# icyradio-exp-mmw-int.net
KiCad netlist of a schematic drawn in EAGLE
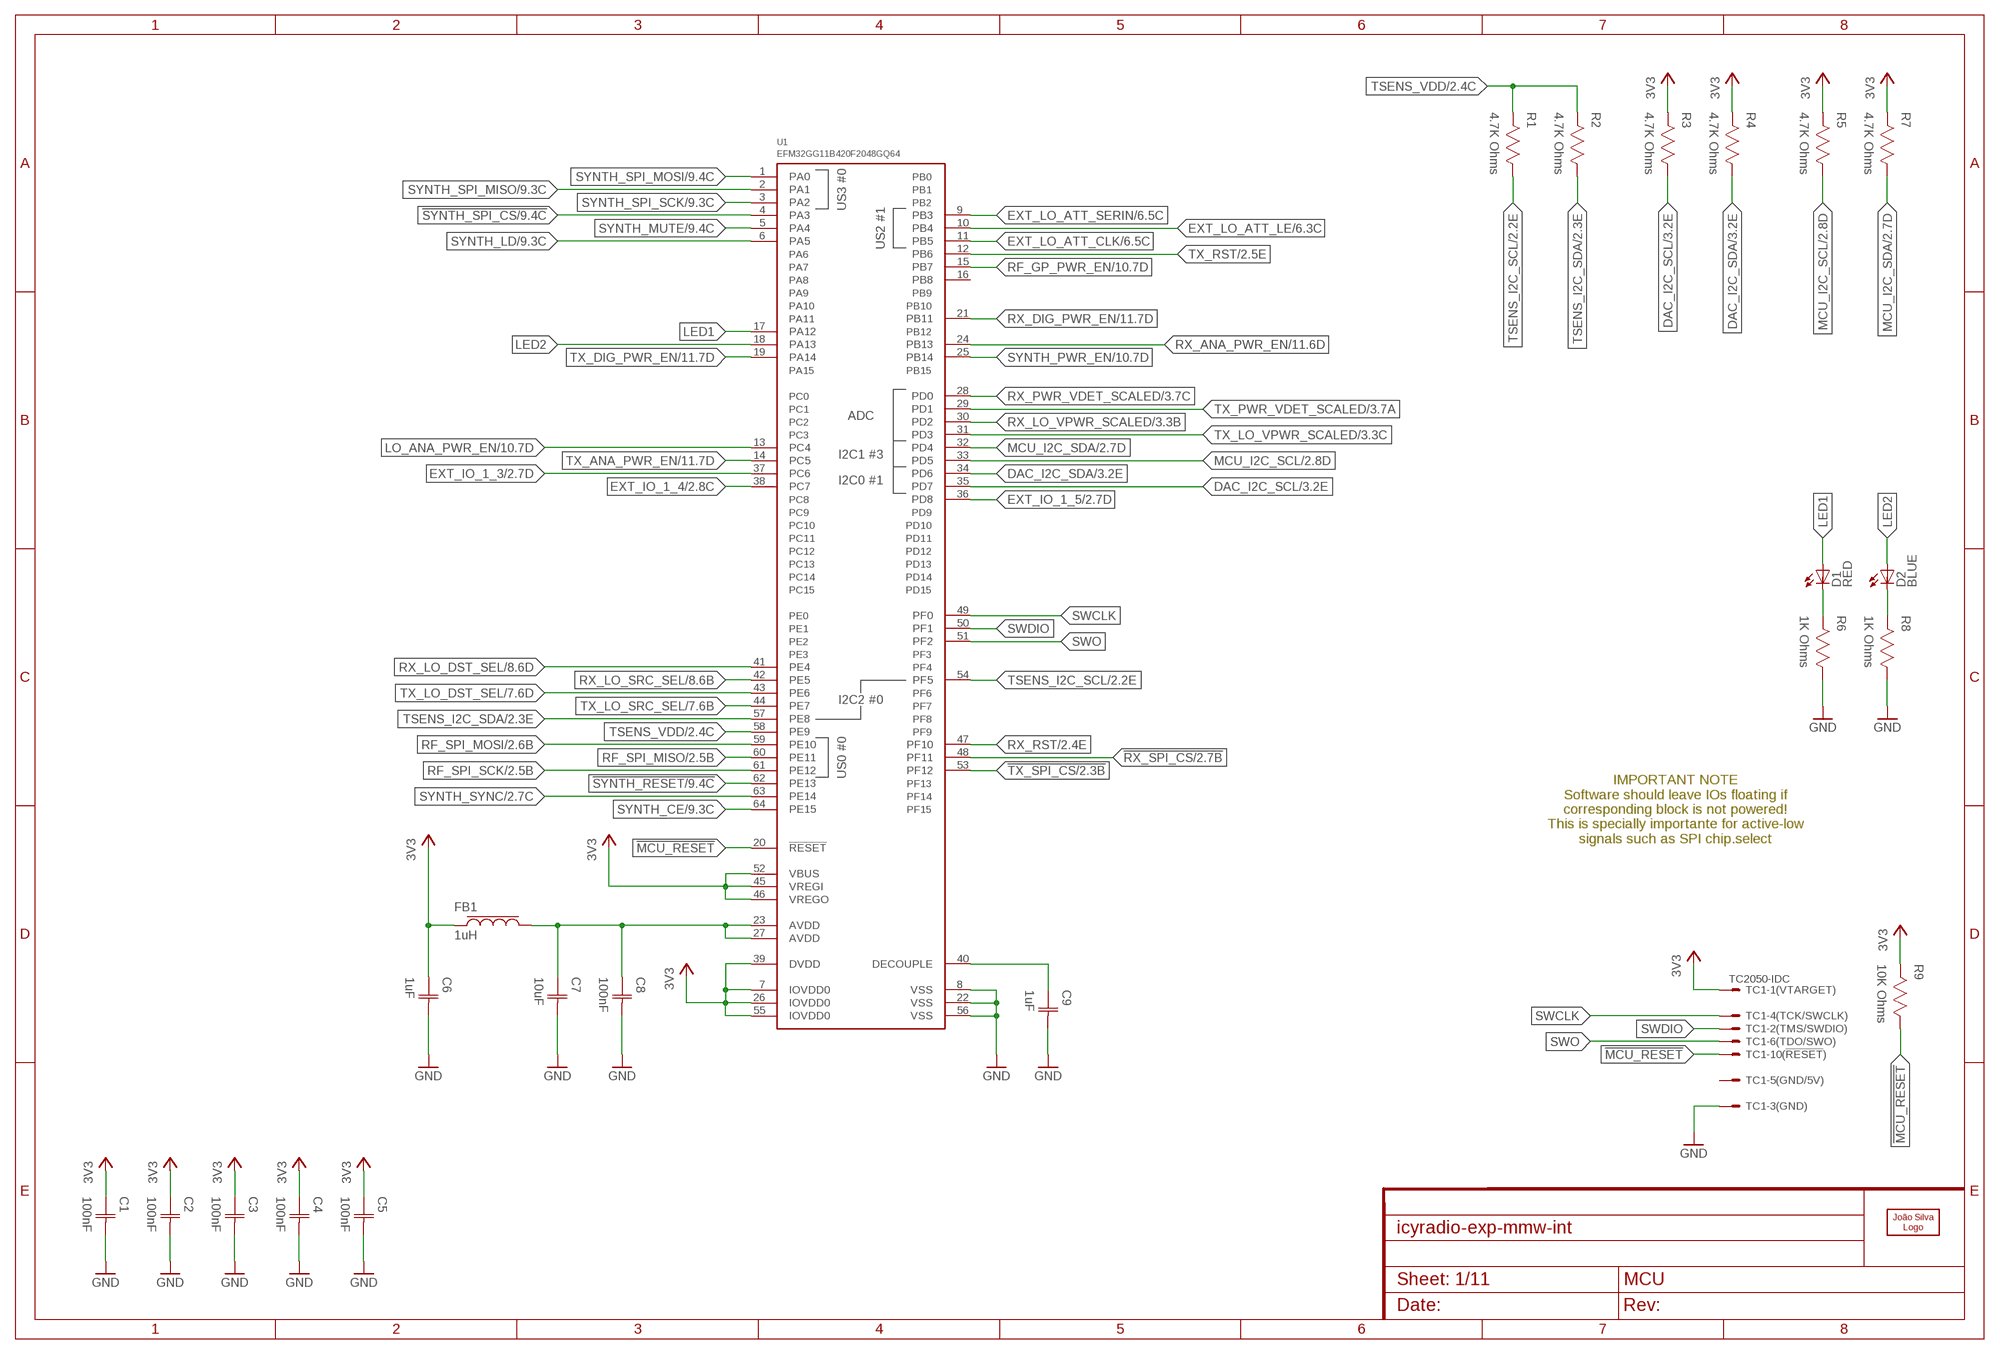
[diagram p0: schematic, sheet 1]
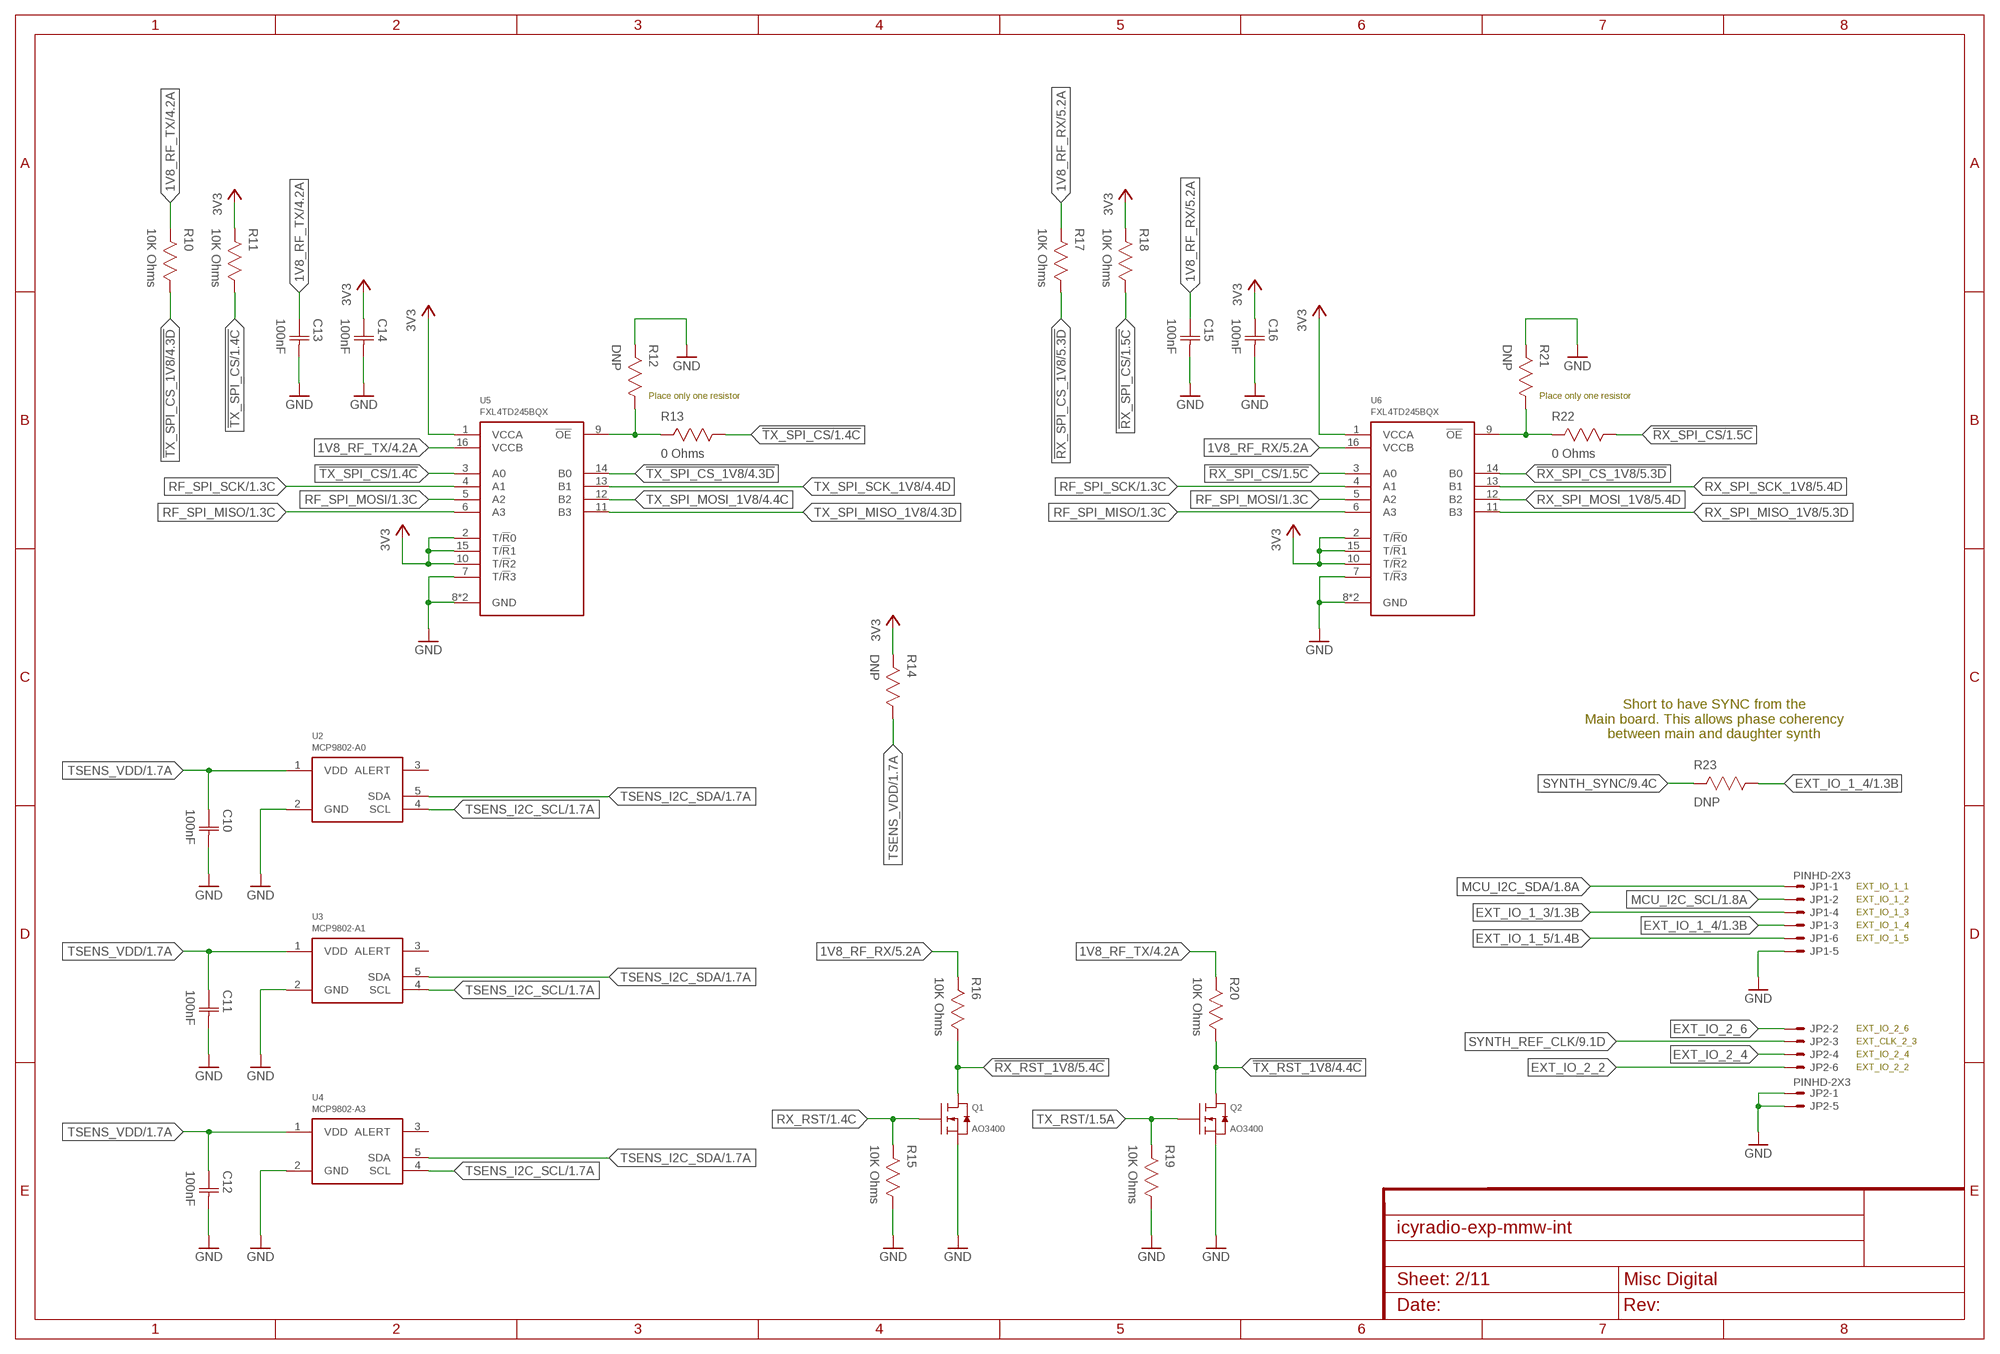
[diagram p1: schematic, sheet 2]
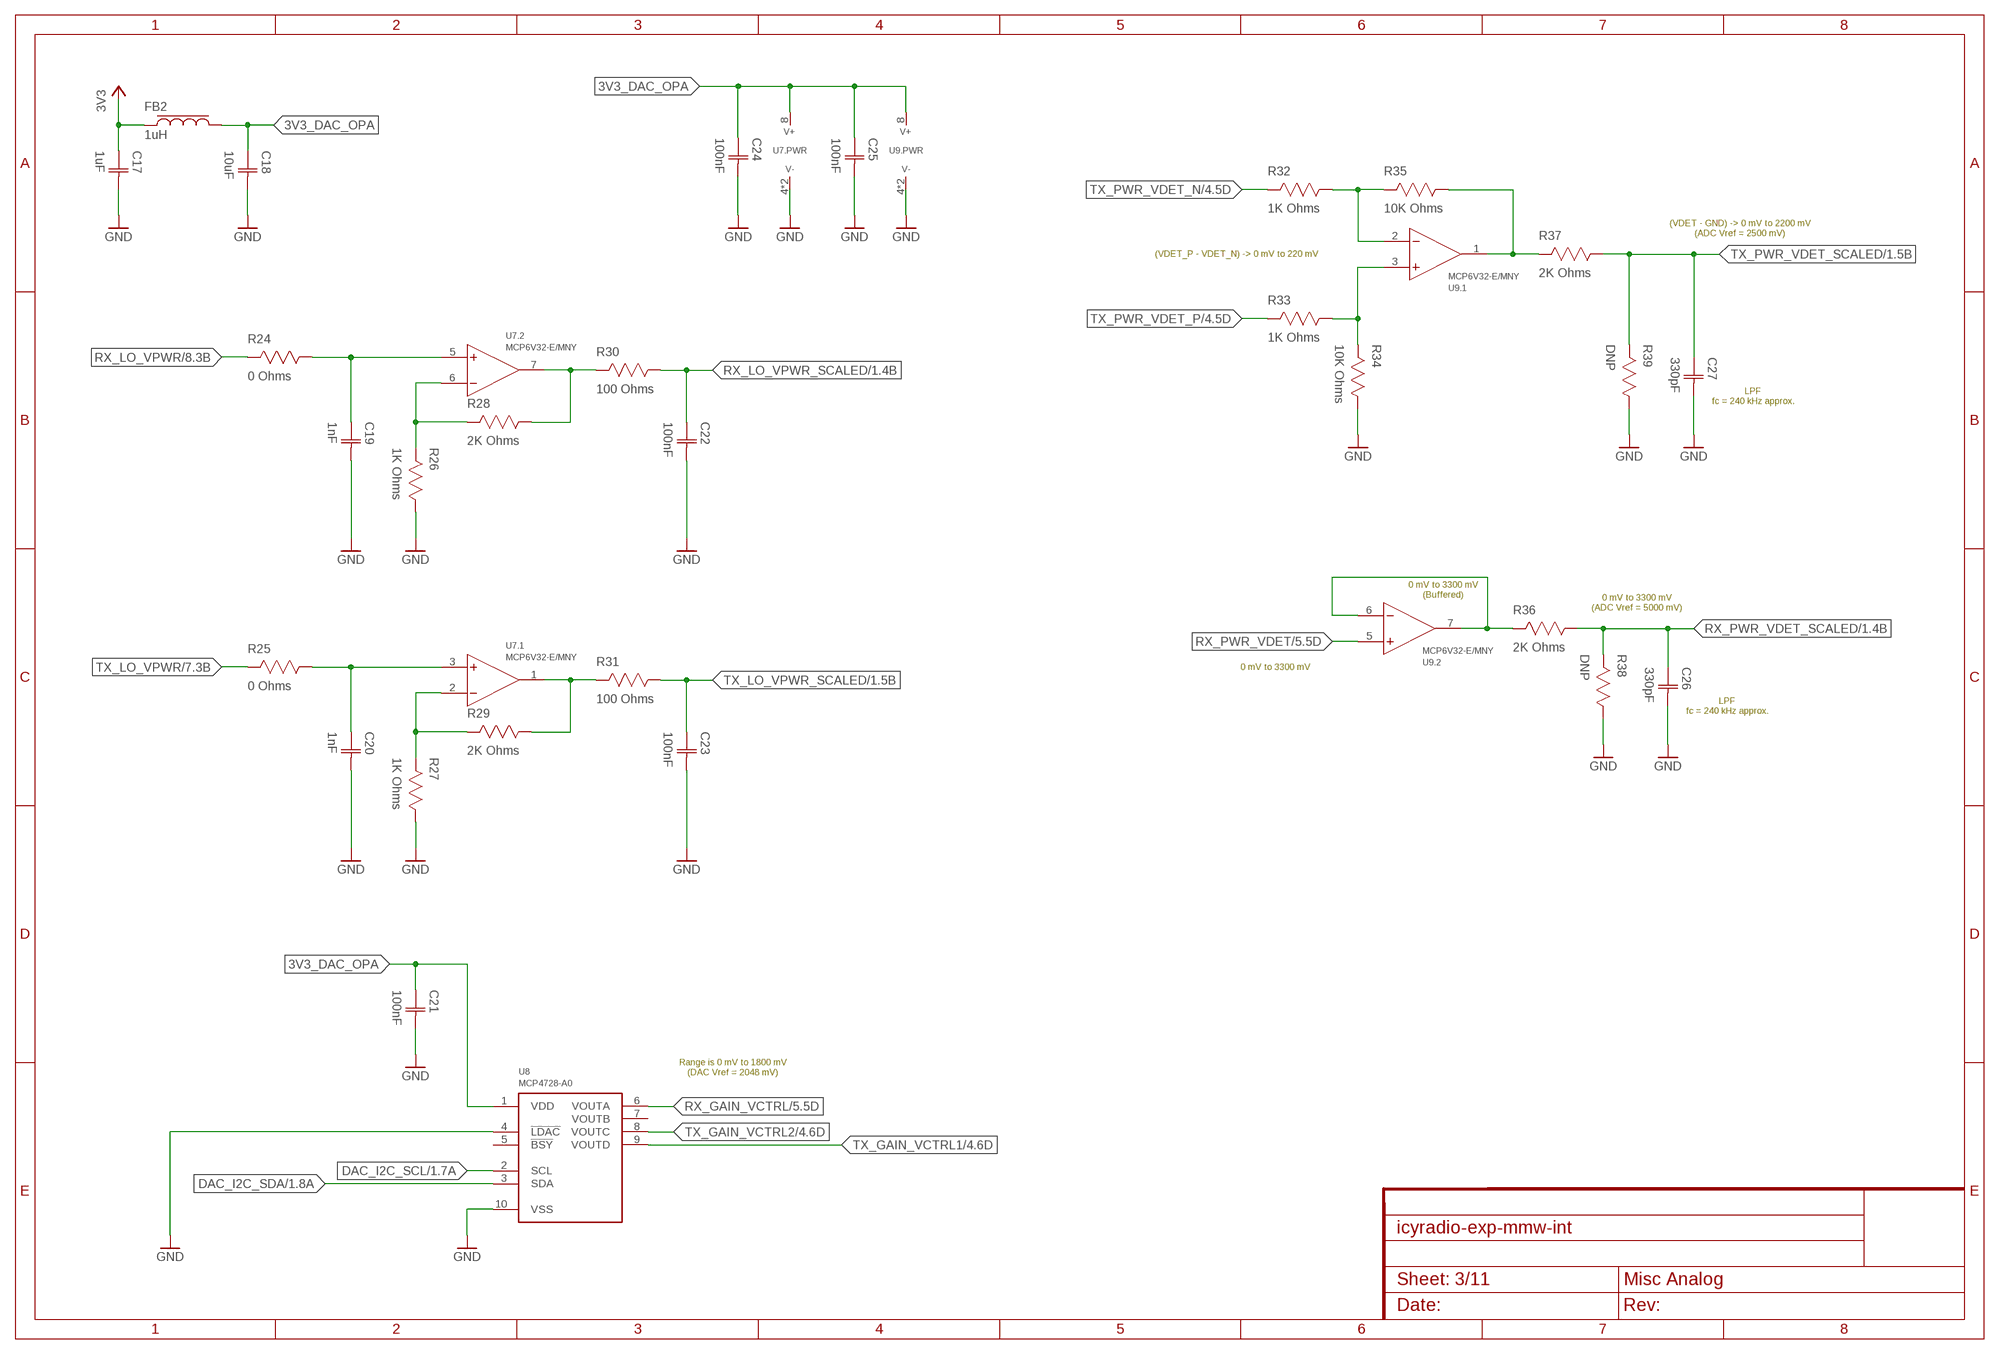
[diagram p2: schematic, sheet 3]
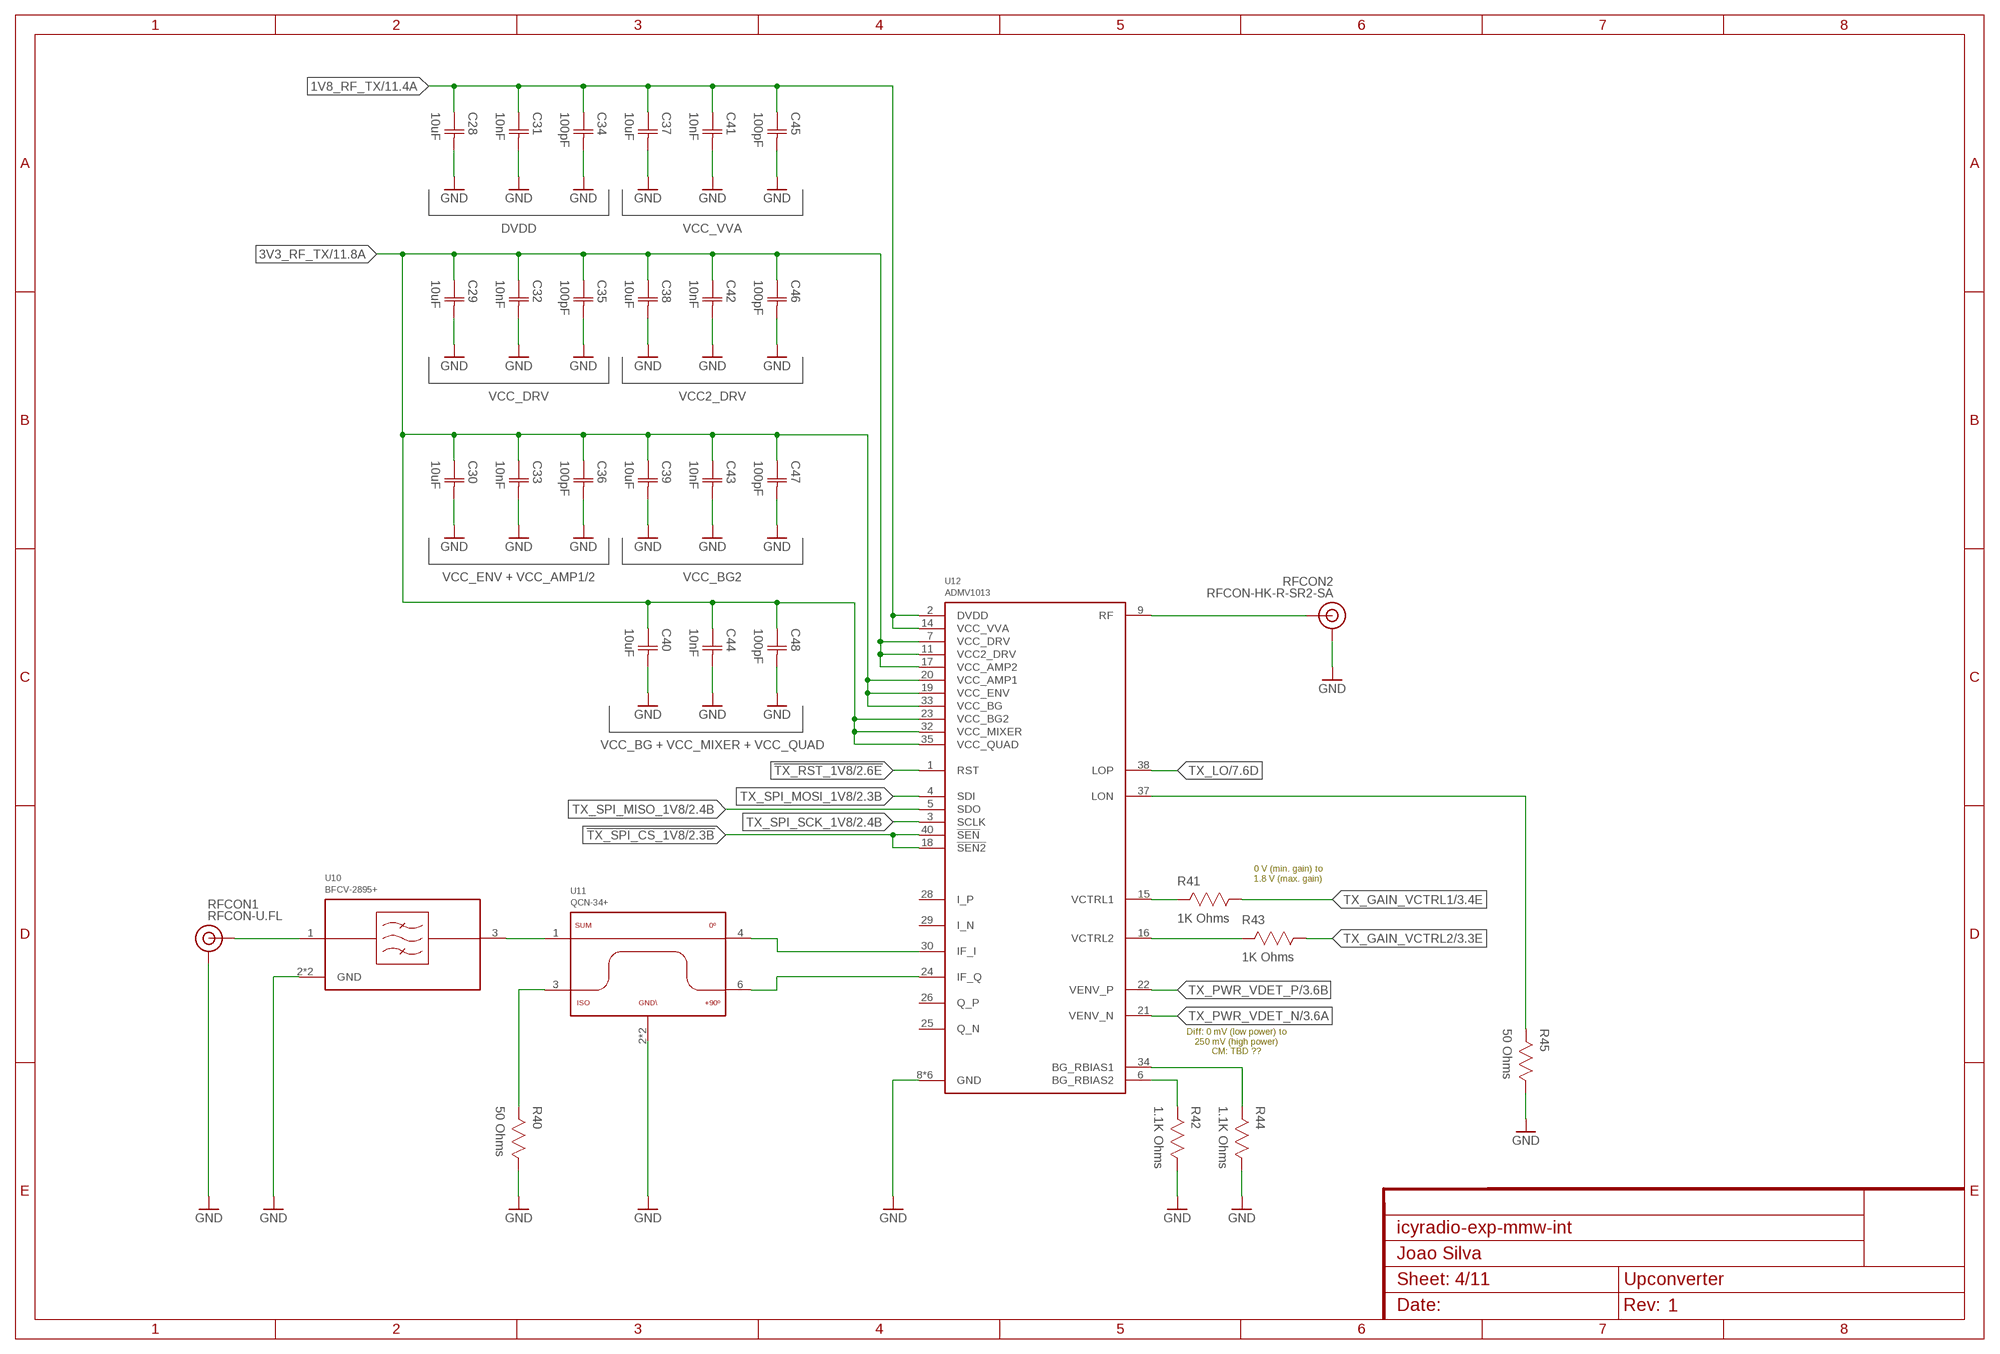
[diagram p3: schematic, sheet 4]
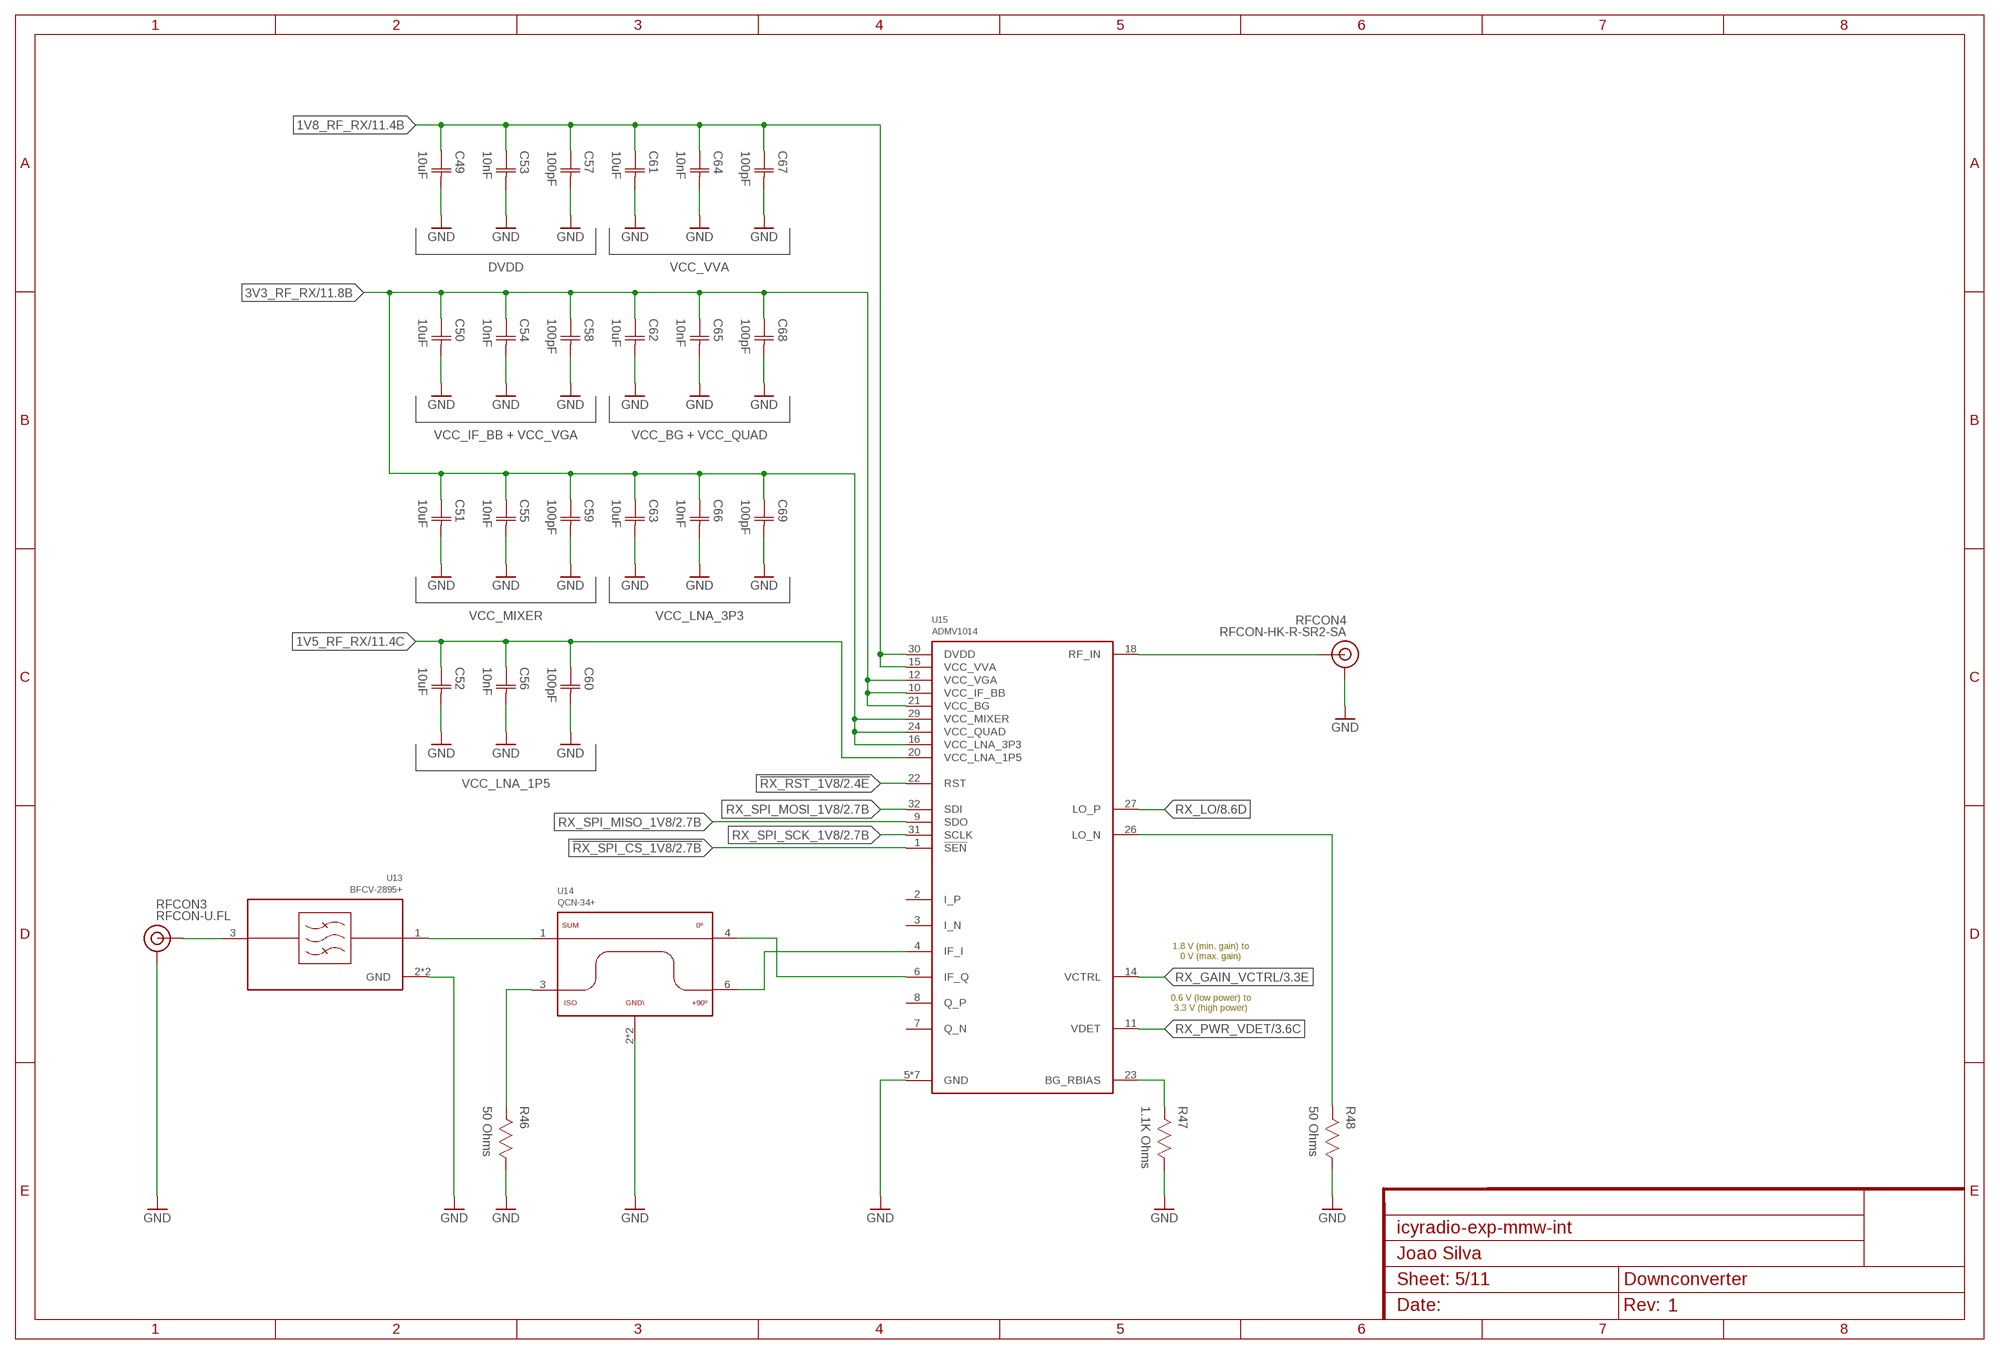
[diagram p4: schematic, sheet 5]
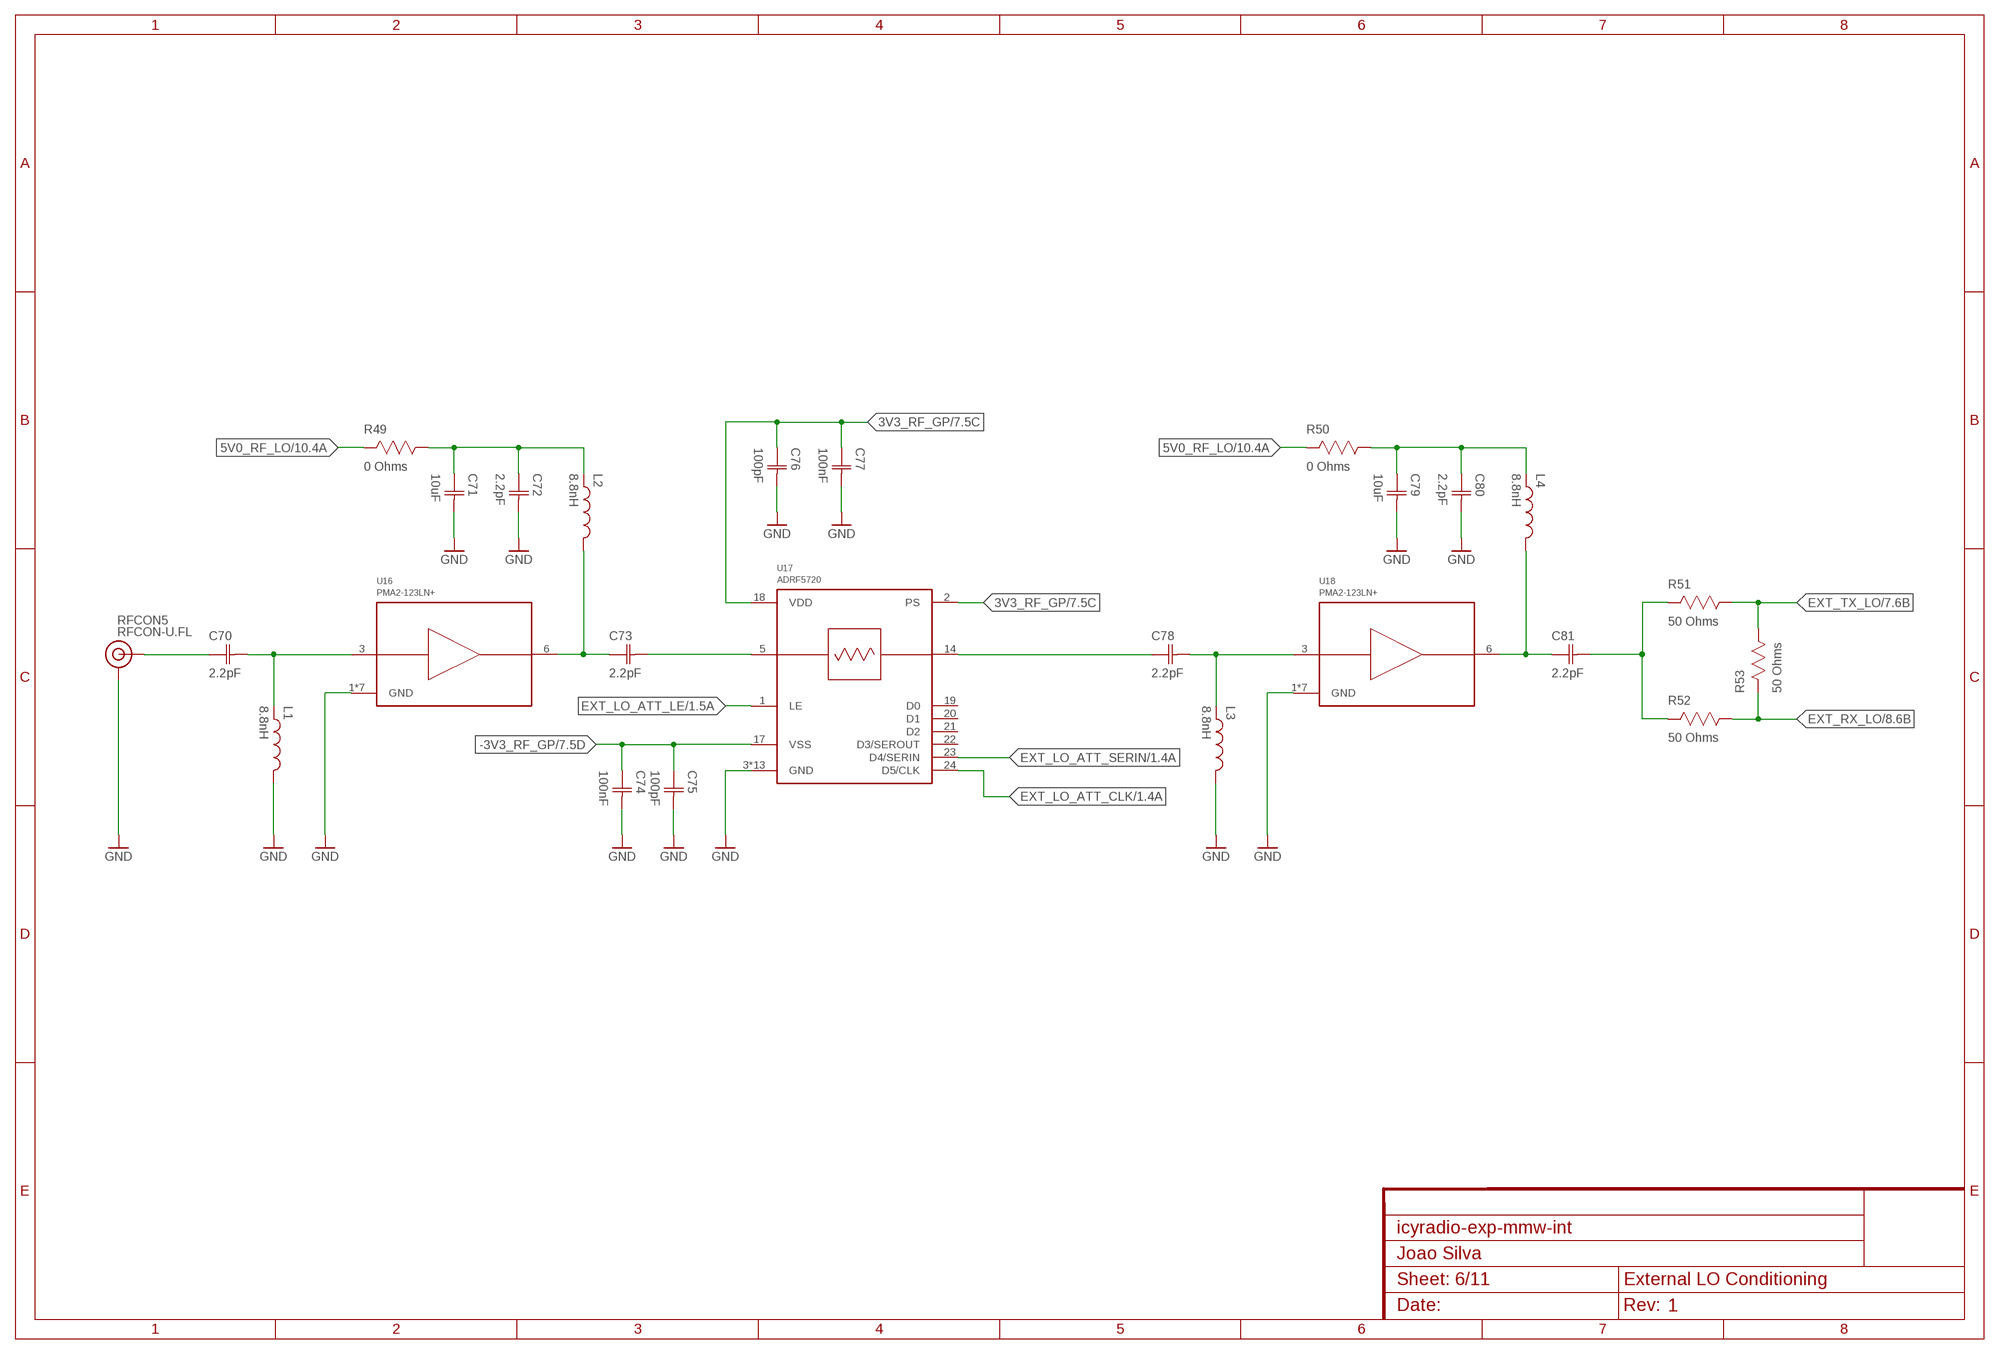
[diagram p5: schematic, sheet 6]
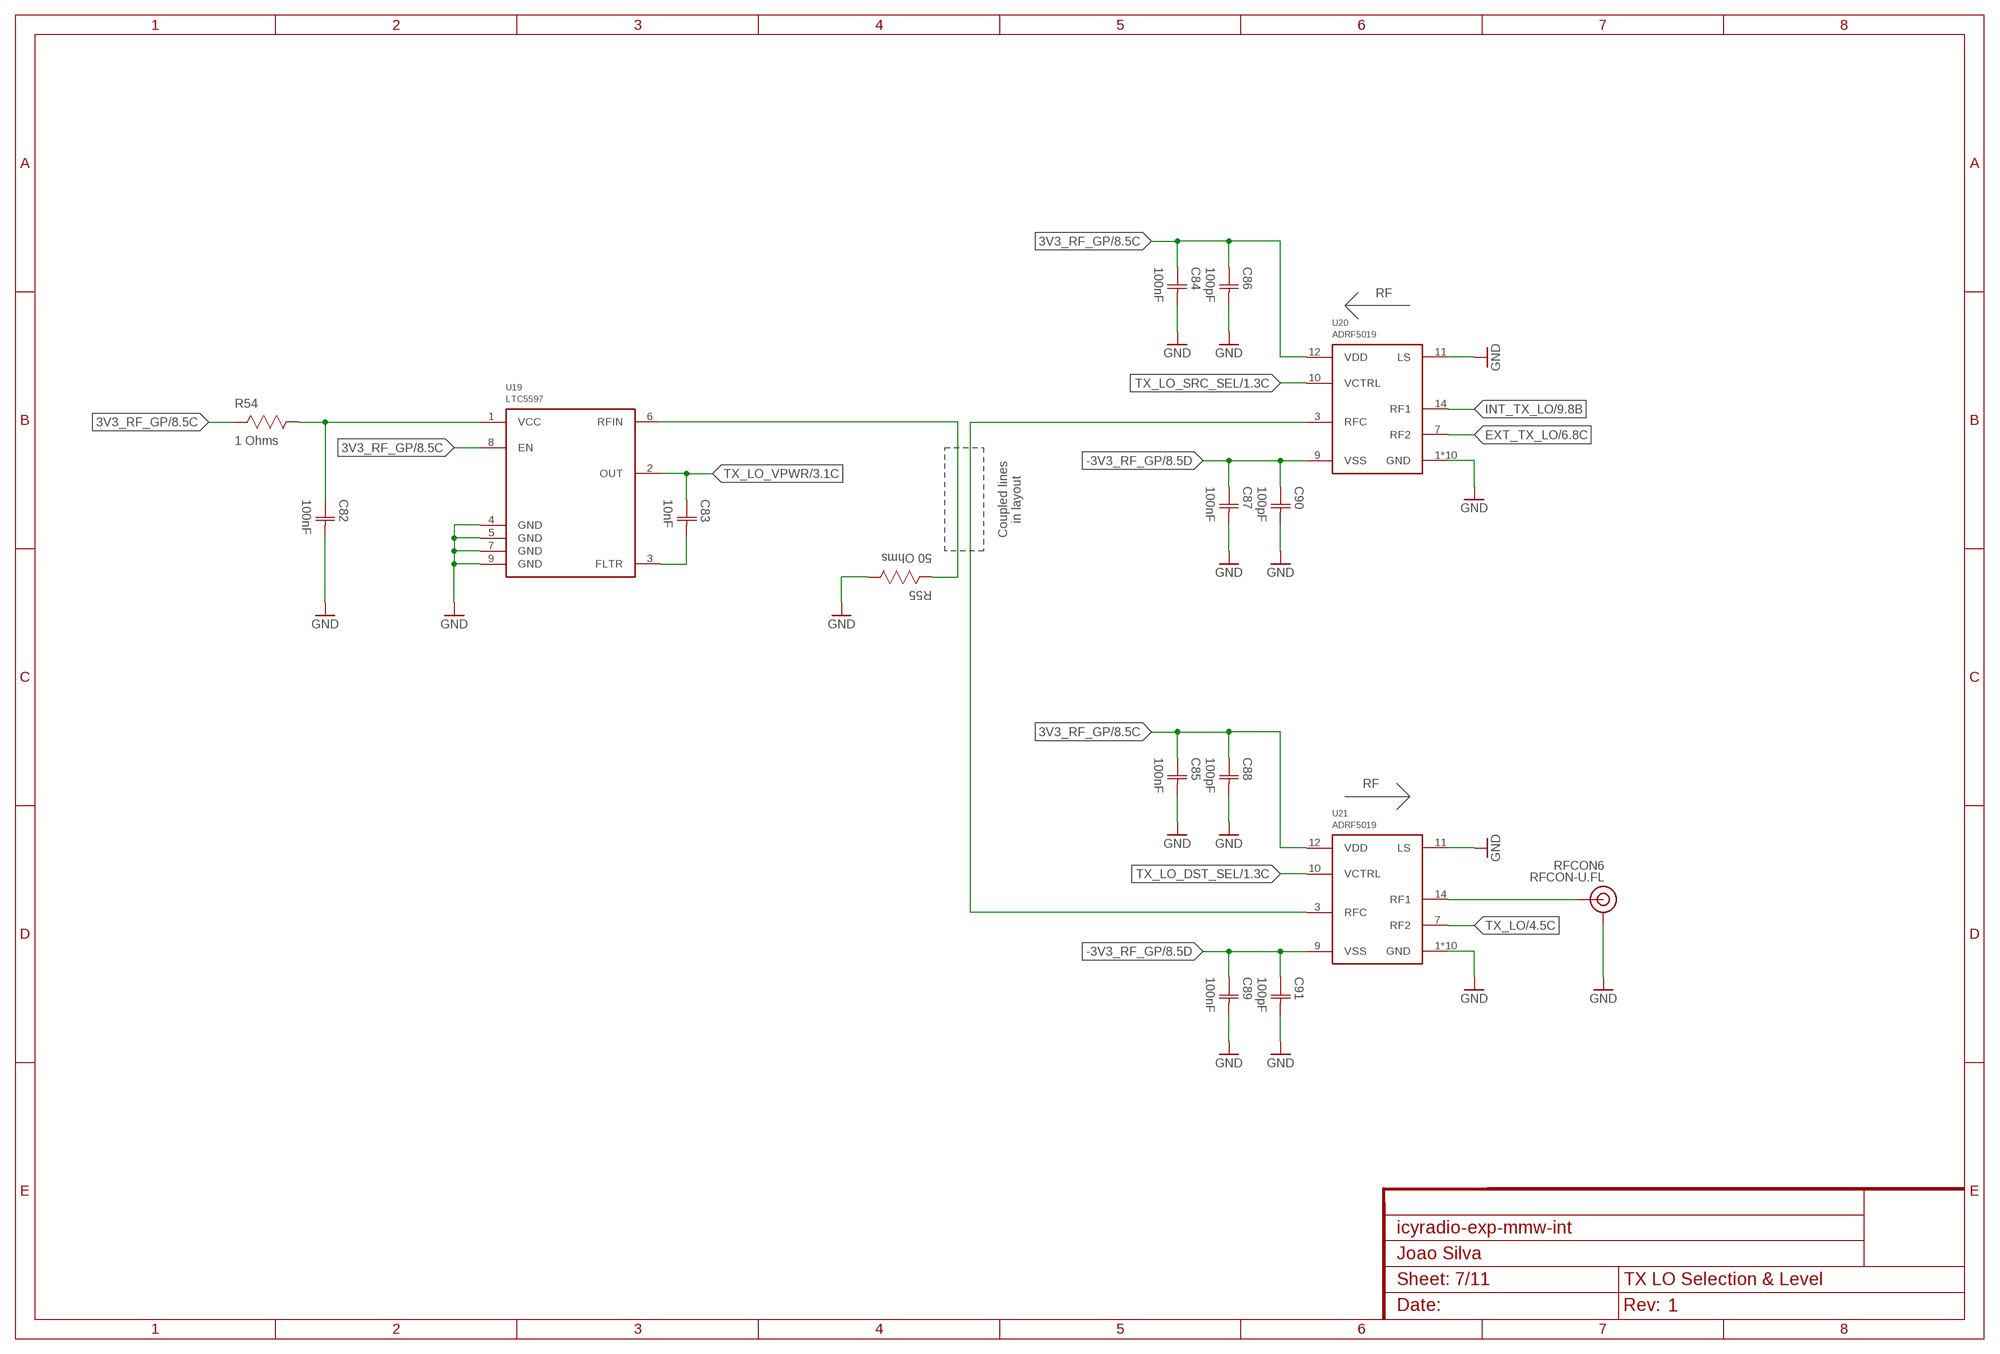
[diagram p6: schematic, sheet 7]
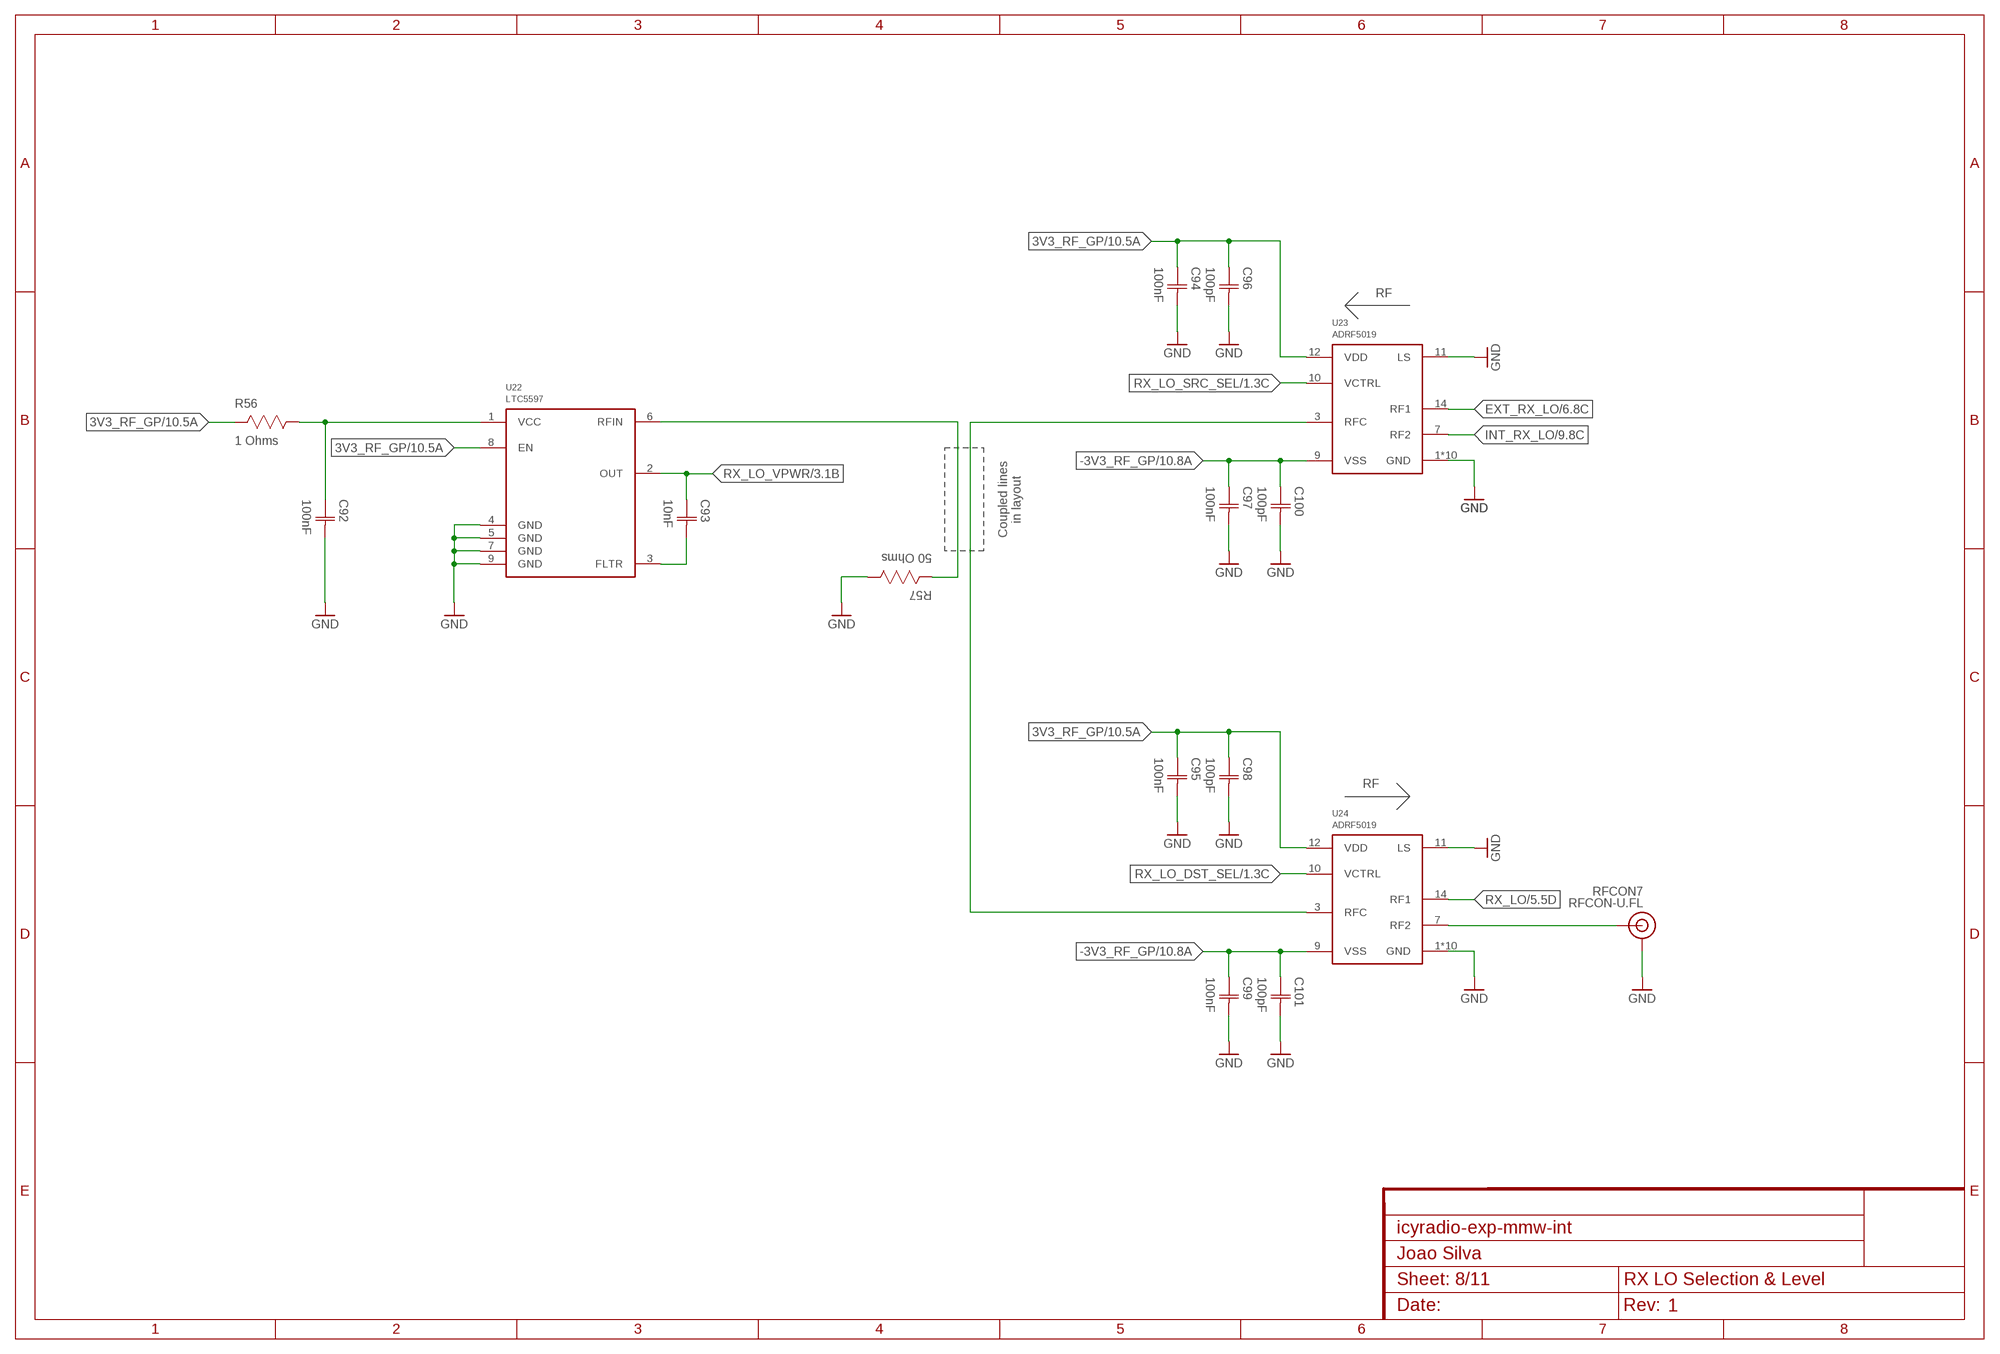
[diagram p7: schematic, sheet 8]
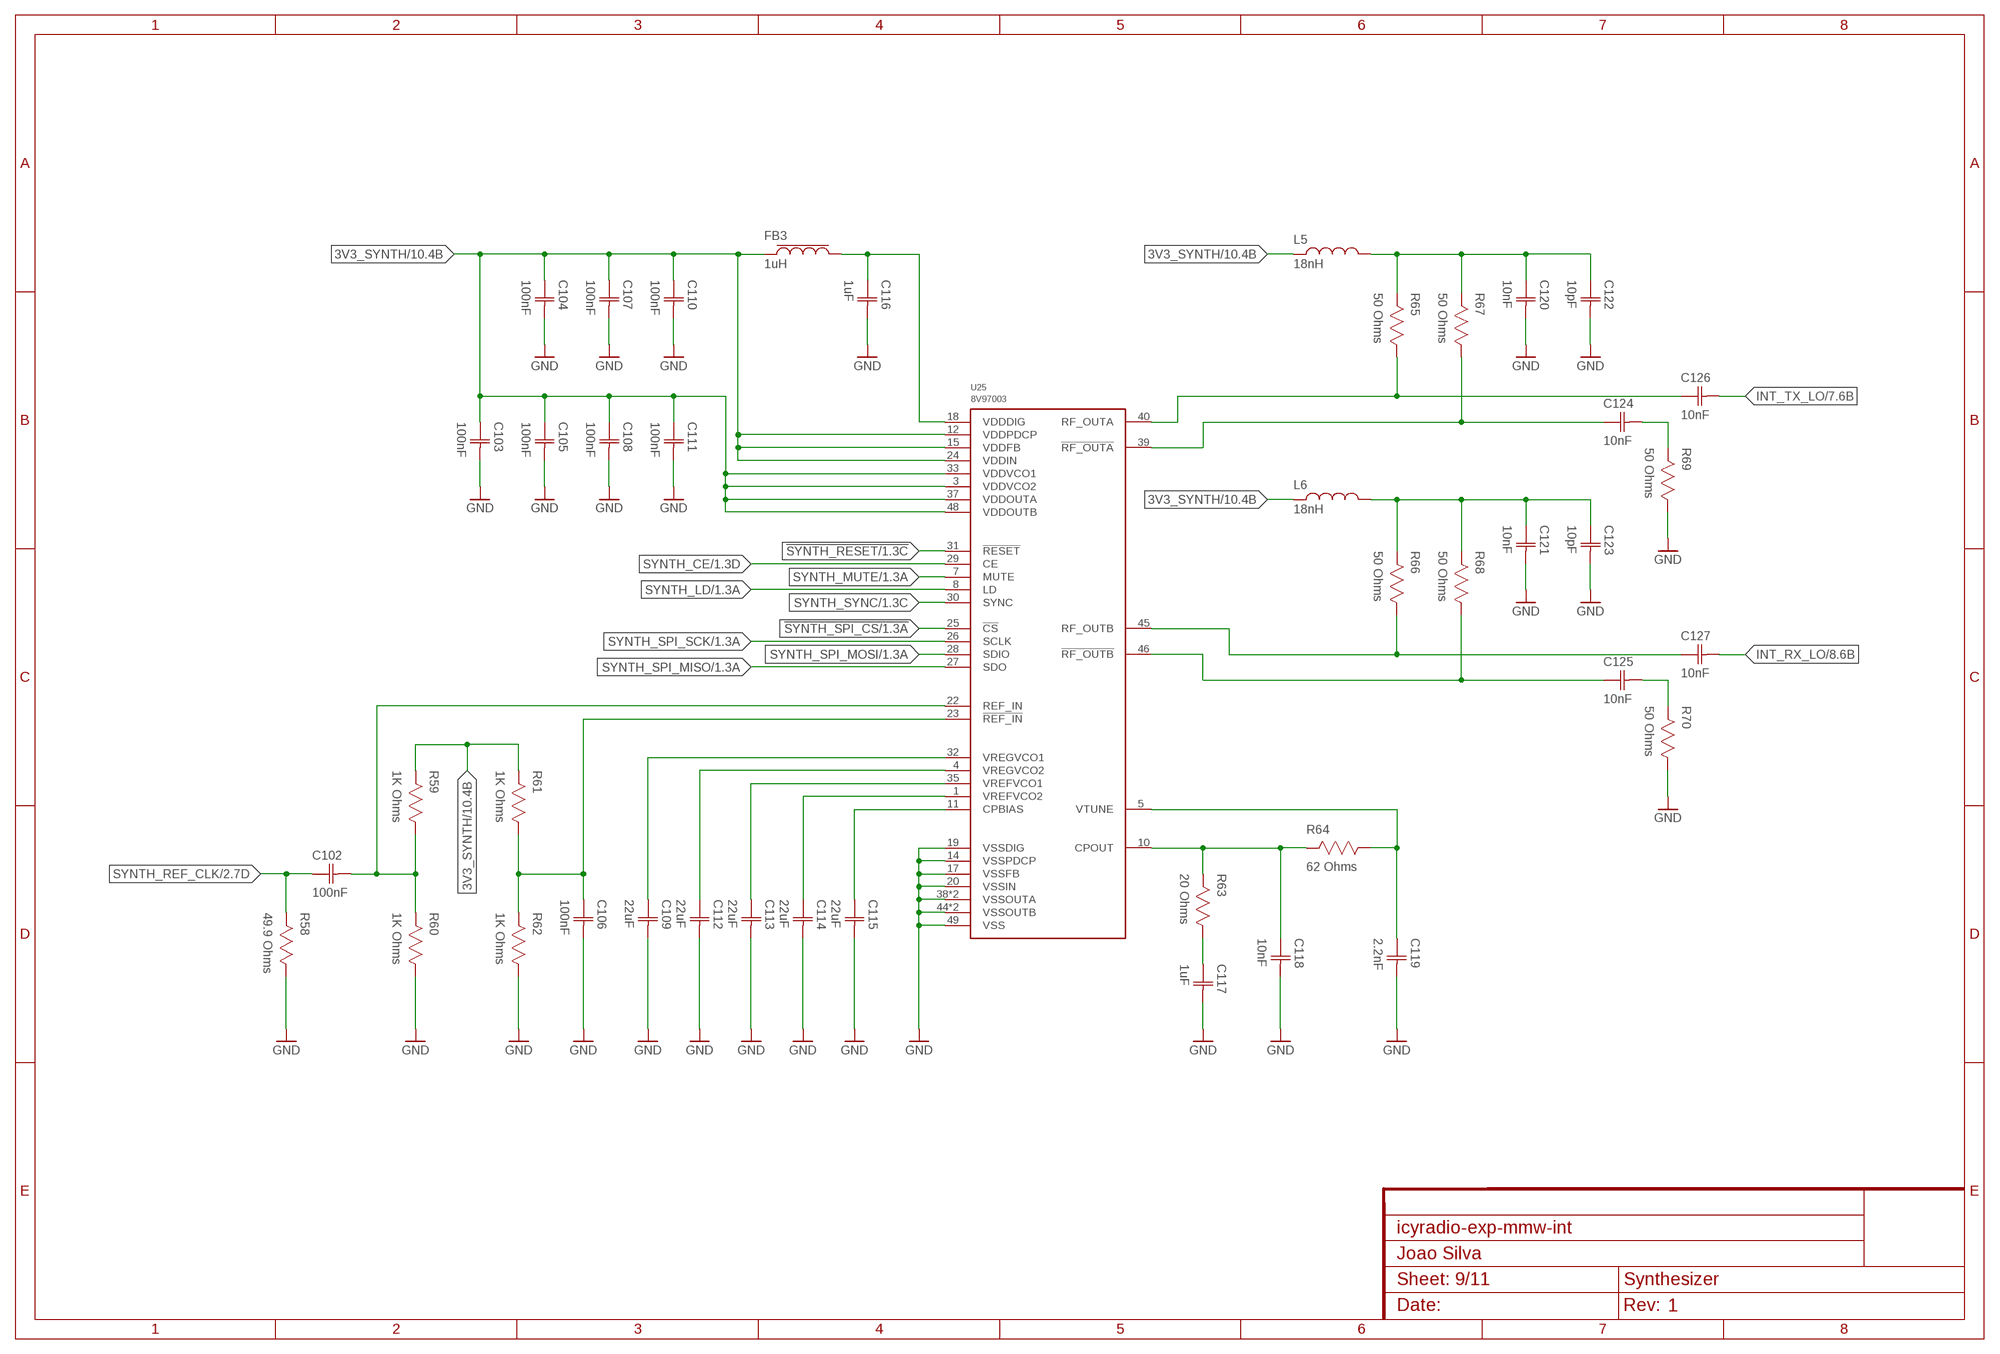
[diagram p8: schematic, sheet 9]
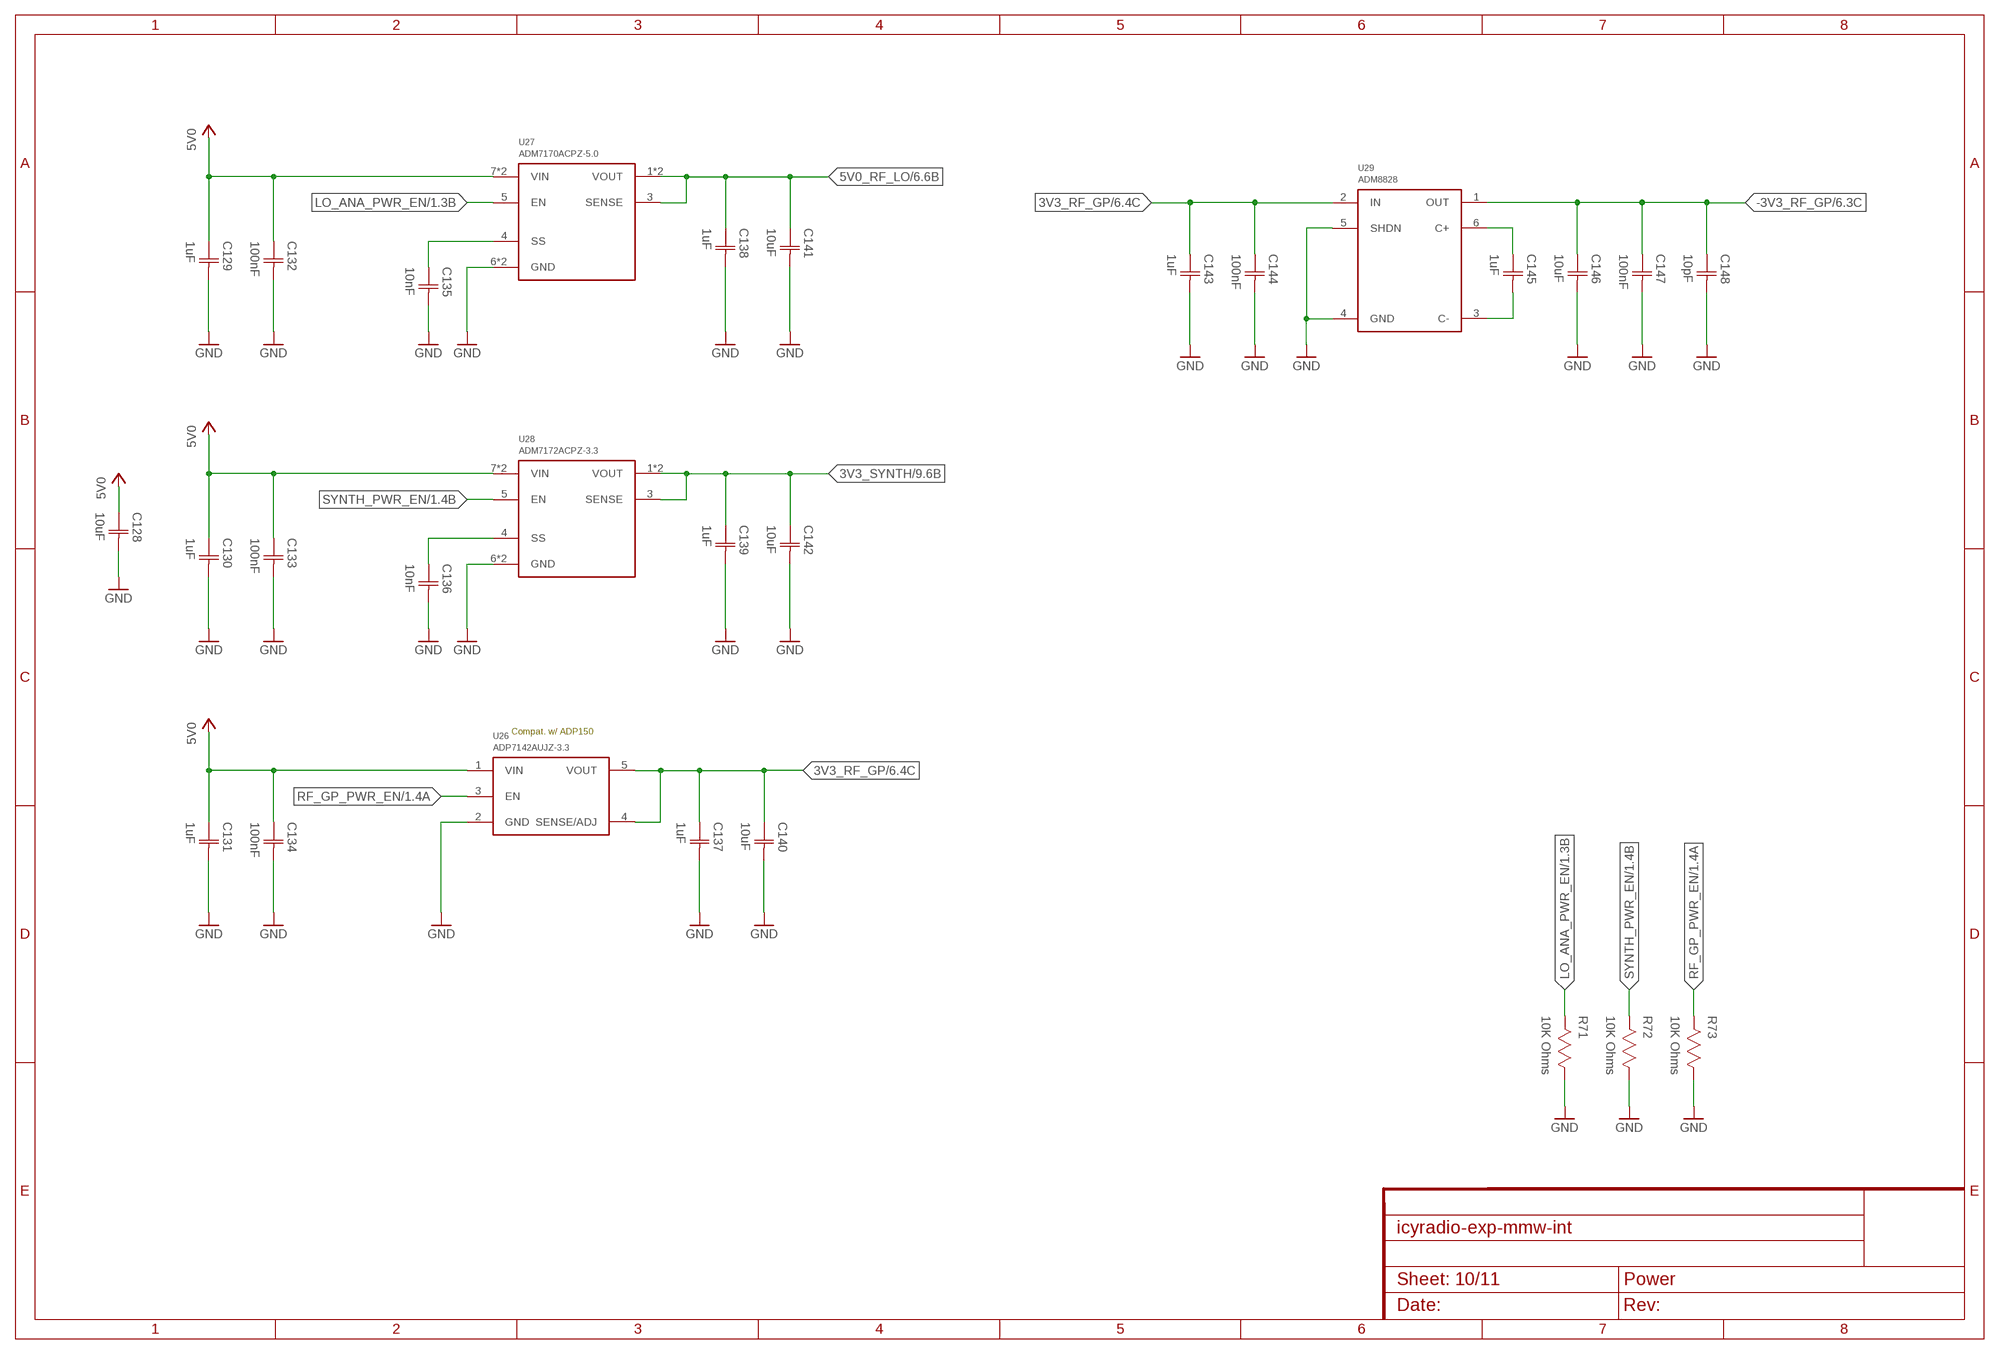
[diagram p9: schematic, sheet 10]
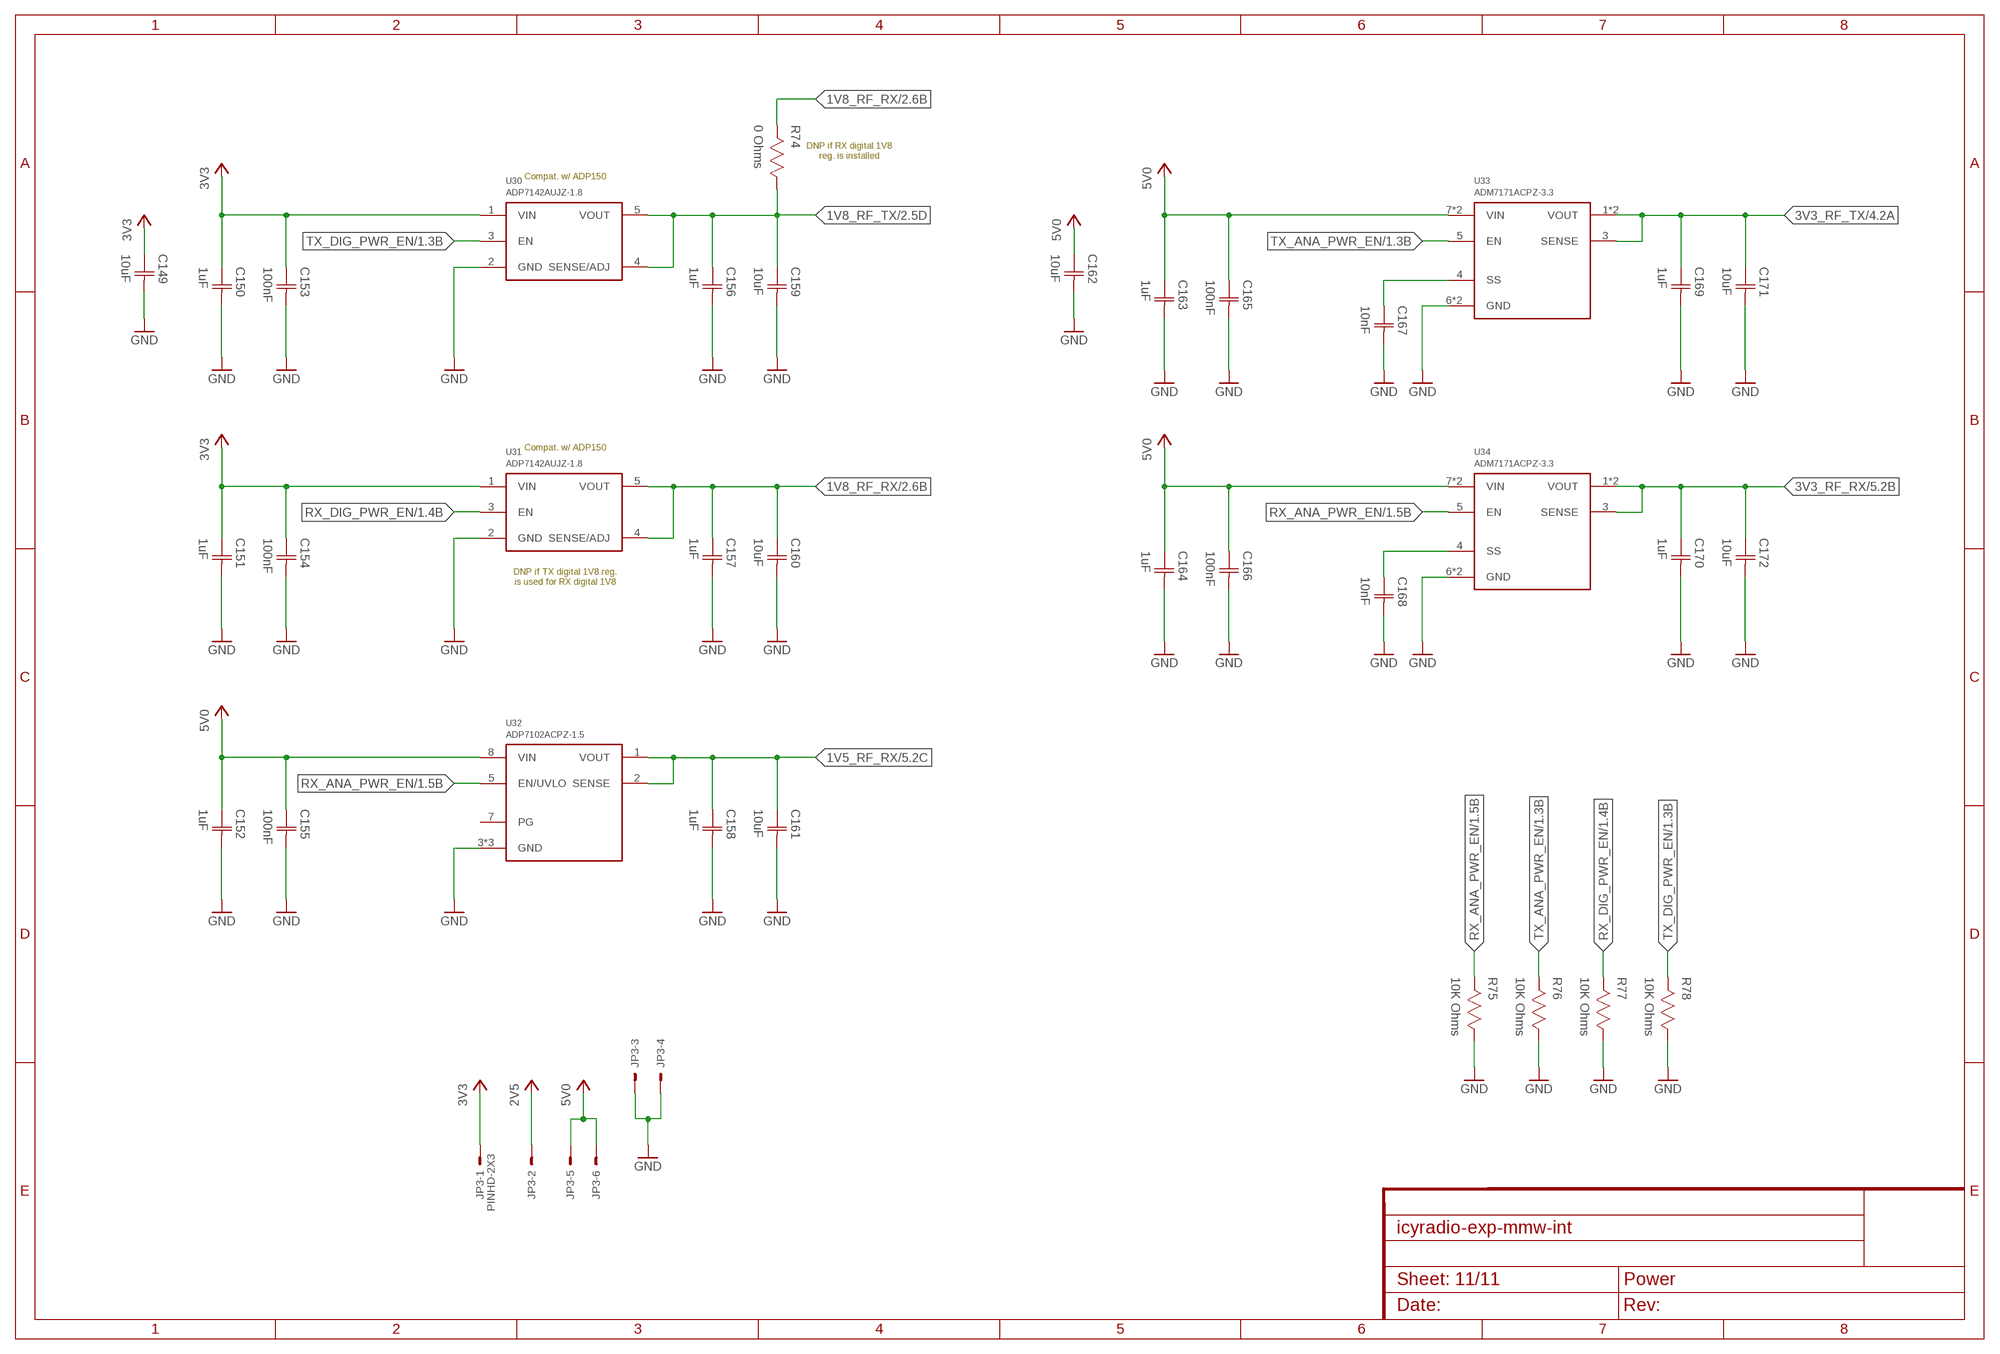
[diagram p10: schematic, sheet 11]

(export (version "E")
  (design (tool "Eeschema 10.0.6"))
  (components
    (comp (ref "C128")
      (value "10uF")
      (footprint "eagle-import:CAP0603")
      (libsource (lib "eagle-import") (part "CAPACITOR-0603"))
    )
    (comp (ref "C129")
      (value "1uF")
      (footprint "eagle-import:CAP0402")
      (libsource (lib "eagle-import") (part "CAPACITOR-0402"))
    )
    (comp (ref "C130")
      (value "1uF")
      (footprint "eagle-import:CAP0402")
      (libsource (lib "eagle-import") (part "CAPACITOR-0402"))
    )
    (comp (ref "C131")
      (value "1uF")
      (footprint "eagle-import:CAP0402")
      (libsource (lib "eagle-import") (part "CAPACITOR-0402"))
    )
    (comp (ref "C132")
      (value "100nF")
      (footprint "eagle-import:CAP0402")
      (libsource (lib "eagle-import") (part "CAPACITOR-0402"))
    )
    (comp (ref "C133")
      (value "100nF")
      (footprint "eagle-import:CAP0402")
      (libsource (lib "eagle-import") (part "CAPACITOR-0402"))
    )
    (comp (ref "C134")
      (value "100nF")
      (footprint "eagle-import:CAP0402")
      (libsource (lib "eagle-import") (part "CAPACITOR-0402"))
    )
    (comp (ref "C135")
      (value "10nF")
      (footprint "eagle-import:CAP0402")
      (libsource (lib "eagle-import") (part "CAPACITOR-0402"))
    )
    (comp (ref "C136")
      (value "10nF")
      (footprint "eagle-import:CAP0402")
      (libsource (lib "eagle-import") (part "CAPACITOR-0402"))
    )
    (comp (ref "C137")
      (value "1uF")
      (footprint "eagle-import:CAP0402")
      (libsource (lib "eagle-import") (part "CAPACITOR-0402"))
    )
    (comp (ref "C138")
      (value "1uF")
      (footprint "eagle-import:CAP0402")
      (libsource (lib "eagle-import") (part "CAPACITOR-0402"))
    )
    (comp (ref "C139")
      (value "1uF")
      (footprint "eagle-import:CAP0402")
      (libsource (lib "eagle-import") (part "CAPACITOR-0402"))
    )
    (comp (ref "C140")
      (value "10uF")
      (footprint "eagle-import:CAP0402")
      (libsource (lib "eagle-import") (part "CAPACITOR-0402"))
    )
    (comp (ref "C141")
      (value "10uF")
      (footprint "eagle-import:CAP0402")
      (libsource (lib "eagle-import") (part "CAPACITOR-0402"))
    )
    (comp (ref "C142")
      (value "10uF")
      (footprint "eagle-import:CAP0402")
      (libsource (lib "eagle-import") (part "CAPACITOR-0402"))
    )
    (comp (ref "C143")
      (value "1uF")
      (footprint "eagle-import:CAP0402")
      (libsource (lib "eagle-import") (part "CAPACITOR-0402"))
    )
    (comp (ref "C144")
      (value "100nF")
      (footprint "eagle-import:CAP0402")
      (libsource (lib "eagle-import") (part "CAPACITOR-0402"))
    )
    (comp (ref "C145")
      (value "1uF")
      (footprint "eagle-import:CAP0402")
      (libsource (lib "eagle-import") (part "CAPACITOR-0402"))
    )
    (comp (ref "C146")
      (value "10uF")
      (footprint "eagle-import:CAP0402")
      (libsource (lib "eagle-import") (part "CAPACITOR-0402"))
    )
    (comp (ref "C147")
      (value "100nF")
      (footprint "eagle-import:CAP0402")
      (libsource (lib "eagle-import") (part "CAPACITOR-0402"))
    )
    (comp (ref "C148")
      (value "10pF")
      (footprint "eagle-import:CAP0402")
      (libsource (lib "eagle-import") (part "CAPACITOR-0402"))
    )
    (comp (ref "R71")
      (value "10K Ohms")
      (footprint "eagle-import:RES0402")
      (libsource (lib "eagle-import") (part "RESISTOR-0402"))
    )
    (comp (ref "R72")
      (value "10K Ohms")
      (footprint "eagle-import:RES0402")
      (libsource (lib "eagle-import") (part "RESISTOR-0402"))
    )
    (comp (ref "R73")
      (value "10K Ohms")
      (footprint "eagle-import:RES0402")
      (libsource (lib "eagle-import") (part "RESISTOR-0402"))
    )
    (comp (ref "U26")
      (value "ADP7142AUJZ-3.3")
      (footprint "eagle-import:SOT23-5")
      (libsource (lib "eagle-import") (part "ADP7142AUJZ-3.3"))
    )
    (comp (ref "U27")
      (value "ADM7170ACPZ-5.0")
      (footprint "eagle-import:LFCSP8_3X3")
      (libsource (lib "eagle-import") (part "ADM7170ACPZ-5.0"))
    )
    (comp (ref "U28")
      (value "ADM7172ACPZ-3.3")
      (footprint "eagle-import:LFCSP8_3X3")
      (libsource (lib "eagle-import") (part "ADM7172ACPZ-3.3"))
    )
    (comp (ref "U29")
      (value "ADM8828")
      (footprint "eagle-import:SOT23-6")
      (libsource (lib "eagle-import") (part "ADM8828"))
    )
    (comp (ref "C92")
      (value "100nF")
      (footprint "eagle-import:CAP0402")
      (libsource (lib "eagle-import") (part "CAPACITOR-0402"))
    )
    (comp (ref "C93")
      (value "10nF")
      (footprint "eagle-import:CAP0402")
      (libsource (lib "eagle-import") (part "CAPACITOR-0402"))
    )
    (comp (ref "C94")
      (value "100nF")
      (footprint "eagle-import:CAP0402")
      (libsource (lib "eagle-import") (part "CAPACITOR-0402"))
    )
    (comp (ref "C95")
      (value "100nF")
      (footprint "eagle-import:CAP0402")
      (libsource (lib "eagle-import") (part "CAPACITOR-0402"))
    )
    (comp (ref "C96")
      (value "100pF")
      (footprint "eagle-import:CAP0402")
      (libsource (lib "eagle-import") (part "CAPACITOR-0402"))
    )
    (comp (ref "C97")
      (value "100nF")
      (footprint "eagle-import:CAP0402")
      (libsource (lib "eagle-import") (part "CAPACITOR-0402"))
    )
    (comp (ref "C98")
      (value "100pF")
      (footprint "eagle-import:CAP0402")
      (libsource (lib "eagle-import") (part "CAPACITOR-0402"))
    )
    (comp (ref "C99")
      (value "100nF")
      (footprint "eagle-import:CAP0402")
      (libsource (lib "eagle-import") (part "CAPACITOR-0402"))
    )
    (comp (ref "C100")
      (value "100pF")
      (footprint "eagle-import:CAP0402")
      (libsource (lib "eagle-import") (part "CAPACITOR-0402"))
    )
    (comp (ref "C101")
      (value "100pF")
      (footprint "eagle-import:CAP0402")
      (libsource (lib "eagle-import") (part "CAPACITOR-0402"))
    )
    (comp (ref "R56")
      (value "1 Ohms")
      (footprint "eagle-import:RES0402")
      (libsource (lib "eagle-import") (part "RESISTOR-0402"))
    )
    (comp (ref "R57")
      (value "50 Ohms")
      (footprint "eagle-import:RES0402")
      (libsource (lib "eagle-import") (part "RESISTOR-0402"))
    )
    (comp (ref "RFCON7")
      (value "RFCON-U.FL")
      (footprint "eagle-import:U.FL")
      (libsource (lib "eagle-import") (part "RFCON-U.FL"))
    )
    (comp (ref "U22")
      (value "LTC5597")
      (footprint "eagle-import:DFN8_2X2")
      (libsource (lib "eagle-import") (part "LTC5597"))
    )
    (comp (ref "U23")
      (value "ADRF5019")
      (footprint "eagle-import:LFCSP16")
      (libsource (lib "eagle-import") (part "ADRF5019"))
    )
    (comp (ref "U24")
      (value "ADRF5019")
      (footprint "eagle-import:LFCSP16")
      (libsource (lib "eagle-import") (part "ADRF5019"))
    )
    (comp (ref "C102")
      (value "100nF")
      (footprint "eagle-import:CAP0402")
      (libsource (lib "eagle-import") (part "CAPACITOR-0402"))
    )
    (comp (ref "C103")
      (value "100nF")
      (footprint "eagle-import:CAP0402")
      (libsource (lib "eagle-import") (part "CAPACITOR-0402"))
    )
    (comp (ref "C104")
      (value "100nF")
      (footprint "eagle-import:CAP0402")
      (libsource (lib "eagle-import") (part "CAPACITOR-0402"))
    )
    (comp (ref "C105")
      (value "100nF")
      (footprint "eagle-import:CAP0402")
      (libsource (lib "eagle-import") (part "CAPACITOR-0402"))
    )
    (comp (ref "C106")
      (value "100nF")
      (footprint "eagle-import:CAP0402")
      (libsource (lib "eagle-import") (part "CAPACITOR-0402"))
    )
    (comp (ref "C107")
      (value "100nF")
      (footprint "eagle-import:CAP0402")
      (libsource (lib "eagle-import") (part "CAPACITOR-0402"))
    )
    (comp (ref "C108")
      (value "100nF")
      (footprint "eagle-import:CAP0402")
      (libsource (lib "eagle-import") (part "CAPACITOR-0402"))
    )
    (comp (ref "C109")
      (value "22uF")
      (footprint "eagle-import:CAP0402")
      (libsource (lib "eagle-import") (part "CAPACITOR-0402"))
    )
    (comp (ref "C110")
      (value "100nF")
      (footprint "eagle-import:CAP0402")
      (libsource (lib "eagle-import") (part "CAPACITOR-0402"))
    )
    (comp (ref "C111")
      (value "100nF")
      (footprint "eagle-import:CAP0402")
      (libsource (lib "eagle-import") (part "CAPACITOR-0402"))
    )
    (comp (ref "C112")
      (value "22uF")
      (footprint "eagle-import:CAP0402")
      (libsource (lib "eagle-import") (part "CAPACITOR-0402"))
    )
    (comp (ref "C113")
      (value "22uF")
      (footprint "eagle-import:CAP0402")
      (libsource (lib "eagle-import") (part "CAPACITOR-0402"))
    )
    (comp (ref "C114")
      (value "22uF")
      (footprint "eagle-import:CAP0402")
      (libsource (lib "eagle-import") (part "CAPACITOR-0402"))
    )
    (comp (ref "C115")
      (value "22uF")
      (footprint "eagle-import:CAP0402")
      (libsource (lib "eagle-import") (part "CAPACITOR-0402"))
    )
    (comp (ref "C116")
      (value "1uF")
      (footprint "eagle-import:CAP0402")
      (libsource (lib "eagle-import") (part "CAPACITOR-0402"))
    )
    (comp (ref "C117")
      (value "1uF")
      (footprint "eagle-import:CAP0402")
      (libsource (lib "eagle-import") (part "CAPACITOR-0402"))
    )
    (comp (ref "C118")
      (value "10nF")
      (footprint "eagle-import:CAP0402")
      (libsource (lib "eagle-import") (part "CAPACITOR-0402"))
    )
    (comp (ref "C119")
      (value "2.2nF")
      (footprint "eagle-import:CAP0402")
      (libsource (lib "eagle-import") (part "CAPACITOR-0402"))
    )
    (comp (ref "C120")
      (value "10nF")
      (footprint "eagle-import:CAP0402")
      (libsource (lib "eagle-import") (part "CAPACITOR-0402"))
    )
    (comp (ref "C121")
      (value "10nF")
      (footprint "eagle-import:CAP0402")
      (libsource (lib "eagle-import") (part "CAPACITOR-0402"))
    )
    (comp (ref "C122")
      (value "10pF")
      (footprint "eagle-import:CAP0402")
      (libsource (lib "eagle-import") (part "CAPACITOR-0402"))
    )
    (comp (ref "C123")
      (value "10pF")
      (footprint "eagle-import:CAP0402")
      (libsource (lib "eagle-import") (part "CAPACITOR-0402"))
    )
    (comp (ref "C124")
      (value "10nF")
      (footprint "eagle-import:CAP0402")
      (libsource (lib "eagle-import") (part "CAPACITOR-0402"))
    )
    (comp (ref "C125")
      (value "10nF")
      (footprint "eagle-import:CAP0402")
      (libsource (lib "eagle-import") (part "CAPACITOR-0402"))
    )
    (comp (ref "C126")
      (value "10nF")
      (footprint "eagle-import:CAP0402")
      (libsource (lib "eagle-import") (part "CAPACITOR-0402"))
    )
    (comp (ref "C127")
      (value "10nF")
      (footprint "eagle-import:CAP0402")
      (libsource (lib "eagle-import") (part "CAPACITOR-0402"))
    )
    (comp (ref "FB3")
      (value "1uH")
      (footprint "eagle-import:IND0603")
      (libsource (lib "eagle-import") (part "FERRITE-0603"))
    )
    (comp (ref "L5")
      (value "18nH")
      (footprint "eagle-import:IND0402")
      (libsource (lib "eagle-import") (part "INDUCTOR-0402"))
    )
    (comp (ref "L6")
      (value "18nH")
      (footprint "eagle-import:IND0402")
      (libsource (lib "eagle-import") (part "INDUCTOR-0402"))
    )
    (comp (ref "R58")
      (value "49.9 Ohms")
      (footprint "eagle-import:RES0402")
      (libsource (lib "eagle-import") (part "RESISTOR-0402"))
    )
    (comp (ref "R59")
      (value "1K Ohms")
      (footprint "eagle-import:RES0402")
      (libsource (lib "eagle-import") (part "RESISTOR-0402"))
    )
    (comp (ref "R60")
      (value "1K Ohms")
      (footprint "eagle-import:RES0402")
      (libsource (lib "eagle-import") (part "RESISTOR-0402"))
    )
    (comp (ref "R61")
      (value "1K Ohms")
      (footprint "eagle-import:RES0402")
      (libsource (lib "eagle-import") (part "RESISTOR-0402"))
    )
    (comp (ref "R62")
      (value "1K Ohms")
      (footprint "eagle-import:RES0402")
      (libsource (lib "eagle-import") (part "RESISTOR-0402"))
    )
    (comp (ref "R63")
      (value "20 Ohms")
      (footprint "eagle-import:RES0402")
      (libsource (lib "eagle-import") (part "RESISTOR-0402"))
    )
    (comp (ref "R64")
      (value "62 Ohms")
      (footprint "eagle-import:RES0402")
      (libsource (lib "eagle-import") (part "RESISTOR-0402"))
    )
    (comp (ref "R65")
      (value "50 Ohms")
      (footprint "eagle-import:RES0402")
      (libsource (lib "eagle-import") (part "RESISTOR-0402"))
    )
    (comp (ref "R66")
      (value "50 Ohms")
      (footprint "eagle-import:RES0402")
      (libsource (lib "eagle-import") (part "RESISTOR-0402"))
    )
    (comp (ref "R67")
      (value "50 Ohms")
      (footprint "eagle-import:RES0402")
      (libsource (lib "eagle-import") (part "RESISTOR-0402"))
    )
    (comp (ref "R68")
      (value "50 Ohms")
      (footprint "eagle-import:RES0402")
      (libsource (lib "eagle-import") (part "RESISTOR-0402"))
    )
    (comp (ref "R69")
      (value "50 Ohms")
      (footprint "eagle-import:RES0402")
      (libsource (lib "eagle-import") (part "RESISTOR-0402"))
    )
    (comp (ref "R70")
      (value "50 Ohms")
      (footprint "eagle-import:RES0402")
      (libsource (lib "eagle-import") (part "RESISTOR-0402"))
    )
    (comp (ref "U25")
      (value "8V97003")
      (footprint "eagle-import:VFQFPN48")
      (libsource (lib "eagle-import") (part "8V97003"))
    )
    (comp (ref "C17")
      (value "1uF")
      (footprint "eagle-import:CAP0402")
      (libsource (lib "eagle-import") (part "CAPACITOR-0402"))
    )
    (comp (ref "C18")
      (value "10uF")
      (footprint "eagle-import:CAP0402")
      (libsource (lib "eagle-import") (part "CAPACITOR-0402"))
    )
    (comp (ref "C19")
      (value "1nF")
      (footprint "eagle-import:CAP0402")
      (libsource (lib "eagle-import") (part "CAPACITOR-0402"))
    )
    (comp (ref "C20")
      (value "1nF")
      (footprint "eagle-import:CAP0402")
      (libsource (lib "eagle-import") (part "CAPACITOR-0402"))
    )
    (comp (ref "C21")
      (value "100nF")
      (footprint "eagle-import:CAP0402")
      (libsource (lib "eagle-import") (part "CAPACITOR-0402"))
    )
    (comp (ref "C22")
      (value "100nF")
      (footprint "eagle-import:CAP0402")
      (libsource (lib "eagle-import") (part "CAPACITOR-0402"))
    )
    (comp (ref "C23")
      (value "100nF")
      (footprint "eagle-import:CAP0402")
      (libsource (lib "eagle-import") (part "CAPACITOR-0402"))
    )
    (comp (ref "C24")
      (value "100nF")
      (footprint "eagle-import:CAP0402")
      (libsource (lib "eagle-import") (part "CAPACITOR-0402"))
    )
    (comp (ref "C25")
      (value "100nF")
      (footprint "eagle-import:CAP0402")
      (libsource (lib "eagle-import") (part "CAPACITOR-0402"))
    )
    (comp (ref "C26")
      (value "330pF")
      (footprint "eagle-import:CAP0402")
      (libsource (lib "eagle-import") (part "CAPACITOR-0402"))
    )
    (comp (ref "C27")
      (value "330pF")
      (footprint "eagle-import:CAP0402")
      (libsource (lib "eagle-import") (part "CAPACITOR-0402"))
    )
    (comp (ref "FB2")
      (value "1uH")
      (footprint "eagle-import:IND0603")
      (libsource (lib "eagle-import") (part "FERRITE-0603"))
    )
    (comp (ref "R24")
      (value "0 Ohms")
      (footprint "eagle-import:RES0402")
      (libsource (lib "eagle-import") (part "RESISTOR-0402"))
    )
    (comp (ref "R25")
      (value "0 Ohms")
      (footprint "eagle-import:RES0402")
      (libsource (lib "eagle-import") (part "RESISTOR-0402"))
    )
    (comp (ref "R26")
      (value "1K Ohms")
      (footprint "eagle-import:RES0402")
      (libsource (lib "eagle-import") (part "RESISTOR-0402"))
    )
    (comp (ref "R27")
      (value "1K Ohms")
      (footprint "eagle-import:RES0402")
      (libsource (lib "eagle-import") (part "RESISTOR-0402"))
    )
    (comp (ref "R28")
      (value "2K Ohms")
      (footprint "eagle-import:RES0402")
      (libsource (lib "eagle-import") (part "RESISTOR-0402"))
    )
    (comp (ref "R29")
      (value "2K Ohms")
      (footprint "eagle-import:RES0402")
      (libsource (lib "eagle-import") (part "RESISTOR-0402"))
    )
    (comp (ref "R30")
      (value "100 Ohms")
      (footprint "eagle-import:RES0402")
      (libsource (lib "eagle-import") (part "RESISTOR-0402"))
    )
    (comp (ref "R31")
      (value "100 Ohms")
      (footprint "eagle-import:RES0402")
      (libsource (lib "eagle-import") (part "RESISTOR-0402"))
    )
    (comp (ref "R32")
      (value "1K Ohms")
      (footprint "eagle-import:RES0402")
      (libsource (lib "eagle-import") (part "RESISTOR-0402"))
    )
    (comp (ref "R33")
      (value "1K Ohms")
      (footprint "eagle-import:RES0402")
      (libsource (lib "eagle-import") (part "RESISTOR-0402"))
    )
    (comp (ref "R34")
      (value "10K Ohms")
      (footprint "eagle-import:RES0402")
      (libsource (lib "eagle-import") (part "RESISTOR-0402"))
    )
    (comp (ref "R35")
      (value "10K Ohms")
      (footprint "eagle-import:RES0402")
      (libsource (lib "eagle-import") (part "RESISTOR-0402"))
    )
    (comp (ref "R36")
      (value "2K Ohms")
      (footprint "eagle-import:RES0402")
      (libsource (lib "eagle-import") (part "RESISTOR-0402"))
    )
    (comp (ref "R37")
      (value "2K Ohms")
      (footprint "eagle-import:RES0402")
      (libsource (lib "eagle-import") (part "RESISTOR-0402"))
    )
    (comp (ref "R38")
      (value "DNP")
      (footprint "eagle-import:RES0402")
      (libsource (lib "eagle-import") (part "RESISTOR-0402"))
    )
    (comp (ref "R39")
      (value "DNP")
      (footprint "eagle-import:RES0402")
      (libsource (lib "eagle-import") (part "RESISTOR-0402"))
    )
    (comp (ref "U7")
      (value "MCP6V32-E/MNY")
      (footprint "eagle-import:TDFN8")
      (libsource (lib "eagle-import") (part "MCP6V32-E/MNY"))
    )
    (comp (ref "U8")
      (value "MCP4728-A0")
      (footprint "eagle-import:MSOP10")
      (libsource (lib "eagle-import") (part "MCP4728-A0"))
    )
    (comp (ref "U9")
      (value "MCP6V32-E/MNY")
      (footprint "eagle-import:TDFN8")
      (libsource (lib "eagle-import") (part "MCP6V32-E/MNY"))
    )
    (comp (ref "C49")
      (value "10uF")
      (footprint "eagle-import:CAP0402")
      (libsource (lib "eagle-import") (part "CAPACITOR-0402"))
    )
    (comp (ref "C50")
      (value "10uF")
      (footprint "eagle-import:CAP0402")
      (libsource (lib "eagle-import") (part "CAPACITOR-0402"))
    )
    (comp (ref "C51")
      (value "10uF")
      (footprint "eagle-import:CAP0402")
      (libsource (lib "eagle-import") (part "CAPACITOR-0402"))
    )
    (comp (ref "C52")
      (value "10uF")
      (footprint "eagle-import:CAP0402")
      (libsource (lib "eagle-import") (part "CAPACITOR-0402"))
    )
    (comp (ref "C53")
      (value "10nF")
      (footprint "eagle-import:CAP0402")
      (libsource (lib "eagle-import") (part "CAPACITOR-0402"))
    )
    (comp (ref "C54")
      (value "10nF")
      (footprint "eagle-import:CAP0402")
      (libsource (lib "eagle-import") (part "CAPACITOR-0402"))
    )
    (comp (ref "C55")
      (value "10nF")
      (footprint "eagle-import:CAP0402")
      (libsource (lib "eagle-import") (part "CAPACITOR-0402"))
    )
    (comp (ref "C56")
      (value "10nF")
      (footprint "eagle-import:CAP0402")
      (libsource (lib "eagle-import") (part "CAPACITOR-0402"))
    )
    (comp (ref "C57")
      (value "100pF")
      (footprint "eagle-import:CAP0402")
      (libsource (lib "eagle-import") (part "CAPACITOR-0402"))
    )
    (comp (ref "C58")
      (value "100pF")
      (footprint "eagle-import:CAP0402")
      (libsource (lib "eagle-import") (part "CAPACITOR-0402"))
    )
    (comp (ref "C59")
      (value "100pF")
      (footprint "eagle-import:CAP0402")
      (libsource (lib "eagle-import") (part "CAPACITOR-0402"))
    )
    (comp (ref "C60")
      (value "100pF")
      (footprint "eagle-import:CAP0402")
      (libsource (lib "eagle-import") (part "CAPACITOR-0402"))
    )
    (comp (ref "C61")
      (value "10uF")
      (footprint "eagle-import:CAP0402")
      (libsource (lib "eagle-import") (part "CAPACITOR-0402"))
    )
    (comp (ref "C62")
      (value "10uF")
      (footprint "eagle-import:CAP0402")
      (libsource (lib "eagle-import") (part "CAPACITOR-0402"))
    )
    (comp (ref "C63")
      (value "10uF")
      (footprint "eagle-import:CAP0402")
      (libsource (lib "eagle-import") (part "CAPACITOR-0402"))
    )
    (comp (ref "C64")
      (value "10nF")
      (footprint "eagle-import:CAP0402")
      (libsource (lib "eagle-import") (part "CAPACITOR-0402"))
    )
    (comp (ref "C65")
      (value "10nF")
      (footprint "eagle-import:CAP0402")
      (libsource (lib "eagle-import") (part "CAPACITOR-0402"))
    )
    (comp (ref "C66")
      (value "10nF")
      (footprint "eagle-import:CAP0402")
      (libsource (lib "eagle-import") (part "CAPACITOR-0402"))
    )
    (comp (ref "C67")
      (value "100pF")
      (footprint "eagle-import:CAP0402")
      (libsource (lib "eagle-import") (part "CAPACITOR-0402"))
    )
    (comp (ref "C68")
      (value "100pF")
      (footprint "eagle-import:CAP0402")
      (libsource (lib "eagle-import") (part "CAPACITOR-0402"))
    )
    (comp (ref "C69")
      (value "100pF")
      (footprint "eagle-import:CAP0402")
      (libsource (lib "eagle-import") (part "CAPACITOR-0402"))
    )
    (comp (ref "R46")
      (value "50 Ohms")
      (footprint "eagle-import:RES0402")
      (libsource (lib "eagle-import") (part "RESISTOR-0402"))
    )
    (comp (ref "R47")
      (value "1.1K Ohms")
      (footprint "eagle-import:RES0402")
      (libsource (lib "eagle-import") (part "RESISTOR-0402"))
    )
    (comp (ref "R48")
      (value "50 Ohms")
      (footprint "eagle-import:RES0402")
      (libsource (lib "eagle-import") (part "RESISTOR-0402"))
    )
    (comp (ref "RFCON3")
      (value "RFCON-U.FL")
      (footprint "eagle-import:U.FL")
      (libsource (lib "eagle-import") (part "RFCON-U.FL"))
    )
    (comp (ref "RFCON4")
      (value "RFCON-HK-R-SR2-SA")
      (footprint "eagle-import:HK-R-SR2-SA")
      (libsource (lib "eagle-import") (part "RFCON-HK-R-SR2-SA"))
    )
    (comp (ref "U13")
      (value "BFCV-2895+")
      (footprint "eagle-import:JV1210C")
      (libsource (lib "eagle-import") (part "BFCV-+2895"))
    )
    (comp (ref "U14")
      (value "QCN-34+")
      (footprint "eagle-import:FV1206-1")
      (libsource (lib "eagle-import") (part "QCN-34+"))
    )
    (comp (ref "U15")
      (value "ADMV1014")
      (footprint "eagle-import:LGA32")
      (libsource (lib "eagle-import") (part "ADMV1014"))
    )
    (comp (ref "C28")
      (value "10uF")
      (footprint "eagle-import:CAP0402")
      (libsource (lib "eagle-import") (part "CAPACITOR-0402"))
    )
    (comp (ref "C29")
      (value "10uF")
      (footprint "eagle-import:CAP0402")
      (libsource (lib "eagle-import") (part "CAPACITOR-0402"))
    )
    (comp (ref "C30")
      (value "10uF")
      (footprint "eagle-import:CAP0402")
      (libsource (lib "eagle-import") (part "CAPACITOR-0402"))
    )
    (comp (ref "C31")
      (value "10nF")
      (footprint "eagle-import:CAP0402")
      (libsource (lib "eagle-import") (part "CAPACITOR-0402"))
    )
    (comp (ref "C32")
      (value "10nF")
      (footprint "eagle-import:CAP0402")
      (libsource (lib "eagle-import") (part "CAPACITOR-0402"))
    )
    (comp (ref "C33")
      (value "10nF")
      (footprint "eagle-import:CAP0402")
      (libsource (lib "eagle-import") (part "CAPACITOR-0402"))
    )
    (comp (ref "C34")
      (value "100pF")
      (footprint "eagle-import:CAP0402")
      (libsource (lib "eagle-import") (part "CAPACITOR-0402"))
    )
    (comp (ref "C35")
      (value "100pF")
      (footprint "eagle-import:CAP0402")
      (libsource (lib "eagle-import") (part "CAPACITOR-0402"))
    )
    (comp (ref "C36")
      (value "100pF")
      (footprint "eagle-import:CAP0402")
      (libsource (lib "eagle-import") (part "CAPACITOR-0402"))
    )
    (comp (ref "C37")
      (value "10uF")
      (footprint "eagle-import:CAP0402")
      (libsource (lib "eagle-import") (part "CAPACITOR-0402"))
    )
    (comp (ref "C38")
      (value "10uF")
      (footprint "eagle-import:CAP0402")
      (libsource (lib "eagle-import") (part "CAPACITOR-0402"))
    )
    (comp (ref "C39")
      (value "10uF")
      (footprint "eagle-import:CAP0402")
      (libsource (lib "eagle-import") (part "CAPACITOR-0402"))
    )
    (comp (ref "C40")
      (value "10uF")
      (footprint "eagle-import:CAP0402")
      (libsource (lib "eagle-import") (part "CAPACITOR-0402"))
    )
    (comp (ref "C41")
      (value "10nF")
      (footprint "eagle-import:CAP0402")
      (libsource (lib "eagle-import") (part "CAPACITOR-0402"))
    )
    (comp (ref "C42")
      (value "10nF")
      (footprint "eagle-import:CAP0402")
      (libsource (lib "eagle-import") (part "CAPACITOR-0402"))
    )
    (comp (ref "C43")
      (value "10nF")
      (footprint "eagle-import:CAP0402")
      (libsource (lib "eagle-import") (part "CAPACITOR-0402"))
    )
    (comp (ref "C44")
      (value "10nF")
      (footprint "eagle-import:CAP0402")
      (libsource (lib "eagle-import") (part "CAPACITOR-0402"))
    )
    (comp (ref "C45")
      (value "100pF")
      (footprint "eagle-import:CAP0402")
      (libsource (lib "eagle-import") (part "CAPACITOR-0402"))
    )
    (comp (ref "C46")
      (value "100pF")
      (footprint "eagle-import:CAP0402")
      (libsource (lib "eagle-import") (part "CAPACITOR-0402"))
    )
    (comp (ref "C47")
      (value "100pF")
      (footprint "eagle-import:CAP0402")
      (libsource (lib "eagle-import") (part "CAPACITOR-0402"))
    )
    (comp (ref "C48")
      (value "100pF")
      (footprint "eagle-import:CAP0402")
      (libsource (lib "eagle-import") (part "CAPACITOR-0402"))
    )
    (comp (ref "R40")
      (value "50 Ohms")
      (footprint "eagle-import:RES0402")
      (libsource (lib "eagle-import") (part "RESISTOR-0402"))
    )
    (comp (ref "R41")
      (value "1K Ohms")
      (footprint "eagle-import:RES0402")
      (libsource (lib "eagle-import") (part "RESISTOR-0402"))
    )
    (comp (ref "R42")
      (value "1.1K Ohms")
      (footprint "eagle-import:RES0402")
      (libsource (lib "eagle-import") (part "RESISTOR-0402"))
    )
    (comp (ref "R43")
      (value "1K Ohms")
      (footprint "eagle-import:RES0402")
      (libsource (lib "eagle-import") (part "RESISTOR-0402"))
    )
    (comp (ref "R44")
      (value "1.1K Ohms")
      (footprint "eagle-import:RES0402")
      (libsource (lib "eagle-import") (part "RESISTOR-0402"))
    )
    (comp (ref "R45")
      (value "50 Ohms")
      (footprint "eagle-import:RES0402")
      (libsource (lib "eagle-import") (part "RESISTOR-0402"))
    )
    (comp (ref "RFCON1")
      (value "RFCON-U.FL")
      (footprint "eagle-import:U.FL")
      (libsource (lib "eagle-import") (part "RFCON-U.FL"))
    )
    (comp (ref "RFCON2")
      (value "RFCON-HK-R-SR2-SA")
      (footprint "eagle-import:HK-R-SR2-SA")
      (libsource (lib "eagle-import") (part "RFCON-HK-R-SR2-SA"))
    )
    (comp (ref "U10")
      (value "BFCV-2895+")
      (footprint "eagle-import:JV1210C")
      (libsource (lib "eagle-import") (part "BFCV-+2895"))
    )
    (comp (ref "U11")
      (value "QCN-34+")
      (footprint "eagle-import:FV1206-1")
      (libsource (lib "eagle-import") (part "QCN-34+"))
    )
    (comp (ref "U12")
      (value "ADMV1013")
      (footprint "eagle-import:LGA40")
      (libsource (lib "eagle-import") (part "ADMV1013"))
    )
    (comp (ref "C82")
      (value "100nF")
      (footprint "eagle-import:CAP0402")
      (libsource (lib "eagle-import") (part "CAPACITOR-0402"))
    )
    (comp (ref "C83")
      (value "10nF")
      (footprint "eagle-import:CAP0402")
      (libsource (lib "eagle-import") (part "CAPACITOR-0402"))
    )
    (comp (ref "C84")
      (value "100nF")
      (footprint "eagle-import:CAP0402")
      (libsource (lib "eagle-import") (part "CAPACITOR-0402"))
    )
    (comp (ref "C85")
      (value "100nF")
      (footprint "eagle-import:CAP0402")
      (libsource (lib "eagle-import") (part "CAPACITOR-0402"))
    )
    (comp (ref "C86")
      (value "100pF")
      (footprint "eagle-import:CAP0402")
      (libsource (lib "eagle-import") (part "CAPACITOR-0402"))
    )
    (comp (ref "C87")
      (value "100nF")
      (footprint "eagle-import:CAP0402")
      (libsource (lib "eagle-import") (part "CAPACITOR-0402"))
    )
    (comp (ref "C88")
      (value "100pF")
      (footprint "eagle-import:CAP0402")
      (libsource (lib "eagle-import") (part "CAPACITOR-0402"))
    )
    (comp (ref "C89")
      (value "100nF")
      (footprint "eagle-import:CAP0402")
      (libsource (lib "eagle-import") (part "CAPACITOR-0402"))
    )
    (comp (ref "C90")
      (value "100pF")
      (footprint "eagle-import:CAP0402")
      (libsource (lib "eagle-import") (part "CAPACITOR-0402"))
    )
    (comp (ref "C91")
      (value "100pF")
      (footprint "eagle-import:CAP0402")
      (libsource (lib "eagle-import") (part "CAPACITOR-0402"))
    )
    (comp (ref "R54")
      (value "1 Ohms")
      (footprint "eagle-import:RES0402")
      (libsource (lib "eagle-import") (part "RESISTOR-0402"))
    )
    (comp (ref "R55")
      (value "50 Ohms")
      (footprint "eagle-import:RES0402")
      (libsource (lib "eagle-import") (part "RESISTOR-0402"))
    )
    (comp (ref "RFCON6")
      (value "RFCON-U.FL")
      (footprint "eagle-import:U.FL")
      (libsource (lib "eagle-import") (part "RFCON-U.FL"))
    )
    (comp (ref "U19")
      (value "LTC5597")
      (footprint "eagle-import:DFN8_2X2")
      (libsource (lib "eagle-import") (part "LTC5597"))
    )
    (comp (ref "U20")
      (value "ADRF5019")
      (footprint "eagle-import:LFCSP16")
      (libsource (lib "eagle-import") (part "ADRF5019"))
    )
    (comp (ref "U21")
      (value "ADRF5019")
      (footprint "eagle-import:LFCSP16")
      (libsource (lib "eagle-import") (part "ADRF5019"))
    )
    (comp (ref "C10")
      (value "100nF")
      (footprint "eagle-import:CAP0402")
      (libsource (lib "eagle-import") (part "CAPACITOR-0402"))
    )
    (comp (ref "C11")
      (value "100nF")
      (footprint "eagle-import:CAP0402")
      (libsource (lib "eagle-import") (part "CAPACITOR-0402"))
    )
    (comp (ref "C12")
      (value "100nF")
      (footprint "eagle-import:CAP0402")
      (libsource (lib "eagle-import") (part "CAPACITOR-0402"))
    )
    (comp (ref "C13")
      (value "100nF")
      (footprint "eagle-import:CAP0402")
      (libsource (lib "eagle-import") (part "CAPACITOR-0402"))
    )
    (comp (ref "C14")
      (value "100nF")
      (footprint "eagle-import:CAP0402")
      (libsource (lib "eagle-import") (part "CAPACITOR-0402"))
    )
    (comp (ref "C15")
      (value "100nF")
      (footprint "eagle-import:CAP0402")
      (libsource (lib "eagle-import") (part "CAPACITOR-0402"))
    )
    (comp (ref "C16")
      (value "100nF")
      (footprint "eagle-import:CAP0402")
      (libsource (lib "eagle-import") (part "CAPACITOR-0402"))
    )
    (comp (ref "JP1")
      (value "PINHD-2X3")
      (footprint "eagle-import:2X03")
      (libsource (lib "eagle-import") (part "PINHD-2X3"))
    )
    (comp (ref "JP2")
      (value "PINHD-2X3")
      (footprint "eagle-import:2X03")
      (libsource (lib "eagle-import") (part "PINHD-2X3"))
    )
    (comp (ref "Q1")
      (value "AO3400")
      (footprint "eagle-import:SOT23")
      (libsource (lib "eagle-import") (part "AO3400"))
    )
    (comp (ref "Q2")
      (value "AO3400")
      (footprint "eagle-import:SOT23")
      (libsource (lib "eagle-import") (part "AO3400"))
    )
    (comp (ref "R10")
      (value "10K Ohms")
      (footprint "eagle-import:RES0402")
      (libsource (lib "eagle-import") (part "RESISTOR-0402"))
    )
    (comp (ref "R11")
      (value "10K Ohms")
      (footprint "eagle-import:RES0402")
      (libsource (lib "eagle-import") (part "RESISTOR-0402"))
    )
    (comp (ref "R12")
      (value "DNP")
      (footprint "eagle-import:RES0402")
      (libsource (lib "eagle-import") (part "RESISTOR-0402"))
    )
    (comp (ref "R13")
      (value "0 Ohms")
      (footprint "eagle-import:RES0402")
      (libsource (lib "eagle-import") (part "RESISTOR-0402"))
    )
    (comp (ref "R14")
      (value "DNP")
      (footprint "eagle-import:RES0402")
      (libsource (lib "eagle-import") (part "RESISTOR-0402"))
    )
    (comp (ref "R15")
      (value "10K Ohms")
      (footprint "eagle-import:RES0402")
      (libsource (lib "eagle-import") (part "RESISTOR-0402"))
    )
    (comp (ref "R16")
      (value "10K Ohms")
      (footprint "eagle-import:RES0402")
      (libsource (lib "eagle-import") (part "RESISTOR-0402"))
    )
    (comp (ref "R17")
      (value "10K Ohms")
      (footprint "eagle-import:RES0402")
      (libsource (lib "eagle-import") (part "RESISTOR-0402"))
    )
    (comp (ref "R18")
      (value "10K Ohms")
      (footprint "eagle-import:RES0402")
      (libsource (lib "eagle-import") (part "RESISTOR-0402"))
    )
    (comp (ref "R19")
      (value "10K Ohms")
      (footprint "eagle-import:RES0402")
      (libsource (lib "eagle-import") (part "RESISTOR-0402"))
    )
    (comp (ref "R20")
      (value "10K Ohms")
      (footprint "eagle-import:RES0402")
      (libsource (lib "eagle-import") (part "RESISTOR-0402"))
    )
    (comp (ref "R21")
      (value "DNP")
      (footprint "eagle-import:RES0402")
      (libsource (lib "eagle-import") (part "RESISTOR-0402"))
    )
    (comp (ref "R22")
      (value "0 Ohms")
      (footprint "eagle-import:RES0402")
      (libsource (lib "eagle-import") (part "RESISTOR-0402"))
    )
    (comp (ref "R23")
      (value "DNP")
      (footprint "eagle-import:RES0402")
      (libsource (lib "eagle-import") (part "RESISTOR-0402"))
    )
    (comp (ref "U2")
      (value "MCP9802-A0")
      (footprint "eagle-import:SOT23-5")
      (libsource (lib "eagle-import") (part "MCP9802-A0"))
    )
    (comp (ref "U3")
      (value "MCP9802-A1")
      (footprint "eagle-import:SOT23-5")
      (libsource (lib "eagle-import") (part "MCP9802-A1"))
    )
    (comp (ref "U4")
      (value "MCP9802-A3")
      (footprint "eagle-import:SOT23-5")
      (libsource (lib "eagle-import") (part "MCP9802-A3"))
    )
    (comp (ref "U5")
      (value "FXL4TD245BQX")
      (footprint "eagle-import:DQFN16")
      (libsource (lib "eagle-import") (part "FXL4TD245BQX"))
    )
    (comp (ref "U6")
      (value "FXL4TD245BQX")
      (footprint "eagle-import:DQFN16")
      (libsource (lib "eagle-import") (part "FXL4TD245BQX"))
    )
    (comp (ref "C149")
      (value "10uF")
      (footprint "eagle-import:CAP0603")
      (libsource (lib "eagle-import") (part "CAPACITOR-0603"))
    )
    (comp (ref "C150")
      (value "1uF")
      (footprint "eagle-import:CAP0402")
      (libsource (lib "eagle-import") (part "CAPACITOR-0402"))
    )
    (comp (ref "C151")
      (value "1uF")
      (footprint "eagle-import:CAP0402")
      (libsource (lib "eagle-import") (part "CAPACITOR-0402"))
    )
    (comp (ref "C152")
      (value "1uF")
      (footprint "eagle-import:CAP0402")
      (libsource (lib "eagle-import") (part "CAPACITOR-0402"))
    )
    (comp (ref "C153")
      (value "100nF")
      (footprint "eagle-import:CAP0402")
      (libsource (lib "eagle-import") (part "CAPACITOR-0402"))
    )
    (comp (ref "C154")
      (value "100nF")
      (footprint "eagle-import:CAP0402")
      (libsource (lib "eagle-import") (part "CAPACITOR-0402"))
    )
    (comp (ref "C155")
      (value "100nF")
      (footprint "eagle-import:CAP0402")
      (libsource (lib "eagle-import") (part "CAPACITOR-0402"))
    )
    (comp (ref "C156")
      (value "1uF")
      (footprint "eagle-import:CAP0402")
      (libsource (lib "eagle-import") (part "CAPACITOR-0402"))
    )
    (comp (ref "C157")
      (value "1uF")
      (footprint "eagle-import:CAP0402")
      (libsource (lib "eagle-import") (part "CAPACITOR-0402"))
    )
    (comp (ref "C158")
      (value "1uF")
      (footprint "eagle-import:CAP0402")
      (libsource (lib "eagle-import") (part "CAPACITOR-0402"))
    )
    (comp (ref "C159")
      (value "10uF")
      (footprint "eagle-import:CAP0402")
      (libsource (lib "eagle-import") (part "CAPACITOR-0402"))
    )
    (comp (ref "C160")
      (value "10uF")
      (footprint "eagle-import:CAP0402")
      (libsource (lib "eagle-import") (part "CAPACITOR-0402"))
    )
    (comp (ref "C161")
      (value "10uF")
      (footprint "eagle-import:CAP0402")
      (libsource (lib "eagle-import") (part "CAPACITOR-0402"))
    )
    (comp (ref "C162")
      (value "10uF")
      (footprint "eagle-import:CAP0603")
      (libsource (lib "eagle-import") (part "CAPACITOR-0603"))
    )
    (comp (ref "C163")
      (value "1uF")
      (footprint "eagle-import:CAP0402")
      (libsource (lib "eagle-import") (part "CAPACITOR-0402"))
    )
    (comp (ref "C164")
      (value "1uF")
      (footprint "eagle-import:CAP0402")
      (libsource (lib "eagle-import") (part "CAPACITOR-0402"))
    )
    (comp (ref "C165")
      (value "100nF")
      (footprint "eagle-import:CAP0402")
      (libsource (lib "eagle-import") (part "CAPACITOR-0402"))
    )
    (comp (ref "C166")
      (value "100nF")
      (footprint "eagle-import:CAP0402")
      (libsource (lib "eagle-import") (part "CAPACITOR-0402"))
    )
    (comp (ref "C167")
      (value "10nF")
      (footprint "eagle-import:CAP0402")
      (libsource (lib "eagle-import") (part "CAPACITOR-0402"))
    )
    (comp (ref "C168")
      (value "10nF")
      (footprint "eagle-import:CAP0402")
      (libsource (lib "eagle-import") (part "CAPACITOR-0402"))
    )
    (comp (ref "C169")
      (value "1uF")
      (footprint "eagle-import:CAP0402")
      (libsource (lib "eagle-import") (part "CAPACITOR-0402"))
    )
    (comp (ref "C170")
      (value "1uF")
      (footprint "eagle-import:CAP0402")
      (libsource (lib "eagle-import") (part "CAPACITOR-0402"))
    )
    (comp (ref "C171")
      (value "10uF")
      (footprint "eagle-import:CAP0402")
      (libsource (lib "eagle-import") (part "CAPACITOR-0402"))
    )
    (comp (ref "C172")
      (value "10uF")
      (footprint "eagle-import:CAP0402")
      (libsource (lib "eagle-import") (part "CAPACITOR-0402"))
    )
    (comp (ref "JP3")
      (value "PINHD-2X3")
      (footprint "eagle-import:2X03")
      (libsource (lib "eagle-import") (part "PINHD-2X3"))
    )
    (comp (ref "R74")
      (value "0 Ohms")
      (footprint "eagle-import:RES0402")
      (libsource (lib "eagle-import") (part "RESISTOR-0402"))
    )
    (comp (ref "R75")
      (value "10K Ohms")
      (footprint "eagle-import:RES0402")
      (libsource (lib "eagle-import") (part "RESISTOR-0402"))
    )
    (comp (ref "R76")
      (value "10K Ohms")
      (footprint "eagle-import:RES0402")
      (libsource (lib "eagle-import") (part "RESISTOR-0402"))
    )
    (comp (ref "R77")
      (value "10K Ohms")
      (footprint "eagle-import:RES0402")
      (libsource (lib "eagle-import") (part "RESISTOR-0402"))
    )
    (comp (ref "R78")
      (value "10K Ohms")
      (footprint "eagle-import:RES0402")
      (libsource (lib "eagle-import") (part "RESISTOR-0402"))
    )
    (comp (ref "U30")
      (value "ADP7142AUJZ-1.8")
      (footprint "eagle-import:SOT23-5")
      (libsource (lib "eagle-import") (part "ADP7142AUJZ-1.8"))
    )
    (comp (ref "U31")
      (value "ADP7142AUJZ-1.8")
      (footprint "eagle-import:SOT23-5")
      (libsource (lib "eagle-import") (part "ADP7142AUJZ-1.8"))
    )
    (comp (ref "U32")
      (value "ADP7102ACPZ-1.5")
      (footprint "eagle-import:LFCSP8_3X3")
      (libsource (lib "eagle-import") (part "ADP7102ACPZ-1.5"))
    )
    (comp (ref "U33")
      (value "ADM7171ACPZ-3.3")
      (footprint "eagle-import:LFCSP8_3X3")
      (libsource (lib "eagle-import") (part "ADM7171ACPZ-3.3"))
    )
    (comp (ref "U34")
      (value "ADM7171ACPZ-3.3")
      (footprint "eagle-import:LFCSP8_3X3")
      (libsource (lib "eagle-import") (part "ADM7171ACPZ-3.3"))
    )
    (comp (ref "C70")
      (value "2.2pF")
      (footprint "eagle-import:CAP0402")
      (libsource (lib "eagle-import") (part "CAPACITOR-0402"))
    )
    (comp (ref "C71")
      (value "10uF")
      (footprint "eagle-import:CAP0402")
      (libsource (lib "eagle-import") (part "CAPACITOR-0402"))
    )
    (comp (ref "C72")
      (value "2.2pF")
      (footprint "eagle-import:CAP0402")
      (libsource (lib "eagle-import") (part "CAPACITOR-0402"))
    )
    (comp (ref "C73")
      (value "2.2pF")
      (footprint "eagle-import:CAP0402")
      (libsource (lib "eagle-import") (part "CAPACITOR-0402"))
    )
    (comp (ref "C74")
      (value "100nF")
      (footprint "eagle-import:CAP0402")
      (libsource (lib "eagle-import") (part "CAPACITOR-0402"))
    )
    (comp (ref "C75")
      (value "100pF")
      (footprint "eagle-import:CAP0402")
      (libsource (lib "eagle-import") (part "CAPACITOR-0402"))
    )
    (comp (ref "C76")
      (value "100pF")
      (footprint "eagle-import:CAP0402")
      (libsource (lib "eagle-import") (part "CAPACITOR-0402"))
    )
    (comp (ref "C77")
      (value "100nF")
      (footprint "eagle-import:CAP0402")
      (libsource (lib "eagle-import") (part "CAPACITOR-0402"))
    )
    (comp (ref "C78")
      (value "2.2pF")
      (footprint "eagle-import:CAP0402")
      (libsource (lib "eagle-import") (part "CAPACITOR-0402"))
    )
    (comp (ref "C79")
      (value "10uF")
      (footprint "eagle-import:CAP0402")
      (libsource (lib "eagle-import") (part "CAPACITOR-0402"))
    )
    (comp (ref "C80")
      (value "2.2pF")
      (footprint "eagle-import:CAP0402")
      (libsource (lib "eagle-import") (part "CAPACITOR-0402"))
    )
    (comp (ref "C81")
      (value "2.2pF")
      (footprint "eagle-import:CAP0402")
      (libsource (lib "eagle-import") (part "CAPACITOR-0402"))
    )
    (comp (ref "L1")
      (value "8.8nH")
      (footprint "eagle-import:IND0402")
      (libsource (lib "eagle-import") (part "INDUCTOR-0402"))
    )
    (comp (ref "L2")
      (value "8.8nH")
      (footprint "eagle-import:IND0402")
      (libsource (lib "eagle-import") (part "INDUCTOR-0402"))
    )
    (comp (ref "L3")
      (value "8.8nH")
      (footprint "eagle-import:IND0402")
      (libsource (lib "eagle-import") (part "INDUCTOR-0402"))
    )
    (comp (ref "L4")
      (value "8.8nH")
      (footprint "eagle-import:IND0402")
      (libsource (lib "eagle-import") (part "INDUCTOR-0402"))
    )
    (comp (ref "R49")
      (value "0 Ohms")
      (footprint "eagle-import:RES0402")
      (libsource (lib "eagle-import") (part "RESISTOR-0402"))
    )
    (comp (ref "R50")
      (value "0 Ohms")
      (footprint "eagle-import:RES0402")
      (libsource (lib "eagle-import") (part "RESISTOR-0402"))
    )
    (comp (ref "R51")
      (value "50 Ohms")
      (footprint "eagle-import:RES0402")
      (libsource (lib "eagle-import") (part "RESISTOR-0402"))
    )
    (comp (ref "R52")
      (value "50 Ohms")
      (footprint "eagle-import:RES0402")
      (libsource (lib "eagle-import") (part "RESISTOR-0402"))
    )
    (comp (ref "R53")
      (value "50 Ohms")
      (footprint "eagle-import:RES0402")
      (libsource (lib "eagle-import") (part "RESISTOR-0402"))
    )
    (comp (ref "RFCON5")
      (value "RFCON-U.FL")
      (footprint "eagle-import:U.FL")
      (libsource (lib "eagle-import") (part "RFCON-U.FL"))
    )
    (comp (ref "U16")
      (value "PMA2-123LN+")
      (footprint "eagle-import:MC1631-1")
      (libsource (lib "eagle-import") (part "PMA2-123LN+"))
    )
    (comp (ref "U17")
      (value "ADRF5720")
      (footprint "eagle-import:LGA24")
      (libsource (lib "eagle-import") (part "ADRF5720"))
    )
    (comp (ref "U18")
      (value "PMA2-123LN+")
      (footprint "eagle-import:MC1631-1")
      (libsource (lib "eagle-import") (part "PMA2-123LN+"))
    )
    (comp (ref "C1")
      (value "100nF")
      (footprint "eagle-import:CAP0402")
      (libsource (lib "eagle-import") (part "CAPACITOR-0402"))
    )
    (comp (ref "C2")
      (value "100nF")
      (footprint "eagle-import:CAP0402")
      (libsource (lib "eagle-import") (part "CAPACITOR-0402"))
    )
    (comp (ref "C3")
      (value "100nF")
      (footprint "eagle-import:CAP0402")
      (libsource (lib "eagle-import") (part "CAPACITOR-0402"))
    )
    (comp (ref "C4")
      (value "100nF")
      (footprint "eagle-import:CAP0402")
      (libsource (lib "eagle-import") (part "CAPACITOR-0402"))
    )
    (comp (ref "C5")
      (value "100nF")
      (footprint "eagle-import:CAP0402")
      (libsource (lib "eagle-import") (part "CAPACITOR-0402"))
    )
    (comp (ref "C6")
      (value "1uF")
      (footprint "eagle-import:CAP0402")
      (libsource (lib "eagle-import") (part "CAPACITOR-0402"))
    )
    (comp (ref "C7")
      (value "10uF")
      (footprint "eagle-import:CAP0402")
      (libsource (lib "eagle-import") (part "CAPACITOR-0402"))
    )
    (comp (ref "C8")
      (value "100nF")
      (footprint "eagle-import:CAP0402")
      (libsource (lib "eagle-import") (part "CAPACITOR-0402"))
    )
    (comp (ref "C9")
      (value "1uF")
      (footprint "eagle-import:CAP0402")
      (libsource (lib "eagle-import") (part "CAPACITOR-0402"))
    )
    (comp (ref "D1")
      (value "LED0603")
      (footprint "eagle-import:0603")
      (fields (field (name "COLOR") "RED"))
      (libsource (lib "eagle-import") (part "LED0603"))
    )
    (comp (ref "D2")
      (value "LED0603")
      (footprint "eagle-import:0603")
      (fields (field (name "COLOR") "BLUE"))
      (libsource (lib "eagle-import") (part "LED0603"))
    )
    (comp (ref "FB1")
      (value "1uH")
      (footprint "eagle-import:IND0603")
      (libsource (lib "eagle-import") (part "FERRITE-0603"))
    )
    (comp (ref "LOGO1")
      (value "JSILVA-5MM")
      (footprint "eagle-import:JSILVA_5MM")
      (libsource (lib "eagle-import") (part "JSILVA-5MM"))
    )
    (comp (ref "R1")
      (value "4.7K Ohms")
      (footprint "eagle-import:RES0402")
      (libsource (lib "eagle-import") (part "RESISTOR-0402"))
    )
    (comp (ref "R2")
      (value "4.7K Ohms")
      (footprint "eagle-import:RES0402")
      (libsource (lib "eagle-import") (part "RESISTOR-0402"))
    )
    (comp (ref "R3")
      (value "4.7K Ohms")
      (footprint "eagle-import:RES0402")
      (libsource (lib "eagle-import") (part "RESISTOR-0402"))
    )
    (comp (ref "R4")
      (value "4.7K Ohms")
      (footprint "eagle-import:RES0402")
      (libsource (lib "eagle-import") (part "RESISTOR-0402"))
    )
    (comp (ref "R5")
      (value "4.7K Ohms")
      (footprint "eagle-import:RES0402")
      (libsource (lib "eagle-import") (part "RESISTOR-0402"))
    )
    (comp (ref "R6")
      (value "1K Ohms")
      (footprint "eagle-import:RES0402")
      (libsource (lib "eagle-import") (part "RESISTOR-0402"))
    )
    (comp (ref "R7")
      (value "4.7K Ohms")
      (footprint "eagle-import:RES0402")
      (libsource (lib "eagle-import") (part "RESISTOR-0402"))
    )
    (comp (ref "R8")
      (value "1K Ohms")
      (footprint "eagle-import:RES0402")
      (libsource (lib "eagle-import") (part "RESISTOR-0402"))
    )
    (comp (ref "R9")
      (value "10K Ohms")
      (footprint "eagle-import:RES0402")
      (libsource (lib "eagle-import") (part "RESISTOR-0402"))
    )
    (comp (ref "TC1")
      (value "TC2050-IDC")
      (footprint "eagle-import:TC2050-IDC")
      (libsource (lib "eagle-import") (part "TC2050-IDC"))
    )
    (comp (ref "U1")
      (value "EFM32GG11B420F2048GQ64")
      (footprint "eagle-import:QFP64")
      (libsource (lib "eagle-import") (part "EFM32GG11B4Q6420F2048G"))
    )
  )
  (nets
    (net (code "1") (name "-3V3_RF_GP") (class "Default")
      (node (ref "C100") (pin "1") (pinfunction "C1_1") (pintype "passive"))
      (node (ref "C101") (pin "1") (pinfunction "C1_1") (pintype "passive"))
      (node (ref "C146") (pin "1") (pinfunction "C1_1") (pintype "passive"))
      (node (ref "C147") (pin "1") (pinfunction "C1_1") (pintype "passive"))
      (node (ref "C148") (pin "1") (pinfunction "C1_1") (pintype "passive"))
      (node (ref "C74") (pin "1") (pinfunction "C1_1") (pintype "passive"))
      (node (ref "C75") (pin "1") (pinfunction "C1_1") (pintype "passive"))
      (node (ref "C87") (pin "1") (pinfunction "C1_1") (pintype "passive"))
      (node (ref "C89") (pin "1") (pinfunction "C1_1") (pintype "passive"))
      (node (ref "C90") (pin "1") (pinfunction "C1_1") (pintype "passive"))
      (node (ref "C91") (pin "1") (pinfunction "C1_1") (pintype "passive"))
      (node (ref "C97") (pin "1") (pinfunction "C1_1") (pintype "passive"))
      (node (ref "C99") (pin "1") (pinfunction "C1_1") (pintype "passive"))
      (node (ref "U17") (pin "17") (pinfunction "VSS_17") (pintype "bidirectional"))
      (node (ref "U20") (pin "9") (pinfunction "VSS_9") (pintype "bidirectional"))
      (node (ref "U21") (pin "9") (pinfunction "VSS_9") (pintype "bidirectional"))
      (node (ref "U23") (pin "9") (pinfunction "VSS_9") (pintype "bidirectional"))
      (node (ref "U24") (pin "9") (pinfunction "VSS_9") (pintype "bidirectional"))
      (node (ref "U29") (pin "1") (pinfunction "OUT_1") (pintype "bidirectional"))
    )
    (net (code "2") (name "1V5_RF_RX") (class "Default")
      (node (ref "C158") (pin "1") (pinfunction "C1_1") (pintype "passive"))
      (node (ref "C161") (pin "1") (pinfunction "C1_1") (pintype "passive"))
      (node (ref "C52") (pin "1") (pinfunction "C1_1") (pintype "passive"))
      (node (ref "C56") (pin "1") (pinfunction "C1_1") (pintype "passive"))
      (node (ref "C60") (pin "1") (pinfunction "C1_1") (pintype "passive"))
      (node (ref "U15") (pin "20") (pinfunction "VCC_LNA_1P5_20") (pintype "power_in"))
      (node (ref "U32") (pin "1") (pinfunction "VOUT_1") (pintype "bidirectional"))
      (node (ref "U32") (pin "2") (pinfunction "SENSE_2") (pintype "bidirectional"))
    )
    (net (code "3") (name "1V8_RF_RX") (class "Default")
      (node (ref "C15") (pin "1") (pinfunction "C1_1") (pintype "passive"))
      (node (ref "C157") (pin "1") (pinfunction "C1_1") (pintype "passive"))
      (node (ref "C160") (pin "1") (pinfunction "C1_1") (pintype "passive"))
      (node (ref "C49") (pin "1") (pinfunction "C1_1") (pintype "passive"))
      (node (ref "C53") (pin "1") (pinfunction "C1_1") (pintype "passive"))
      (node (ref "C57") (pin "1") (pinfunction "C1_1") (pintype "passive"))
      (node (ref "C61") (pin "1") (pinfunction "C1_1") (pintype "passive"))
      (node (ref "C64") (pin "1") (pinfunction "C1_1") (pintype "passive"))
      (node (ref "C67") (pin "1") (pinfunction "C1_1") (pintype "passive"))
      (node (ref "R16") (pin "2") (pinfunction "2_2") (pintype "passive"))
      (node (ref "R17") (pin "2") (pinfunction "2_2") (pintype "passive"))
      (node (ref "R74") (pin "2") (pinfunction "2_2") (pintype "passive"))
      (node (ref "U15") (pin "15") (pinfunction "VCC_VVA_15") (pintype "power_in"))
      (node (ref "U15") (pin "30") (pinfunction "DVDD_30") (pintype "power_in"))
      (node (ref "U31") (pin "4") (pinfunction "SENSE/ADJ_4") (pintype "bidirectional"))
      (node (ref "U31") (pin "5") (pinfunction "VOUT_5") (pintype "bidirectional"))
      (node (ref "U6") (pin "16") (pinfunction "VCCB_16") (pintype "bidirectional"))
    )
    (net (code "4") (name "1V8_RF_TX") (class "Default")
      (node (ref "C13") (pin "1") (pinfunction "C1_1") (pintype "passive"))
      (node (ref "C156") (pin "1") (pinfunction "C1_1") (pintype "passive"))
      (node (ref "C159") (pin "1") (pinfunction "C1_1") (pintype "passive"))
      (node (ref "C28") (pin "1") (pinfunction "C1_1") (pintype "passive"))
      (node (ref "C31") (pin "1") (pinfunction "C1_1") (pintype "passive"))
      (node (ref "C34") (pin "1") (pinfunction "C1_1") (pintype "passive"))
      (node (ref "C37") (pin "1") (pinfunction "C1_1") (pintype "passive"))
      (node (ref "C41") (pin "1") (pinfunction "C1_1") (pintype "passive"))
      (node (ref "C45") (pin "1") (pinfunction "C1_1") (pintype "passive"))
      (node (ref "R10") (pin "2") (pinfunction "2_2") (pintype "passive"))
      (node (ref "R20") (pin "2") (pinfunction "2_2") (pintype "passive"))
      (node (ref "R74") (pin "1") (pinfunction "1_1") (pintype "passive"))
      (node (ref "U12") (pin "14") (pinfunction "VCC_VVA_14") (pintype "power_in"))
      (node (ref "U12") (pin "2") (pinfunction "DVDD_2") (pintype "power_in"))
      (node (ref "U30") (pin "4") (pinfunction "SENSE/ADJ_4") (pintype "bidirectional"))
      (node (ref "U30") (pin "5") (pinfunction "VOUT_5") (pintype "bidirectional"))
      (node (ref "U5") (pin "16") (pinfunction "VCCB_16") (pintype "bidirectional"))
    )
    (net (code "5") (name "2V5") (class "Default")
      (node (ref "JP3") (pin "2") (pinfunction "S_2") (pintype "passive"))
    )
    (net (code "6") (name "3V3") (class "Default")
      (node (ref "C1") (pin "1") (pinfunction "C1_1") (pintype "passive"))
      (node (ref "C14") (pin "1") (pinfunction "C1_1") (pintype "passive"))
      (node (ref "C149") (pin "1") (pinfunction "C1_1") (pintype "passive"))
      (node (ref "C150") (pin "1") (pinfunction "C1_1") (pintype "passive"))
      (node (ref "C151") (pin "1") (pinfunction "C1_1") (pintype "passive"))
      (node (ref "C153") (pin "1") (pinfunction "C1_1") (pintype "passive"))
      (node (ref "C154") (pin "1") (pinfunction "C1_1") (pintype "passive"))
      (node (ref "C16") (pin "1") (pinfunction "C1_1") (pintype "passive"))
      (node (ref "C17") (pin "1") (pinfunction "C1_1") (pintype "passive"))
      (node (ref "C2") (pin "1") (pinfunction "C1_1") (pintype "passive"))
      (node (ref "C3") (pin "1") (pinfunction "C1_1") (pintype "passive"))
      (node (ref "C4") (pin "1") (pinfunction "C1_1") (pintype "passive"))
      (node (ref "C5") (pin "1") (pinfunction "C1_1") (pintype "passive"))
      (node (ref "C6") (pin "1") (pinfunction "C1_1") (pintype "passive"))
      (node (ref "FB1") (pin "1") (pinfunction "1_1") (pintype "passive"))
      (node (ref "FB2") (pin "1") (pinfunction "1_1") (pintype "passive"))
      (node (ref "JP3") (pin "1") (pinfunction "S_1") (pintype "passive"))
      (node (ref "R11") (pin "2") (pinfunction "2_2") (pintype "passive"))
      (node (ref "R14") (pin "2") (pinfunction "2_2") (pintype "passive"))
      (node (ref "R18") (pin "2") (pinfunction "2_2") (pintype "passive"))
      (node (ref "R3") (pin "2") (pinfunction "2_2") (pintype "passive"))
      (node (ref "R4") (pin "2") (pinfunction "2_2") (pintype "passive"))
      (node (ref "R5") (pin "2") (pinfunction "2_2") (pintype "passive"))
      (node (ref "R7") (pin "2") (pinfunction "2_2") (pintype "passive"))
      (node (ref "R9") (pin "2") (pinfunction "2_2") (pintype "passive"))
      (node (ref "TC1") (pin "1") (pinfunction "S_1") (pintype "passive"))
      (node (ref "U1") (pin "26") (pinfunction "IOVDD0_26") (pintype "bidirectional"))
      (node (ref "U1") (pin "39") (pinfunction "DVDD_39") (pintype "bidirectional"))
      (node (ref "U1") (pin "45") (pinfunction "VREGI_45") (pintype "bidirectional"))
      (node (ref "U1") (pin "46") (pinfunction "VREGO_46") (pintype "bidirectional"))
      (node (ref "U1") (pin "52") (pinfunction "VBUS_52") (pintype "bidirectional"))
      (node (ref "U1") (pin "55") (pinfunction "IOVDD0_55") (pintype "bidirectional"))
      (node (ref "U1") (pin "7") (pinfunction "IOVDD0_7") (pintype "bidirectional"))
      (node (ref "U30") (pin "1") (pinfunction "VIN_1") (pintype "bidirectional"))
      (node (ref "U31") (pin "1") (pinfunction "VIN_1") (pintype "bidirectional"))
      (node (ref "U5") (pin "1") (pinfunction "VCCA_1") (pintype "bidirectional"))
      (node (ref "U5") (pin "10") (pinfunction "T/~{R}2_10") (pintype "bidirectional"))
      (node (ref "U5") (pin "15") (pinfunction "T/~{R}1_15") (pintype "bidirectional"))
      (node (ref "U5") (pin "2") (pinfunction "T/~{R}0_2") (pintype "bidirectional"))
      (node (ref "U6") (pin "1") (pinfunction "VCCA_1") (pintype "bidirectional"))
      (node (ref "U6") (pin "10") (pinfunction "T/~{R}2_10") (pintype "bidirectional"))
      (node (ref "U6") (pin "15") (pinfunction "T/~{R}1_15") (pintype "bidirectional"))
      (node (ref "U6") (pin "2") (pinfunction "T/~{R}0_2") (pintype "bidirectional"))
    )
    (net (code "7") (name "3V3_DAC_OPA") (class "Default")
      (node (ref "C18") (pin "1") (pinfunction "C1_1") (pintype "passive"))
      (node (ref "C21") (pin "1") (pinfunction "C1_1") (pintype "passive"))
      (node (ref "C24") (pin "1") (pinfunction "C1_1") (pintype "passive"))
      (node (ref "C25") (pin "1") (pinfunction "C1_1") (pintype "passive"))
      (node (ref "FB2") (pin "2") (pinfunction "2_2") (pintype "passive"))
      (node (ref "U7") (pin "8") (pinfunction "V+_8") (pintype "power_in"))
      (node (ref "U8") (pin "1") (pinfunction "VDD_1") (pintype "bidirectional"))
      (node (ref "U9") (pin "8") (pinfunction "V+_8") (pintype "power_in"))
    )
    (net (code "8") (name "3V3_RF_GP") (class "Default")
      (node (ref "C137") (pin "1") (pinfunction "C1_1") (pintype "passive"))
      (node (ref "C140") (pin "1") (pinfunction "C1_1") (pintype "passive"))
      (node (ref "C143") (pin "1") (pinfunction "C1_1") (pintype "passive"))
      (node (ref "C144") (pin "1") (pinfunction "C1_1") (pintype "passive"))
      (node (ref "C76") (pin "1") (pinfunction "C1_1") (pintype "passive"))
      (node (ref "C77") (pin "1") (pinfunction "C1_1") (pintype "passive"))
      (node (ref "C84") (pin "1") (pinfunction "C1_1") (pintype "passive"))
      (node (ref "C85") (pin "1") (pinfunction "C1_1") (pintype "passive"))
      (node (ref "C86") (pin "1") (pinfunction "C1_1") (pintype "passive"))
      (node (ref "C88") (pin "1") (pinfunction "C1_1") (pintype "passive"))
      (node (ref "C94") (pin "1") (pinfunction "C1_1") (pintype "passive"))
      (node (ref "C95") (pin "1") (pinfunction "C1_1") (pintype "passive"))
      (node (ref "C96") (pin "1") (pinfunction "C1_1") (pintype "passive"))
      (node (ref "C98") (pin "1") (pinfunction "C1_1") (pintype "passive"))
      (node (ref "R54") (pin "2") (pinfunction "2_2") (pintype "passive"))
      (node (ref "R56") (pin "2") (pinfunction "2_2") (pintype "passive"))
      (node (ref "U17") (pin "18") (pinfunction "VDD_18") (pintype "bidirectional"))
      (node (ref "U17") (pin "2") (pinfunction "PS_2") (pintype "bidirectional"))
      (node (ref "U19") (pin "8") (pinfunction "EN_8") (pintype "bidirectional"))
      (node (ref "U20") (pin "12") (pinfunction "VDD_12") (pintype "bidirectional"))
      (node (ref "U21") (pin "12") (pinfunction "VDD_12") (pintype "bidirectional"))
      (node (ref "U22") (pin "8") (pinfunction "EN_8") (pintype "bidirectional"))
      (node (ref "U23") (pin "12") (pinfunction "VDD_12") (pintype "bidirectional"))
      (node (ref "U24") (pin "12") (pinfunction "VDD_12") (pintype "bidirectional"))
      (node (ref "U26") (pin "4") (pinfunction "SENSE/ADJ_4") (pintype "bidirectional"))
      (node (ref "U26") (pin "5") (pinfunction "VOUT_5") (pintype "bidirectional"))
      (node (ref "U29") (pin "2") (pinfunction "IN_2") (pintype "bidirectional"))
    )
    (net (code "9") (name "3V3_RF_RX") (class "Default")
      (node (ref "C170") (pin "1") (pinfunction "C1_1") (pintype "passive"))
      (node (ref "C172") (pin "1") (pinfunction "C1_1") (pintype "passive"))
      (node (ref "C50") (pin "1") (pinfunction "C1_1") (pintype "passive"))
      (node (ref "C51") (pin "1") (pinfunction "C1_1") (pintype "passive"))
      (node (ref "C54") (pin "1") (pinfunction "C1_1") (pintype "passive"))
      (node (ref "C55") (pin "1") (pinfunction "C1_1") (pintype "passive"))
      (node (ref "C58") (pin "1") (pinfunction "C1_1") (pintype "passive"))
      (node (ref "C59") (pin "1") (pinfunction "C1_1") (pintype "passive"))
      (node (ref "C62") (pin "1") (pinfunction "C1_1") (pintype "passive"))
      (node (ref "C63") (pin "1") (pinfunction "C1_1") (pintype "passive"))
      (node (ref "C65") (pin "1") (pinfunction "C1_1") (pintype "passive"))
      (node (ref "C66") (pin "1") (pinfunction "C1_1") (pintype "passive"))
      (node (ref "C68") (pin "1") (pinfunction "C1_1") (pintype "passive"))
      (node (ref "C69") (pin "1") (pinfunction "C1_1") (pintype "passive"))
      (node (ref "U15") (pin "10") (pinfunction "VCC_IF_BB_10") (pintype "power_in"))
      (node (ref "U15") (pin "12") (pinfunction "VCC_VGA_12") (pintype "power_in"))
      (node (ref "U15") (pin "16") (pinfunction "VCC_LNA_3P3_16") (pintype "power_in"))
      (node (ref "U15") (pin "21") (pinfunction "VCC_BG_21") (pintype "power_in"))
      (node (ref "U15") (pin "24") (pinfunction "VCC_QUAD_24") (pintype "power_in"))
      (node (ref "U15") (pin "29") (pinfunction "VCC_MIXER_29") (pintype "power_in"))
      (node (ref "U34") (pin "1") (pinfunction "VOUT_1") (pintype "bidirectional"))
      (node (ref "U34") (pin "2") (pinfunction "VOUT_2") (pintype "bidirectional"))
      (node (ref "U34") (pin "3") (pinfunction "SENSE_3") (pintype "bidirectional"))
    )
    (net (code "10") (name "3V3_RF_TX") (class "Default")
      (node (ref "C169") (pin "1") (pinfunction "C1_1") (pintype "passive"))
      (node (ref "C171") (pin "1") (pinfunction "C1_1") (pintype "passive"))
      (node (ref "C29") (pin "1") (pinfunction "C1_1") (pintype "passive"))
      (node (ref "C30") (pin "1") (pinfunction "C1_1") (pintype "passive"))
      (node (ref "C32") (pin "1") (pinfunction "C1_1") (pintype "passive"))
      (node (ref "C33") (pin "1") (pinfunction "C1_1") (pintype "passive"))
      (node (ref "C35") (pin "1") (pinfunction "C1_1") (pintype "passive"))
      (node (ref "C36") (pin "1") (pinfunction "C1_1") (pintype "passive"))
      (node (ref "C38") (pin "1") (pinfunction "C1_1") (pintype "passive"))
      (node (ref "C39") (pin "1") (pinfunction "C1_1") (pintype "passive"))
      (node (ref "C40") (pin "1") (pinfunction "C1_1") (pintype "passive"))
      (node (ref "C42") (pin "1") (pinfunction "C1_1") (pintype "passive"))
      (node (ref "C43") (pin "1") (pinfunction "C1_1") (pintype "passive"))
      (node (ref "C44") (pin "1") (pinfunction "C1_1") (pintype "passive"))
      (node (ref "C46") (pin "1") (pinfunction "C1_1") (pintype "passive"))
      (node (ref "C47") (pin "1") (pinfunction "C1_1") (pintype "passive"))
      (node (ref "C48") (pin "1") (pinfunction "C1_1") (pintype "passive"))
      (node (ref "U12") (pin "11") (pinfunction "VCC2_DRV_11") (pintype "power_in"))
      (node (ref "U12") (pin "17") (pinfunction "VCC_AMP2_17") (pintype "power_in"))
      (node (ref "U12") (pin "19") (pinfunction "VCC_ENV_19") (pintype "power_in"))
      (node (ref "U12") (pin "20") (pinfunction "VCC_AMP1_20") (pintype "power_in"))
      (node (ref "U12") (pin "23") (pinfunction "VCC_BG2_23") (pintype "power_in"))
      (node (ref "U12") (pin "32") (pinfunction "VCC_MIXER_32") (pintype "power_in"))
      (node (ref "U12") (pin "33") (pinfunction "VCC_BG_33") (pintype "power_in"))
      (node (ref "U12") (pin "35") (pinfunction "VCC_QUAD_35") (pintype "power_in"))
      (node (ref "U12") (pin "7") (pinfunction "VCC_DRV_7") (pintype "power_in"))
      (node (ref "U33") (pin "1") (pinfunction "VOUT_1") (pintype "bidirectional"))
      (node (ref "U33") (pin "2") (pinfunction "VOUT_2") (pintype "bidirectional"))
      (node (ref "U33") (pin "3") (pinfunction "SENSE_3") (pintype "bidirectional"))
    )
    (net (code "11") (name "3V3_SYNTH") (class "Default")
      (node (ref "C103") (pin "1") (pinfunction "C1_1") (pintype "passive"))
      (node (ref "C104") (pin "1") (pinfunction "C1_1") (pintype "passive"))
      (node (ref "C105") (pin "1") (pinfunction "C1_1") (pintype "passive"))
      (node (ref "C107") (pin "1") (pinfunction "C1_1") (pintype "passive"))
      (node (ref "C108") (pin "1") (pinfunction "C1_1") (pintype "passive"))
      (node (ref "C110") (pin "1") (pinfunction "C1_1") (pintype "passive"))
      (node (ref "C111") (pin "1") (pinfunction "C1_1") (pintype "passive"))
      (node (ref "C139") (pin "1") (pinfunction "C1_1") (pintype "passive"))
      (node (ref "C142") (pin "1") (pinfunction "C1_1") (pintype "passive"))
      (node (ref "FB3") (pin "1") (pinfunction "1_1") (pintype "passive"))
      (node (ref "L5") (pin "1") (pinfunction "1_1") (pintype "passive"))
      (node (ref "L6") (pin "1") (pinfunction "1_1") (pintype "passive"))
      (node (ref "R59") (pin "2") (pinfunction "2_2") (pintype "passive"))
      (node (ref "R61") (pin "2") (pinfunction "2_2") (pintype "passive"))
      (node (ref "U25") (pin "12") (pinfunction "VDDPDCP_12") (pintype "bidirectional"))
      (node (ref "U25") (pin "15") (pinfunction "VDDFB_15") (pintype "bidirectional"))
      (node (ref "U25") (pin "24") (pinfunction "VDDIN_24") (pintype "bidirectional"))
      (node (ref "U25") (pin "3") (pinfunction "VDDVCO2_3") (pintype "bidirectional"))
      (node (ref "U25") (pin "33") (pinfunction "VDDVCO1_33") (pintype "bidirectional"))
      (node (ref "U25") (pin "37") (pinfunction "VDDOUTA_37") (pintype "bidirectional"))
      (node (ref "U25") (pin "48") (pinfunction "VDDOUTB_48") (pintype "bidirectional"))
      (node (ref "U28") (pin "1") (pinfunction "VOUT_1") (pintype "bidirectional"))
      (node (ref "U28") (pin "2") (pinfunction "VOUT_2") (pintype "bidirectional"))
      (node (ref "U28") (pin "3") (pinfunction "SENSE_3") (pintype "bidirectional"))
    )
    (net (code "12") (name "5V0") (class "Default")
      (node (ref "C128") (pin "1") (pinfunction "C1_1") (pintype "passive"))
      (node (ref "C129") (pin "1") (pinfunction "C1_1") (pintype "passive"))
      (node (ref "C130") (pin "1") (pinfunction "C1_1") (pintype "passive"))
      (node (ref "C131") (pin "1") (pinfunction "C1_1") (pintype "passive"))
      (node (ref "C132") (pin "1") (pinfunction "C1_1") (pintype "passive"))
      (node (ref "C133") (pin "1") (pinfunction "C1_1") (pintype "passive"))
      (node (ref "C134") (pin "1") (pinfunction "C1_1") (pintype "passive"))
      (node (ref "C152") (pin "1") (pinfunction "C1_1") (pintype "passive"))
      (node (ref "C155") (pin "1") (pinfunction "C1_1") (pintype "passive"))
      (node (ref "C162") (pin "1") (pinfunction "C1_1") (pintype "passive"))
      (node (ref "C163") (pin "1") (pinfunction "C1_1") (pintype "passive"))
      (node (ref "C164") (pin "1") (pinfunction "C1_1") (pintype "passive"))
      (node (ref "C165") (pin "1") (pinfunction "C1_1") (pintype "passive"))
      (node (ref "C166") (pin "1") (pinfunction "C1_1") (pintype "passive"))
      (node (ref "JP3") (pin "5") (pinfunction "S_5") (pintype "passive"))
      (node (ref "JP3") (pin "6") (pinfunction "S_6") (pintype "passive"))
      (node (ref "U26") (pin "1") (pinfunction "VIN_1") (pintype "bidirectional"))
      (node (ref "U27") (pin "7") (pinfunction "VIN_7") (pintype "bidirectional"))
      (node (ref "U27") (pin "8") (pinfunction "VIN_8") (pintype "bidirectional"))
      (node (ref "U28") (pin "7") (pinfunction "VIN_7") (pintype "bidirectional"))
      (node (ref "U28") (pin "8") (pinfunction "VIN_8") (pintype "bidirectional"))
      (node (ref "U32") (pin "8") (pinfunction "VIN_8") (pintype "bidirectional"))
      (node (ref "U33") (pin "7") (pinfunction "VIN_7") (pintype "bidirectional"))
      (node (ref "U33") (pin "8") (pinfunction "VIN_8") (pintype "bidirectional"))
      (node (ref "U34") (pin "7") (pinfunction "VIN_7") (pintype "bidirectional"))
      (node (ref "U34") (pin "8") (pinfunction "VIN_8") (pintype "bidirectional"))
    )
    (net (code "13") (name "5V0_RF_LO") (class "Default")
      (node (ref "C138") (pin "1") (pinfunction "C1_1") (pintype "passive"))
      (node (ref "C141") (pin "1") (pinfunction "C1_1") (pintype "passive"))
      (node (ref "R49") (pin "2") (pinfunction "2_2") (pintype "passive"))
      (node (ref "R50") (pin "2") (pinfunction "2_2") (pintype "passive"))
      (node (ref "U27") (pin "1") (pinfunction "VOUT_1") (pintype "bidirectional"))
      (node (ref "U27") (pin "2") (pinfunction "VOUT_2") (pintype "bidirectional"))
      (node (ref "U27") (pin "3") (pinfunction "SENSE_3") (pintype "bidirectional"))
    )
    (net (code "14") (name "DAC_I2C_SCL") (class "Default")
      (node (ref "R3") (pin "1") (pinfunction "1_1") (pintype "passive"))
      (node (ref "U1") (pin "35") (pinfunction "PD7_35") (pintype "bidirectional"))
      (node (ref "U8") (pin "2") (pinfunction "SCL_2") (pintype "bidirectional"))
    )
    (net (code "15") (name "DAC_I2C_SDA") (class "Default")
      (node (ref "R4") (pin "1") (pinfunction "1_1") (pintype "passive"))
      (node (ref "U1") (pin "34") (pinfunction "PD6_34") (pintype "bidirectional"))
      (node (ref "U8") (pin "3") (pinfunction "SDA_3") (pintype "bidirectional"))
    )
    (net (code "16") (name "EXT_IO_1_3") (class "Default")
      (node (ref "JP1") (pin "4") (pinfunction "S_4") (pintype "passive"))
      (node (ref "U1") (pin "37") (pinfunction "PC6_37") (pintype "bidirectional"))
    )
    (net (code "17") (name "EXT_IO_1_4") (class "Default")
      (node (ref "JP1") (pin "3") (pinfunction "S_3") (pintype "passive"))
      (node (ref "R23") (pin "1") (pinfunction "1_1") (pintype "passive"))
      (node (ref "U1") (pin "38") (pinfunction "PC7_38") (pintype "bidirectional"))
    )
    (net (code "18") (name "EXT_IO_1_5") (class "Default")
      (node (ref "JP1") (pin "6") (pinfunction "S_6") (pintype "passive"))
      (node (ref "U1") (pin "36") (pinfunction "PD8_36") (pintype "bidirectional"))
    )
    (net (code "19") (name "EXT_IO_2_2") (class "Default")
      (node (ref "JP2") (pin "6") (pinfunction "S_6") (pintype "passive"))
    )
    (net (code "20") (name "EXT_IO_2_4") (class "Default")
      (node (ref "JP2") (pin "4") (pinfunction "S_4") (pintype "passive"))
    )
    (net (code "21") (name "EXT_IO_2_6") (class "Default")
      (node (ref "JP2") (pin "2") (pinfunction "S_2") (pintype "passive"))
    )
    (net (code "22") (name "EXT_LO_ATT_CLK") (class "Default")
      (node (ref "U1") (pin "11") (pinfunction "PB5_11") (pintype "bidirectional"))
      (node (ref "U17") (pin "24") (pinfunction "D5/CLK_24") (pintype "bidirectional"))
    )
    (net (code "23") (name "EXT_LO_ATT_LE") (class "Default")
      (node (ref "U1") (pin "10") (pinfunction "PB4_10") (pintype "bidirectional"))
      (node (ref "U17") (pin "1") (pinfunction "LE_1") (pintype "bidirectional"))
    )
    (net (code "24") (name "EXT_LO_ATT_SERIN") (class "Default")
      (node (ref "U1") (pin "9") (pinfunction "PB3_9") (pintype "bidirectional"))
      (node (ref "U17") (pin "23") (pinfunction "D4/SERIN_23") (pintype "bidirectional"))
    )
    (net (code "25") (name "EXT_RX_LO") (class "Default")
      (node (ref "R52") (pin "1") (pinfunction "1_1") (pintype "passive"))
      (node (ref "R53") (pin "2") (pinfunction "2_2") (pintype "passive"))
      (node (ref "U23") (pin "14") (pinfunction "RF1_14") (pintype "bidirectional"))
    )
    (net (code "26") (name "EXT_TX_LO") (class "Default")
      (node (ref "R51") (pin "1") (pinfunction "1_1") (pintype "passive"))
      (node (ref "R53") (pin "1") (pinfunction "1_1") (pintype "passive"))
      (node (ref "U20") (pin "7") (pinfunction "RF2_7") (pintype "bidirectional"))
    )
    (net (code "27") (name "GND") (class "Default")
      (node (ref "C1") (pin "2") (pinfunction "C2_2") (pintype "passive"))
      (node (ref "C10") (pin "2") (pinfunction "C2_2") (pintype "passive"))
      (node (ref "C100") (pin "2") (pinfunction "C2_2") (pintype "passive"))
      (node (ref "C101") (pin "2") (pinfunction "C2_2") (pintype "passive"))
      (node (ref "C103") (pin "2") (pinfunction "C2_2") (pintype "passive"))
      (node (ref "C104") (pin "2") (pinfunction "C2_2") (pintype "passive"))
      (node (ref "C105") (pin "2") (pinfunction "C2_2") (pintype "passive"))
      (node (ref "C106") (pin "2") (pinfunction "C2_2") (pintype "passive"))
      (node (ref "C107") (pin "2") (pinfunction "C2_2") (pintype "passive"))
      (node (ref "C108") (pin "2") (pinfunction "C2_2") (pintype "passive"))
      (node (ref "C109") (pin "2") (pinfunction "C2_2") (pintype "passive"))
      (node (ref "C11") (pin "2") (pinfunction "C2_2") (pintype "passive"))
      (node (ref "C110") (pin "2") (pinfunction "C2_2") (pintype "passive"))
      (node (ref "C111") (pin "2") (pinfunction "C2_2") (pintype "passive"))
      (node (ref "C112") (pin "2") (pinfunction "C2_2") (pintype "passive"))
      (node (ref "C113") (pin "2") (pinfunction "C2_2") (pintype "passive"))
      (node (ref "C114") (pin "2") (pinfunction "C2_2") (pintype "passive"))
      (node (ref "C115") (pin "2") (pinfunction "C2_2") (pintype "passive"))
      (node (ref "C116") (pin "2") (pinfunction "C2_2") (pintype "passive"))
      (node (ref "C117") (pin "2") (pinfunction "C2_2") (pintype "passive"))
      (node (ref "C118") (pin "2") (pinfunction "C2_2") (pintype "passive"))
      (node (ref "C119") (pin "2") (pinfunction "C2_2") (pintype "passive"))
      (node (ref "C12") (pin "2") (pinfunction "C2_2") (pintype "passive"))
      (node (ref "C120") (pin "2") (pinfunction "C2_2") (pintype "passive"))
      (node (ref "C121") (pin "2") (pinfunction "C2_2") (pintype "passive"))
      (node (ref "C122") (pin "2") (pinfunction "C2_2") (pintype "passive"))
      (node (ref "C123") (pin "2") (pinfunction "C2_2") (pintype "passive"))
      (node (ref "C128") (pin "2") (pinfunction "C2_2") (pintype "passive"))
      (node (ref "C129") (pin "2") (pinfunction "C2_2") (pintype "passive"))
      (node (ref "C13") (pin "2") (pinfunction "C2_2") (pintype "passive"))
      (node (ref "C130") (pin "2") (pinfunction "C2_2") (pintype "passive"))
      (node (ref "C131") (pin "2") (pinfunction "C2_2") (pintype "passive"))
      (node (ref "C132") (pin "2") (pinfunction "C2_2") (pintype "passive"))
      (node (ref "C133") (pin "2") (pinfunction "C2_2") (pintype "passive"))
      (node (ref "C134") (pin "2") (pinfunction "C2_2") (pintype "passive"))
      (node (ref "C135") (pin "2") (pinfunction "C2_2") (pintype "passive"))
      (node (ref "C136") (pin "2") (pinfunction "C2_2") (pintype "passive"))
      (node (ref "C137") (pin "2") (pinfunction "C2_2") (pintype "passive"))
      (node (ref "C138") (pin "2") (pinfunction "C2_2") (pintype "passive"))
      (node (ref "C139") (pin "2") (pinfunction "C2_2") (pintype "passive"))
      (node (ref "C14") (pin "2") (pinfunction "C2_2") (pintype "passive"))
      (node (ref "C140") (pin "2") (pinfunction "C2_2") (pintype "passive"))
      (node (ref "C141") (pin "2") (pinfunction "C2_2") (pintype "passive"))
      (node (ref "C142") (pin "2") (pinfunction "C2_2") (pintype "passive"))
      (node (ref "C143") (pin "2") (pinfunction "C2_2") (pintype "passive"))
      (node (ref "C144") (pin "2") (pinfunction "C2_2") (pintype "passive"))
      (node (ref "C146") (pin "2") (pinfunction "C2_2") (pintype "passive"))
      (node (ref "C147") (pin "2") (pinfunction "C2_2") (pintype "passive"))
      (node (ref "C148") (pin "2") (pinfunction "C2_2") (pintype "passive"))
      (node (ref "C149") (pin "2") (pinfunction "C2_2") (pintype "passive"))
      (node (ref "C15") (pin "2") (pinfunction "C2_2") (pintype "passive"))
      (node (ref "C150") (pin "2") (pinfunction "C2_2") (pintype "passive"))
      (node (ref "C151") (pin "2") (pinfunction "C2_2") (pintype "passive"))
      (node (ref "C152") (pin "2") (pinfunction "C2_2") (pintype "passive"))
      (node (ref "C153") (pin "2") (pinfunction "C2_2") (pintype "passive"))
      (node (ref "C154") (pin "2") (pinfunction "C2_2") (pintype "passive"))
      (node (ref "C155") (pin "2") (pinfunction "C2_2") (pintype "passive"))
      (node (ref "C156") (pin "2") (pinfunction "C2_2") (pintype "passive"))
      (node (ref "C157") (pin "2") (pinfunction "C2_2") (pintype "passive"))
      (node (ref "C158") (pin "2") (pinfunction "C2_2") (pintype "passive"))
      (node (ref "C159") (pin "2") (pinfunction "C2_2") (pintype "passive"))
      (node (ref "C16") (pin "2") (pinfunction "C2_2") (pintype "passive"))
      (node (ref "C160") (pin "2") (pinfunction "C2_2") (pintype "passive"))
      (node (ref "C161") (pin "2") (pinfunction "C2_2") (pintype "passive"))
      (node (ref "C162") (pin "2") (pinfunction "C2_2") (pintype "passive"))
      (node (ref "C163") (pin "2") (pinfunction "C2_2") (pintype "passive"))
      (node (ref "C164") (pin "2") (pinfunction "C2_2") (pintype "passive"))
      (node (ref "C165") (pin "2") (pinfunction "C2_2") (pintype "passive"))
      (node (ref "C166") (pin "2") (pinfunction "C2_2") (pintype "passive"))
      (node (ref "C167") (pin "2") (pinfunction "C2_2") (pintype "passive"))
      (node (ref "C168") (pin "2") (pinfunction "C2_2") (pintype "passive"))
      (node (ref "C169") (pin "2") (pinfunction "C2_2") (pintype "passive"))
      (node (ref "C17") (pin "2") (pinfunction "C2_2") (pintype "passive"))
      (node (ref "C170") (pin "2") (pinfunction "C2_2") (pintype "passive"))
      (node (ref "C171") (pin "2") (pinfunction "C2_2") (pintype "passive"))
      (node (ref "C172") (pin "2") (pinfunction "C2_2") (pintype "passive"))
      (node (ref "C18") (pin "2") (pinfunction "C2_2") (pintype "passive"))
      (node (ref "C19") (pin "2") (pinfunction "C2_2") (pintype "passive"))
      (node (ref "C2") (pin "2") (pinfunction "C2_2") (pintype "passive"))
      (node (ref "C20") (pin "2") (pinfunction "C2_2") (pintype "passive"))
      (node (ref "C21") (pin "2") (pinfunction "C2_2") (pintype "passive"))
      (node (ref "C22") (pin "2") (pinfunction "C2_2") (pintype "passive"))
      (node (ref "C23") (pin "2") (pinfunction "C2_2") (pintype "passive"))
      (node (ref "C24") (pin "2") (pinfunction "C2_2") (pintype "passive"))
      (node (ref "C25") (pin "2") (pinfunction "C2_2") (pintype "passive"))
      (node (ref "C26") (pin "2") (pinfunction "C2_2") (pintype "passive"))
      (node (ref "C27") (pin "2") (pinfunction "C2_2") (pintype "passive"))
      (node (ref "C28") (pin "2") (pinfunction "C2_2") (pintype "passive"))
      (node (ref "C29") (pin "2") (pinfunction "C2_2") (pintype "passive"))
      (node (ref "C3") (pin "2") (pinfunction "C2_2") (pintype "passive"))
      (node (ref "C30") (pin "2") (pinfunction "C2_2") (pintype "passive"))
      (node (ref "C31") (pin "2") (pinfunction "C2_2") (pintype "passive"))
      (node (ref "C32") (pin "2") (pinfunction "C2_2") (pintype "passive"))
      (node (ref "C33") (pin "2") (pinfunction "C2_2") (pintype "passive"))
      (node (ref "C34") (pin "2") (pinfunction "C2_2") (pintype "passive"))
      (node (ref "C35") (pin "2") (pinfunction "C2_2") (pintype "passive"))
      (node (ref "C36") (pin "2") (pinfunction "C2_2") (pintype "passive"))
      (node (ref "C37") (pin "2") (pinfunction "C2_2") (pintype "passive"))
      (node (ref "C38") (pin "2") (pinfunction "C2_2") (pintype "passive"))
      (node (ref "C39") (pin "2") (pinfunction "C2_2") (pintype "passive"))
      (node (ref "C4") (pin "2") (pinfunction "C2_2") (pintype "passive"))
      (node (ref "C40") (pin "2") (pinfunction "C2_2") (pintype "passive"))
      (node (ref "C41") (pin "2") (pinfunction "C2_2") (pintype "passive"))
      (node (ref "C42") (pin "2") (pinfunction "C2_2") (pintype "passive"))
      (node (ref "C43") (pin "2") (pinfunction "C2_2") (pintype "passive"))
      (node (ref "C44") (pin "2") (pinfunction "C2_2") (pintype "passive"))
      (node (ref "C45") (pin "2") (pinfunction "C2_2") (pintype "passive"))
      (node (ref "C46") (pin "2") (pinfunction "C2_2") (pintype "passive"))
      (node (ref "C47") (pin "2") (pinfunction "C2_2") (pintype "passive"))
      (node (ref "C48") (pin "2") (pinfunction "C2_2") (pintype "passive"))
      (node (ref "C49") (pin "2") (pinfunction "C2_2") (pintype "passive"))
      (node (ref "C5") (pin "2") (pinfunction "C2_2") (pintype "passive"))
      (node (ref "C50") (pin "2") (pinfunction "C2_2") (pintype "passive"))
      (node (ref "C51") (pin "2") (pinfunction "C2_2") (pintype "passive"))
      (node (ref "C52") (pin "2") (pinfunction "C2_2") (pintype "passive"))
      (node (ref "C53") (pin "2") (pinfunction "C2_2") (pintype "passive"))
      (node (ref "C54") (pin "2") (pinfunction "C2_2") (pintype "passive"))
      (node (ref "C55") (pin "2") (pinfunction "C2_2") (pintype "passive"))
      (node (ref "C56") (pin "2") (pinfunction "C2_2") (pintype "passive"))
      (node (ref "C57") (pin "2") (pinfunction "C2_2") (pintype "passive"))
      (node (ref "C58") (pin "2") (pinfunction "C2_2") (pintype "passive"))
      (node (ref "C59") (pin "2") (pinfunction "C2_2") (pintype "passive"))
      (node (ref "C6") (pin "2") (pinfunction "C2_2") (pintype "passive"))
      (node (ref "C60") (pin "2") (pinfunction "C2_2") (pintype "passive"))
      (node (ref "C61") (pin "2") (pinfunction "C2_2") (pintype "passive"))
      (node (ref "C62") (pin "2") (pinfunction "C2_2") (pintype "passive"))
      (node (ref "C63") (pin "2") (pinfunction "C2_2") (pintype "passive"))
      (node (ref "C64") (pin "2") (pinfunction "C2_2") (pintype "passive"))
      (node (ref "C65") (pin "2") (pinfunction "C2_2") (pintype "passive"))
      (node (ref "C66") (pin "2") (pinfunction "C2_2") (pintype "passive"))
      (node (ref "C67") (pin "2") (pinfunction "C2_2") (pintype "passive"))
      (node (ref "C68") (pin "2") (pinfunction "C2_2") (pintype "passive"))
      (node (ref "C69") (pin "2") (pinfunction "C2_2") (pintype "passive"))
      (node (ref "C7") (pin "2") (pinfunction "C2_2") (pintype "passive"))
      (node (ref "C71") (pin "2") (pinfunction "C2_2") (pintype "passive"))
      (node (ref "C72") (pin "2") (pinfunction "C2_2") (pintype "passive"))
      (node (ref "C74") (pin "2") (pinfunction "C2_2") (pintype "passive"))
      (node (ref "C75") (pin "2") (pinfunction "C2_2") (pintype "passive"))
      (node (ref "C76") (pin "2") (pinfunction "C2_2") (pintype "passive"))
      (node (ref "C77") (pin "2") (pinfunction "C2_2") (pintype "passive"))
      (node (ref "C79") (pin "2") (pinfunction "C2_2") (pintype "passive"))
      (node (ref "C8") (pin "2") (pinfunction "C2_2") (pintype "passive"))
      (node (ref "C80") (pin "2") (pinfunction "C2_2") (pintype "passive"))
      (node (ref "C82") (pin "2") (pinfunction "C2_2") (pintype "passive"))
      (node (ref "C84") (pin "2") (pinfunction "C2_2") (pintype "passive"))
      (node (ref "C85") (pin "2") (pinfunction "C2_2") (pintype "passive"))
      (node (ref "C86") (pin "2") (pinfunction "C2_2") (pintype "passive"))
      (node (ref "C87") (pin "2") (pinfunction "C2_2") (pintype "passive"))
      (node (ref "C88") (pin "2") (pinfunction "C2_2") (pintype "passive"))
      (node (ref "C89") (pin "2") (pinfunction "C2_2") (pintype "passive"))
      (node (ref "C9") (pin "2") (pinfunction "C2_2") (pintype "passive"))
      (node (ref "C90") (pin "2") (pinfunction "C2_2") (pintype "passive"))
      (node (ref "C91") (pin "2") (pinfunction "C2_2") (pintype "passive"))
      (node (ref "C92") (pin "2") (pinfunction "C2_2") (pintype "passive"))
      (node (ref "C94") (pin "2") (pinfunction "C2_2") (pintype "passive"))
      (node (ref "C95") (pin "2") (pinfunction "C2_2") (pintype "passive"))
      (node (ref "C96") (pin "2") (pinfunction "C2_2") (pintype "passive"))
      (node (ref "C97") (pin "2") (pinfunction "C2_2") (pintype "passive"))
      (node (ref "C98") (pin "2") (pinfunction "C2_2") (pintype "passive"))
      (node (ref "C99") (pin "2") (pinfunction "C2_2") (pintype "passive"))
      (node (ref "JP1") (pin "5") (pinfunction "S_5") (pintype "passive"))
      (node (ref "JP2") (pin "1") (pinfunction "S_1") (pintype "passive"))
      (node (ref "JP2") (pin "5") (pinfunction "S_5") (pintype "passive"))
      (node (ref "JP3") (pin "3") (pinfunction "S_3") (pintype "passive"))
      (node (ref "JP3") (pin "4") (pinfunction "S_4") (pintype "passive"))
      (node (ref "L1") (pin "2") (pinfunction "2_2") (pintype "passive"))
      (node (ref "L3") (pin "2") (pinfunction "2_2") (pintype "passive"))
      (node (ref "Q1") (pin "2") (pinfunction "S_2") (pintype "passive"))
      (node (ref "Q2") (pin "2") (pinfunction "S_2") (pintype "passive"))
      (node (ref "R12") (pin "2") (pinfunction "2_2") (pintype "passive"))
      (node (ref "R15") (pin "1") (pinfunction "1_1") (pintype "passive"))
      (node (ref "R19") (pin "1") (pinfunction "1_1") (pintype "passive"))
      (node (ref "R21") (pin "2") (pinfunction "2_2") (pintype "passive"))
      (node (ref "R26") (pin "1") (pinfunction "1_1") (pintype "passive"))
      (node (ref "R27") (pin "1") (pinfunction "1_1") (pintype "passive"))
      (node (ref "R34") (pin "1") (pinfunction "1_1") (pintype "passive"))
      (node (ref "R38") (pin "1") (pinfunction "1_1") (pintype "passive"))
      (node (ref "R39") (pin "1") (pinfunction "1_1") (pintype "passive"))
      (node (ref "R40") (pin "1") (pinfunction "1_1") (pintype "passive"))
      (node (ref "R42") (pin "1") (pinfunction "1_1") (pintype "passive"))
      (node (ref "R44") (pin "1") (pinfunction "1_1") (pintype "passive"))
      (node (ref "R45") (pin "1") (pinfunction "1_1") (pintype "passive"))
      (node (ref "R46") (pin "1") (pinfunction "1_1") (pintype "passive"))
      (node (ref "R47") (pin "1") (pinfunction "1_1") (pintype "passive"))
      (node (ref "R48") (pin "1") (pinfunction "1_1") (pintype "passive"))
      (node (ref "R55") (pin "1") (pinfunction "1_1") (pintype "passive"))
      (node (ref "R57") (pin "1") (pinfunction "1_1") (pintype "passive"))
      (node (ref "R58") (pin "1") (pinfunction "1_1") (pintype "passive"))
      (node (ref "R6") (pin "1") (pinfunction "1_1") (pintype "passive"))
      (node (ref "R60") (pin "1") (pinfunction "1_1") (pintype "passive"))
      (node (ref "R62") (pin "1") (pinfunction "1_1") (pintype "passive"))
      (node (ref "R69") (pin "1") (pinfunction "1_1") (pintype "passive"))
      (node (ref "R70") (pin "1") (pinfunction "1_1") (pintype "passive"))
      (node (ref "R71") (pin "1") (pinfunction "1_1") (pintype "passive"))
      (node (ref "R72") (pin "1") (pinfunction "1_1") (pintype "passive"))
      (node (ref "R73") (pin "1") (pinfunction "1_1") (pintype "passive"))
      (node (ref "R75") (pin "1") (pinfunction "1_1") (pintype "passive"))
      (node (ref "R76") (pin "1") (pinfunction "1_1") (pintype "passive"))
      (node (ref "R77") (pin "1") (pinfunction "1_1") (pintype "passive"))
      (node (ref "R78") (pin "1") (pinfunction "1_1") (pintype "passive"))
      (node (ref "R8") (pin "1") (pinfunction "1_1") (pintype "passive"))
      (node (ref "RFCON1") (pin "P$1") (pinfunction "GND_P$1") (pintype "bidirectional"))
      (node (ref "RFCON1") (pin "P$2") (pinfunction "GND_P$2") (pintype "bidirectional"))
      (node (ref "RFCON2") (pin "GND@1") (pinfunction "GND_GND@1") (pintype "bidirectional"))
      (node (ref "RFCON2") (pin "GND@2") (pinfunction "GND_GND@2") (pintype "bidirectional"))
      (node (ref "RFCON3") (pin "P$1") (pinfunction "GND_P$1") (pintype "bidirectional"))
      (node (ref "RFCON3") (pin "P$2") (pinfunction "GND_P$2") (pintype "bidirectional"))
      (node (ref "RFCON4") (pin "GND@1") (pinfunction "GND_GND@1") (pintype "bidirectional"))
      (node (ref "RFCON4") (pin "GND@2") (pinfunction "GND_GND@2") (pintype "bidirectional"))
      (node (ref "RFCON5") (pin "P$1") (pinfunction "GND_P$1") (pintype "bidirectional"))
      (node (ref "RFCON5") (pin "P$2") (pinfunction "GND_P$2") (pintype "bidirectional"))
      (node (ref "RFCON6") (pin "P$1") (pinfunction "GND_P$1") (pintype "bidirectional"))
      (node (ref "RFCON6") (pin "P$2") (pinfunction "GND_P$2") (pintype "bidirectional"))
      (node (ref "RFCON7") (pin "P$1") (pinfunction "GND_P$1") (pintype "bidirectional"))
      (node (ref "RFCON7") (pin "P$2") (pinfunction "GND_P$2") (pintype "bidirectional"))
      (node (ref "TC1") (pin "3") (pinfunction "S_3") (pintype "passive"))
      (node (ref "U1") (pin "22") (pinfunction "VSS_22") (pintype "bidirectional"))
      (node (ref "U1") (pin "56") (pinfunction "VSS_56") (pintype "bidirectional"))
      (node (ref "U1") (pin "8") (pinfunction "VSS_8") (pintype "bidirectional"))
      (node (ref "U10") (pin "2") (pinfunction "GND_2") (pintype "bidirectional"))
      (node (ref "U10") (pin "4") (pinfunction "GND_4") (pintype "bidirectional"))
      (node (ref "U11") (pin "2") (pinfunction "GND_2") (pintype "bidirectional"))
      (node (ref "U11") (pin "5") (pinfunction "GND_5") (pintype "bidirectional"))
      (node (ref "U12") (pin "10") (pinfunction "GND_10") (pintype "bidirectional"))
      (node (ref "U12") (pin "27") (pinfunction "GND_27") (pintype "bidirectional"))
      (node (ref "U12") (pin "36") (pinfunction "GND_36") (pintype "bidirectional"))
      (node (ref "U12") (pin "39") (pinfunction "GND_39") (pintype "bidirectional"))
      (node (ref "U12") (pin "41") (pinfunction "GND_41") (pintype "bidirectional"))
      (node (ref "U12") (pin "8") (pinfunction "GND_8") (pintype "bidirectional"))
      (node (ref "U13") (pin "2") (pinfunction "GND_2") (pintype "bidirectional"))
      (node (ref "U13") (pin "4") (pinfunction "GND_4") (pintype "bidirectional"))
      (node (ref "U14") (pin "2") (pinfunction "GND_2") (pintype "bidirectional"))
      (node (ref "U14") (pin "5") (pinfunction "GND_5") (pintype "bidirectional"))
      (node (ref "U15") (pin "13") (pinfunction "GND_13") (pintype "bidirectional"))
      (node (ref "U15") (pin "17") (pinfunction "GND_17") (pintype "bidirectional"))
      (node (ref "U15") (pin "19") (pinfunction "GND_19") (pintype "bidirectional"))
      (node (ref "U15") (pin "25") (pinfunction "GND_25") (pintype "bidirectional"))
      (node (ref "U15") (pin "28") (pinfunction "GND_28") (pintype "bidirectional"))
      (node (ref "U15") (pin "33") (pinfunction "GND_33") (pintype "bidirectional"))
      (node (ref "U15") (pin "5") (pinfunction "GND_5") (pintype "bidirectional"))
      (node (ref "U16") (pin "1") (pinfunction "GND_1") (pintype "bidirectional"))
      (node (ref "U16") (pin "2") (pinfunction "GND_2") (pintype "bidirectional"))
      (node (ref "U16") (pin "4") (pinfunction "GND_4") (pintype "bidirectional"))
      (node (ref "U16") (pin "5") (pinfunction "GND_5") (pintype "bidirectional"))
      (node (ref "U16") (pin "7") (pinfunction "GND_7") (pintype "bidirectional"))
      (node (ref "U16") (pin "8") (pinfunction "GND_8") (pintype "bidirectional"))
      (node (ref "U16") (pin "9") (pinfunction "GND_9") (pintype "bidirectional"))
      (node (ref "U17") (pin "10") (pinfunction "GND_10") (pintype "bidirectional"))
      (node (ref "U17") (pin "11") (pinfunction "GND_11") (pintype "bidirectional"))
      (node (ref "U17") (pin "12") (pinfunction "GND_12") (pintype "bidirectional"))
      (node (ref "U17") (pin "13") (pinfunction "GND_13") (pintype "bidirectional"))
      (node (ref "U17") (pin "15") (pinfunction "GND_15") (pintype "bidirectional"))
      (node (ref "U17") (pin "16") (pinfunction "GND_16") (pintype "bidirectional"))
      (node (ref "U17") (pin "25") (pinfunction "GND_25") (pintype "bidirectional"))
      (node (ref "U17") (pin "3") (pinfunction "GND_3") (pintype "bidirectional"))
      (node (ref "U17") (pin "4") (pinfunction "GND_4") (pintype "bidirectional"))
      (node (ref "U17") (pin "6") (pinfunction "GND_6") (pintype "bidirectional"))
      (node (ref "U17") (pin "7") (pinfunction "GND_7") (pintype "bidirectional"))
      (node (ref "U17") (pin "8") (pinfunction "GND_8") (pintype "bidirectional"))
      (node (ref "U17") (pin "9") (pinfunction "GND_9") (pintype "bidirectional"))
      (node (ref "U18") (pin "1") (pinfunction "GND_1") (pintype "bidirectional"))
      (node (ref "U18") (pin "2") (pinfunction "GND_2") (pintype "bidirectional"))
      (node (ref "U18") (pin "4") (pinfunction "GND_4") (pintype "bidirectional"))
      (node (ref "U18") (pin "5") (pinfunction "GND_5") (pintype "bidirectional"))
      (node (ref "U18") (pin "7") (pinfunction "GND_7") (pintype "bidirectional"))
      (node (ref "U18") (pin "8") (pinfunction "GND_8") (pintype "bidirectional"))
      (node (ref "U18") (pin "9") (pinfunction "GND_9") (pintype "bidirectional"))
      (node (ref "U19") (pin "4") (pinfunction "GND_4") (pintype "bidirectional"))
      (node (ref "U19") (pin "5") (pinfunction "GND_5") (pintype "bidirectional"))
      (node (ref "U19") (pin "7") (pinfunction "GND_7") (pintype "bidirectional"))
      (node (ref "U19") (pin "9") (pinfunction "GND_9") (pintype "bidirectional"))
      (node (ref "U2") (pin "2") (pinfunction "GND_2") (pintype "bidirectional"))
      (node (ref "U20") (pin "1") (pinfunction "GND_1") (pintype "bidirectional"))
      (node (ref "U20") (pin "11") (pinfunction "LS_11") (pintype "bidirectional"))
      (node (ref "U20") (pin "13") (pinfunction "GND_13") (pintype "bidirectional"))
      (node (ref "U20") (pin "15") (pinfunction "GND_15") (pintype "bidirectional"))
      (node (ref "U20") (pin "16") (pinfunction "GND_16") (pintype "bidirectional"))
      (node (ref "U20") (pin "17") (pinfunction "GND_17") (pintype "bidirectional"))
      (node (ref "U20") (pin "2") (pinfunction "GND_2") (pintype "bidirectional"))
      (node (ref "U20") (pin "4") (pinfunction "GND_4") (pintype "bidirectional"))
      (node (ref "U20") (pin "5") (pinfunction "GND_5") (pintype "bidirectional"))
      (node (ref "U20") (pin "6") (pinfunction "GND_6") (pintype "bidirectional"))
      (node (ref "U20") (pin "8") (pinfunction "GND_8") (pintype "bidirectional"))
      (node (ref "U21") (pin "1") (pinfunction "GND_1") (pintype "bidirectional"))
      (node (ref "U21") (pin "11") (pinfunction "LS_11") (pintype "bidirectional"))
      (node (ref "U21") (pin "13") (pinfunction "GND_13") (pintype "bidirectional"))
      (node (ref "U21") (pin "15") (pinfunction "GND_15") (pintype "bidirectional"))
      (node (ref "U21") (pin "16") (pinfunction "GND_16") (pintype "bidirectional"))
      (node (ref "U21") (pin "17") (pinfunction "GND_17") (pintype "bidirectional"))
      (node (ref "U21") (pin "2") (pinfunction "GND_2") (pintype "bidirectional"))
      (node (ref "U21") (pin "4") (pinfunction "GND_4") (pintype "bidirectional"))
      (node (ref "U21") (pin "5") (pinfunction "GND_5") (pintype "bidirectional"))
      (node (ref "U21") (pin "6") (pinfunction "GND_6") (pintype "bidirectional"))
      (node (ref "U21") (pin "8") (pinfunction "GND_8") (pintype "bidirectional"))
      (node (ref "U22") (pin "4") (pinfunction "GND_4") (pintype "bidirectional"))
      (node (ref "U22") (pin "5") (pinfunction "GND_5") (pintype "bidirectional"))
      (node (ref "U22") (pin "7") (pinfunction "GND_7") (pintype "bidirectional"))
      (node (ref "U22") (pin "9") (pinfunction "GND_9") (pintype "bidirectional"))
      (node (ref "U23") (pin "1") (pinfunction "GND_1") (pintype "bidirectional"))
      (node (ref "U23") (pin "11") (pinfunction "LS_11") (pintype "bidirectional"))
      (node (ref "U23") (pin "13") (pinfunction "GND_13") (pintype "bidirectional"))
      (node (ref "U23") (pin "15") (pinfunction "GND_15") (pintype "bidirectional"))
      (node (ref "U23") (pin "16") (pinfunction "GND_16") (pintype "bidirectional"))
      (node (ref "U23") (pin "17") (pinfunction "GND_17") (pintype "bidirectional"))
      (node (ref "U23") (pin "2") (pinfunction "GND_2") (pintype "bidirectional"))
      (node (ref "U23") (pin "4") (pinfunction "GND_4") (pintype "bidirectional"))
      (node (ref "U23") (pin "5") (pinfunction "GND_5") (pintype "bidirectional"))
      (node (ref "U23") (pin "6") (pinfunction "GND_6") (pintype "bidirectional"))
      (node (ref "U23") (pin "8") (pinfunction "GND_8") (pintype "bidirectional"))
      (node (ref "U24") (pin "1") (pinfunction "GND_1") (pintype "bidirectional"))
      (node (ref "U24") (pin "11") (pinfunction "LS_11") (pintype "bidirectional"))
      (node (ref "U24") (pin "13") (pinfunction "GND_13") (pintype "bidirectional"))
      (node (ref "U24") (pin "15") (pinfunction "GND_15") (pintype "bidirectional"))
      (node (ref "U24") (pin "16") (pinfunction "GND_16") (pintype "bidirectional"))
      (node (ref "U24") (pin "17") (pinfunction "GND_17") (pintype "bidirectional"))
      (node (ref "U24") (pin "2") (pinfunction "GND_2") (pintype "bidirectional"))
      (node (ref "U24") (pin "4") (pinfunction "GND_4") (pintype "bidirectional"))
      (node (ref "U24") (pin "5") (pinfunction "GND_5") (pintype "bidirectional"))
      (node (ref "U24") (pin "6") (pinfunction "GND_6") (pintype "bidirectional"))
      (node (ref "U24") (pin "8") (pinfunction "GND_8") (pintype "bidirectional"))
      (node (ref "U25") (pin "14") (pinfunction "VSSPDCP_14") (pintype "bidirectional"))
      (node (ref "U25") (pin "17") (pinfunction "VSSFB_17") (pintype "bidirectional"))
      (node (ref "U25") (pin "19") (pinfunction "VSSDIG_19") (pintype "bidirectional"))
      (node (ref "U25") (pin "20") (pinfunction "VSSIN_20") (pintype "bidirectional"))
      (node (ref "U25") (pin "38") (pinfunction "VSSOUTA_38") (pintype "bidirectional"))
      (node (ref "U25") (pin "41") (pinfunction "VSSOUTA_41") (pintype "bidirectional"))
      (node (ref "U25") (pin "44") (pinfunction "VSSOUTB_44") (pintype "bidirectional"))
      (node (ref "U25") (pin "47") (pinfunction "VSSOUTB_47") (pintype "bidirectional"))
      (node (ref "U25") (pin "49") (pinfunction "VSS_49") (pintype "bidirectional"))
      (node (ref "U26") (pin "2") (pinfunction "GND_2") (pintype "bidirectional"))
      (node (ref "U27") (pin "6") (pinfunction "GND_6") (pintype "bidirectional"))
      (node (ref "U27") (pin "9") (pinfunction "GND_9") (pintype "bidirectional"))
      (node (ref "U28") (pin "6") (pinfunction "GND_6") (pintype "bidirectional"))
      (node (ref "U28") (pin "9") (pinfunction "GND_9") (pintype "bidirectional"))
      (node (ref "U29") (pin "4") (pinfunction "GND_4") (pintype "bidirectional"))
      (node (ref "U29") (pin "5") (pinfunction "SHDN_5") (pintype "bidirectional"))
      (node (ref "U3") (pin "2") (pinfunction "GND_2") (pintype "bidirectional"))
      (node (ref "U30") (pin "2") (pinfunction "GND_2") (pintype "bidirectional"))
      (node (ref "U31") (pin "2") (pinfunction "GND_2") (pintype "bidirectional"))
      (node (ref "U32") (pin "3") (pinfunction "GND_3") (pintype "bidirectional"))
      (node (ref "U32") (pin "6") (pinfunction "GND_6") (pintype "bidirectional"))
      (node (ref "U32") (pin "9") (pinfunction "GND_9") (pintype "bidirectional"))
      (node (ref "U33") (pin "6") (pinfunction "GND_6") (pintype "bidirectional"))
      (node (ref "U33") (pin "9") (pinfunction "GND_9") (pintype "bidirectional"))
      (node (ref "U34") (pin "6") (pinfunction "GND_6") (pintype "bidirectional"))
      (node (ref "U34") (pin "9") (pinfunction "GND_9") (pintype "bidirectional"))
      (node (ref "U4") (pin "2") (pinfunction "GND_2") (pintype "bidirectional"))
      (node (ref "U5") (pin "17") (pinfunction "GND_17") (pintype "bidirectional"))
      (node (ref "U5") (pin "7") (pinfunction "T/~{R}3_7") (pintype "bidirectional"))
      (node (ref "U5") (pin "8") (pinfunction "GND_8") (pintype "bidirectional"))
      (node (ref "U6") (pin "17") (pinfunction "GND_17") (pintype "bidirectional"))
      (node (ref "U6") (pin "7") (pinfunction "T/~{R}3_7") (pintype "bidirectional"))
      (node (ref "U6") (pin "8") (pinfunction "GND_8") (pintype "bidirectional"))
      (node (ref "U7") (pin "4") (pinfunction "V-_4") (pintype "power_in"))
      (node (ref "U7") (pin "9") (pinfunction "V-_9") (pintype "power_in"))
      (node (ref "U8") (pin "10") (pinfunction "VSS_10") (pintype "bidirectional"))
      (node (ref "U8") (pin "4") (pinfunction "~{LDAC}_4") (pintype "bidirectional"))
      (node (ref "U9") (pin "4") (pinfunction "V-_4") (pintype "power_in"))
      (node (ref "U9") (pin "9") (pinfunction "V-_9") (pintype "power_in"))
    )
    (net (code "28") (name "INT_RX_LO") (class "Default")
      (node (ref "C127") (pin "2") (pinfunction "C2_2") (pintype "passive"))
      (node (ref "U23") (pin "7") (pinfunction "RF2_7") (pintype "bidirectional"))
    )
    (net (code "29") (name "INT_TX_LO") (class "Default")
      (node (ref "C126") (pin "2") (pinfunction "C2_2") (pintype "passive"))
      (node (ref "U20") (pin "14") (pinfunction "RF1_14") (pintype "bidirectional"))
    )
    (net (code "30") (name "LED1") (class "Default")
      (node (ref "D1") (pin "A") (pinfunction "A_A") (pintype "passive"))
      (node (ref "U1") (pin "17") (pinfunction "PA12_17") (pintype "bidirectional"))
    )
    (net (code "31") (name "LED2") (class "Default")
      (node (ref "D2") (pin "A") (pinfunction "A_A") (pintype "passive"))
      (node (ref "U1") (pin "18") (pinfunction "PA13_18") (pintype "bidirectional"))
    )
    (net (code "32") (name "LO_ANA_PWR_EN") (class "Default")
      (node (ref "R71") (pin "2") (pinfunction "2_2") (pintype "passive"))
      (node (ref "U1") (pin "13") (pinfunction "PC4_13") (pintype "bidirectional"))
      (node (ref "U27") (pin "5") (pinfunction "EN_5") (pintype "bidirectional"))
    )
    (net (code "33") (name "MCU_I2C_SCL") (class "Default")
      (node (ref "JP1") (pin "2") (pinfunction "S_2") (pintype "passive"))
      (node (ref "R5") (pin "1") (pinfunction "1_1") (pintype "passive"))
      (node (ref "U1") (pin "33") (pinfunction "PD5_33") (pintype "bidirectional"))
    )
    (net (code "34") (name "MCU_I2C_SDA") (class "Default")
      (node (ref "JP1") (pin "1") (pinfunction "S_1") (pintype "passive"))
      (node (ref "R7") (pin "1") (pinfunction "1_1") (pintype "passive"))
      (node (ref "U1") (pin "32") (pinfunction "PD4_32") (pintype "bidirectional"))
    )
    (net (code "35") (name "Net-(C7-C1)") (class "Default")
      (node (ref "C7") (pin "1") (pinfunction "C1_1") (pintype "passive"))
      (node (ref "C8") (pin "1") (pinfunction "C1_1") (pintype "passive"))
      (node (ref "FB1") (pin "2") (pinfunction "2_2") (pintype "passive"))
      (node (ref "U1") (pin "23") (pinfunction "AVDD_23") (pintype "bidirectional"))
      (node (ref "U1") (pin "27") (pinfunction "AVDD_27") (pintype "bidirectional"))
    )
    (net (code "36") (name "Net-(C9-C1)") (class "Default")
      (node (ref "C9") (pin "1") (pinfunction "C1_1") (pintype "passive"))
      (node (ref "U1") (pin "40") (pinfunction "DECOUPLE_40") (pintype "bidirectional"))
    )
    (net (code "37") (name "Net-(C19-C1)") (class "Default")
      (node (ref "C19") (pin "1") (pinfunction "C1_1") (pintype "passive"))
      (node (ref "R24") (pin "1") (pinfunction "1_1") (pintype "passive"))
      (node (ref "U7") (pin "5") (pinfunction "+IN_5") (pintype "input"))
    )
    (net (code "38") (name "Net-(C20-C1)") (class "Default")
      (node (ref "C20") (pin "1") (pinfunction "C1_1") (pintype "passive"))
      (node (ref "R25") (pin "1") (pinfunction "1_1") (pintype "passive"))
      (node (ref "U7") (pin "3") (pinfunction "+IN_3") (pintype "input"))
    )
    (net (code "39") (name "Net-(C70-C1)") (class "Default")
      (node (ref "C70") (pin "1") (pinfunction "C1_1") (pintype "passive"))
      (node (ref "RFCON5") (pin "P$3") (pinfunction "SIGNAL_P$3") (pintype "bidirectional"))
    )
    (net (code "40") (name "Net-(C70-C2)") (class "Default")
      (node (ref "C70") (pin "2") (pinfunction "C2_2") (pintype "passive"))
      (node (ref "L1") (pin "1") (pinfunction "1_1") (pintype "passive"))
      (node (ref "U16") (pin "3") (pinfunction "RFIN_3") (pintype "bidirectional"))
    )
    (net (code "41") (name "Net-(C71-C1)") (class "Default")
      (node (ref "C71") (pin "1") (pinfunction "C1_1") (pintype "passive"))
      (node (ref "C72") (pin "1") (pinfunction "C1_1") (pintype "passive"))
      (node (ref "L2") (pin "1") (pinfunction "1_1") (pintype "passive"))
      (node (ref "R49") (pin "1") (pinfunction "1_1") (pintype "passive"))
    )
    (net (code "42") (name "Net-(C73-C1)") (class "Default")
      (node (ref "C73") (pin "1") (pinfunction "C1_1") (pintype "passive"))
      (node (ref "L2") (pin "2") (pinfunction "2_2") (pintype "passive"))
      (node (ref "U16") (pin "6") (pinfunction "RFOUT_6") (pintype "bidirectional"))
    )
    (net (code "43") (name "Net-(C73-C2)") (class "Default")
      (node (ref "C73") (pin "2") (pinfunction "C2_2") (pintype "passive"))
      (node (ref "U17") (pin "5") (pinfunction "ATTIN_5") (pintype "bidirectional"))
    )
    (net (code "44") (name "Net-(C78-C1)") (class "Default")
      (node (ref "C78") (pin "1") (pinfunction "C1_1") (pintype "passive"))
      (node (ref "U17") (pin "14") (pinfunction "ATTOUT_14") (pintype "bidirectional"))
    )
    (net (code "45") (name "Net-(C78-C2)") (class "Default")
      (node (ref "C78") (pin "2") (pinfunction "C2_2") (pintype "passive"))
      (node (ref "L3") (pin "1") (pinfunction "1_1") (pintype "passive"))
      (node (ref "U18") (pin "3") (pinfunction "RFIN_3") (pintype "bidirectional"))
    )
    (net (code "46") (name "Net-(C79-C1)") (class "Default")
      (node (ref "C79") (pin "1") (pinfunction "C1_1") (pintype "passive"))
      (node (ref "C80") (pin "1") (pinfunction "C1_1") (pintype "passive"))
      (node (ref "L4") (pin "1") (pinfunction "1_1") (pintype "passive"))
      (node (ref "R50") (pin "1") (pinfunction "1_1") (pintype "passive"))
    )
    (net (code "47") (name "Net-(C81-C1)") (class "Default")
      (node (ref "C81") (pin "1") (pinfunction "C1_1") (pintype "passive"))
      (node (ref "L4") (pin "2") (pinfunction "2_2") (pintype "passive"))
      (node (ref "U18") (pin "6") (pinfunction "RFOUT_6") (pintype "bidirectional"))
    )
    (net (code "48") (name "Net-(C81-C2)") (class "Default")
      (node (ref "C81") (pin "2") (pinfunction "C2_2") (pintype "passive"))
      (node (ref "R51") (pin "2") (pinfunction "2_2") (pintype "passive"))
      (node (ref "R52") (pin "2") (pinfunction "2_2") (pintype "passive"))
    )
    (net (code "49") (name "Net-(C82-C1)") (class "Default")
      (node (ref "C82") (pin "1") (pinfunction "C1_1") (pintype "passive"))
      (node (ref "R54") (pin "1") (pinfunction "1_1") (pintype "passive"))
      (node (ref "U19") (pin "1") (pinfunction "VCC_1") (pintype "bidirectional"))
    )
    (net (code "50") (name "Net-(C83-C2)") (class "Default")
      (node (ref "C83") (pin "2") (pinfunction "C2_2") (pintype "passive"))
      (node (ref "U19") (pin "3") (pinfunction "FLTR_3") (pintype "bidirectional"))
    )
    (net (code "51") (name "Net-(C92-C1)") (class "Default")
      (node (ref "C92") (pin "1") (pinfunction "C1_1") (pintype "passive"))
      (node (ref "R56") (pin "1") (pinfunction "1_1") (pintype "passive"))
      (node (ref "U22") (pin "1") (pinfunction "VCC_1") (pintype "bidirectional"))
    )
    (net (code "52") (name "Net-(C93-C2)") (class "Default")
      (node (ref "C93") (pin "2") (pinfunction "C2_2") (pintype "passive"))
      (node (ref "U22") (pin "3") (pinfunction "FLTR_3") (pintype "bidirectional"))
    )
    (net (code "53") (name "Net-(C102-C2)") (class "Default")
      (node (ref "C102") (pin "2") (pinfunction "C2_2") (pintype "passive"))
      (node (ref "R59") (pin "1") (pinfunction "1_1") (pintype "passive"))
      (node (ref "R60") (pin "2") (pinfunction "2_2") (pintype "passive"))
      (node (ref "U25") (pin "22") (pinfunction "REF_IN_22") (pintype "bidirectional"))
    )
    (net (code "54") (name "Net-(C106-C1)") (class "Default")
      (node (ref "C106") (pin "1") (pinfunction "C1_1") (pintype "passive"))
      (node (ref "R61") (pin "1") (pinfunction "1_1") (pintype "passive"))
      (node (ref "R62") (pin "2") (pinfunction "2_2") (pintype "passive"))
      (node (ref "U25") (pin "23") (pinfunction "~{REF_IN}_23") (pintype "bidirectional"))
    )
    (net (code "55") (name "Net-(C109-C1)") (class "Default")
      (node (ref "C109") (pin "1") (pinfunction "C1_1") (pintype "passive"))
      (node (ref "U25") (pin "32") (pinfunction "VREGVCO1_32") (pintype "bidirectional"))
    )
    (net (code "56") (name "Net-(C112-C1)") (class "Default")
      (node (ref "C112") (pin "1") (pinfunction "C1_1") (pintype "passive"))
      (node (ref "U25") (pin "4") (pinfunction "VREGVCO2_4") (pintype "bidirectional"))
    )
    (net (code "57") (name "Net-(C113-C1)") (class "Default")
      (node (ref "C113") (pin "1") (pinfunction "C1_1") (pintype "passive"))
      (node (ref "U25") (pin "35") (pinfunction "VREFVCO1_35") (pintype "bidirectional"))
    )
    (net (code "58") (name "Net-(C114-C1)") (class "Default")
      (node (ref "C114") (pin "1") (pinfunction "C1_1") (pintype "passive"))
      (node (ref "U25") (pin "1") (pinfunction "VREFVCO2_1") (pintype "bidirectional"))
    )
    (net (code "59") (name "Net-(C115-C1)") (class "Default")
      (node (ref "C115") (pin "1") (pinfunction "C1_1") (pintype "passive"))
      (node (ref "U25") (pin "11") (pinfunction "CPBIAS_11") (pintype "bidirectional"))
    )
    (net (code "60") (name "Net-(C116-C1)") (class "Default")
      (node (ref "C116") (pin "1") (pinfunction "C1_1") (pintype "passive"))
      (node (ref "FB3") (pin "2") (pinfunction "2_2") (pintype "passive"))
      (node (ref "U25") (pin "18") (pinfunction "VDDDIG_18") (pintype "bidirectional"))
    )
    (net (code "61") (name "Net-(C117-C1)") (class "Default")
      (node (ref "C117") (pin "1") (pinfunction "C1_1") (pintype "passive"))
      (node (ref "R63") (pin "1") (pinfunction "1_1") (pintype "passive"))
    )
    (net (code "62") (name "Net-(C118-C1)") (class "Default")
      (node (ref "C118") (pin "1") (pinfunction "C1_1") (pintype "passive"))
      (node (ref "R63") (pin "2") (pinfunction "2_2") (pintype "passive"))
      (node (ref "R64") (pin "2") (pinfunction "2_2") (pintype "passive"))
      (node (ref "U25") (pin "10") (pinfunction "CPOUT_10") (pintype "bidirectional"))
    )
    (net (code "63") (name "Net-(C119-C1)") (class "Default")
      (node (ref "C119") (pin "1") (pinfunction "C1_1") (pintype "passive"))
      (node (ref "R64") (pin "1") (pinfunction "1_1") (pintype "passive"))
      (node (ref "U25") (pin "5") (pinfunction "VTUNE_5") (pintype "bidirectional"))
    )
    (net (code "64") (name "Net-(C120-C1)") (class "Default")
      (node (ref "C120") (pin "1") (pinfunction "C1_1") (pintype "passive"))
      (node (ref "C122") (pin "1") (pinfunction "C1_1") (pintype "passive"))
      (node (ref "L5") (pin "2") (pinfunction "2_2") (pintype "passive"))
      (node (ref "R65") (pin "2") (pinfunction "2_2") (pintype "passive"))
      (node (ref "R67") (pin "2") (pinfunction "2_2") (pintype "passive"))
    )
    (net (code "65") (name "Net-(C121-C1)") (class "Default")
      (node (ref "C121") (pin "1") (pinfunction "C1_1") (pintype "passive"))
      (node (ref "C123") (pin "1") (pinfunction "C1_1") (pintype "passive"))
      (node (ref "L6") (pin "2") (pinfunction "2_2") (pintype "passive"))
      (node (ref "R66") (pin "2") (pinfunction "2_2") (pintype "passive"))
      (node (ref "R68") (pin "2") (pinfunction "2_2") (pintype "passive"))
    )
    (net (code "66") (name "Net-(C124-C1)") (class "Default")
      (node (ref "C124") (pin "1") (pinfunction "C1_1") (pintype "passive"))
      (node (ref "R67") (pin "1") (pinfunction "1_1") (pintype "passive"))
      (node (ref "U25") (pin "39") (pinfunction "~{RF_OUTA}_39") (pintype "bidirectional"))
    )
    (net (code "67") (name "Net-(C124-C2)") (class "Default")
      (node (ref "C124") (pin "2") (pinfunction "C2_2") (pintype "passive"))
      (node (ref "R69") (pin "2") (pinfunction "2_2") (pintype "passive"))
    )
    (net (code "68") (name "Net-(C125-C1)") (class "Default")
      (node (ref "C125") (pin "1") (pinfunction "C1_1") (pintype "passive"))
      (node (ref "R68") (pin "1") (pinfunction "1_1") (pintype "passive"))
      (node (ref "U25") (pin "46") (pinfunction "~{RF_OUTB}_46") (pintype "bidirectional"))
    )
    (net (code "69") (name "Net-(C125-C2)") (class "Default")
      (node (ref "C125") (pin "2") (pinfunction "C2_2") (pintype "passive"))
      (node (ref "R70") (pin "2") (pinfunction "2_2") (pintype "passive"))
    )
    (net (code "70") (name "Net-(C126-C1)") (class "Default")
      (node (ref "C126") (pin "1") (pinfunction "C1_1") (pintype "passive"))
      (node (ref "R65") (pin "1") (pinfunction "1_1") (pintype "passive"))
      (node (ref "U25") (pin "40") (pinfunction "RF_OUTA_40") (pintype "bidirectional"))
    )
    (net (code "71") (name "Net-(C127-C1)") (class "Default")
      (node (ref "C127") (pin "1") (pinfunction "C1_1") (pintype "passive"))
      (node (ref "R66") (pin "1") (pinfunction "1_1") (pintype "passive"))
      (node (ref "U25") (pin "45") (pinfunction "RF_OUTB_45") (pintype "bidirectional"))
    )
    (net (code "72") (name "Net-(C135-C1)") (class "Default")
      (node (ref "C135") (pin "1") (pinfunction "C1_1") (pintype "passive"))
      (node (ref "U27") (pin "4") (pinfunction "SS_4") (pintype "bidirectional"))
    )
    (net (code "73") (name "Net-(C136-C1)") (class "Default")
      (node (ref "C136") (pin "1") (pinfunction "C1_1") (pintype "passive"))
      (node (ref "U28") (pin "4") (pinfunction "SS_4") (pintype "bidirectional"))
    )
    (net (code "74") (name "Net-(C145-C1)") (class "Default")
      (node (ref "C145") (pin "1") (pinfunction "C1_1") (pintype "passive"))
      (node (ref "U29") (pin "6") (pinfunction "C+_6") (pintype "bidirectional"))
    )
    (net (code "75") (name "Net-(C145-C2)") (class "Default")
      (node (ref "C145") (pin "2") (pinfunction "C2_2") (pintype "passive"))
      (node (ref "U29") (pin "3") (pinfunction "C-_3") (pintype "bidirectional"))
    )
    (net (code "76") (name "Net-(C167-C1)") (class "Default")
      (node (ref "C167") (pin "1") (pinfunction "C1_1") (pintype "passive"))
      (node (ref "U33") (pin "4") (pinfunction "SS_4") (pintype "bidirectional"))
    )
    (net (code "77") (name "Net-(C168-C1)") (class "Default")
      (node (ref "C168") (pin "1") (pinfunction "C1_1") (pintype "passive"))
      (node (ref "U34") (pin "4") (pinfunction "SS_4") (pintype "bidirectional"))
    )
    (net (code "78") (name "Net-(D1-PadC)") (class "Default")
      (node (ref "D1") (pin "C") (pinfunction "C_C") (pintype "passive"))
      (node (ref "R6") (pin "2") (pinfunction "2_2") (pintype "passive"))
    )
    (net (code "79") (name "Net-(D2-PadC)") (class "Default")
      (node (ref "D2") (pin "C") (pinfunction "C_C") (pintype "passive"))
      (node (ref "R8") (pin "2") (pinfunction "2_2") (pintype "passive"))
    )
    (net (code "80") (name "Net-(RFCON1-SIGNAL)") (class "Default")
      (node (ref "RFCON1") (pin "P$3") (pinfunction "SIGNAL_P$3") (pintype "bidirectional"))
      (node (ref "U10") (pin "1") (pinfunction "RFIN_1") (pintype "bidirectional"))
    )
    (net (code "81") (name "Net-(RFCON2-SIGNAL)") (class "Default")
      (node (ref "RFCON2") (pin "SIG") (pinfunction "SIGNAL_SIG") (pintype "bidirectional"))
      (node (ref "U12") (pin "9") (pinfunction "RF_9") (pintype "input"))
    )
    (net (code "82") (name "Net-(RFCON3-SIGNAL)") (class "Default")
      (node (ref "RFCON3") (pin "P$3") (pinfunction "SIGNAL_P$3") (pintype "bidirectional"))
      (node (ref "U13") (pin "3") (pinfunction "RFOUT_3") (pintype "bidirectional"))
    )
    (net (code "83") (name "Net-(RFCON4-SIGNAL)") (class "Default")
      (node (ref "RFCON4") (pin "SIG") (pinfunction "SIGNAL_SIG") (pintype "bidirectional"))
      (node (ref "U15") (pin "18") (pinfunction "RF_IN_18") (pintype "input"))
    )
    (net (code "84") (name "Net-(RFCON6-SIGNAL)") (class "Default")
      (node (ref "RFCON6") (pin "P$3") (pinfunction "SIGNAL_P$3") (pintype "bidirectional"))
      (node (ref "U21") (pin "14") (pinfunction "RF1_14") (pintype "bidirectional"))
    )
    (net (code "85") (name "Net-(RFCON7-SIGNAL)") (class "Default")
      (node (ref "RFCON7") (pin "P$3") (pinfunction "SIGNAL_P$3") (pintype "bidirectional"))
      (node (ref "U24") (pin "7") (pinfunction "RF2_7") (pintype "bidirectional"))
    )
    (net (code "86") (name "Net-(U5-~{OE})") (class "Default")
      (node (ref "R12") (pin "1") (pinfunction "1_1") (pintype "passive"))
      (node (ref "R13") (pin "2") (pinfunction "2_2") (pintype "passive"))
      (node (ref "U5") (pin "9") (pinfunction "~{OE}_9") (pintype "bidirectional"))
    )
    (net (code "87") (name "Net-(U6-~{OE})") (class "Default")
      (node (ref "R21") (pin "1") (pinfunction "1_1") (pintype "passive"))
      (node (ref "R22") (pin "2") (pinfunction "2_2") (pintype "passive"))
      (node (ref "U6") (pin "9") (pinfunction "~{OE}_9") (pintype "bidirectional"))
    )
    (net (code "88") (name "Net-(U7A--IN)") (class "Default")
      (node (ref "R27") (pin "2") (pinfunction "2_2") (pintype "passive"))
      (node (ref "R29") (pin "2") (pinfunction "2_2") (pintype "passive"))
      (node (ref "U7") (pin "2") (pinfunction "-IN_2") (pintype "input"))
    )
    (net (code "89") (name "Net-(U7A-OUT)") (class "Default")
      (node (ref "R29") (pin "1") (pinfunction "1_1") (pintype "passive"))
      (node (ref "R31") (pin "2") (pinfunction "2_2") (pintype "passive"))
      (node (ref "U7") (pin "1") (pinfunction "OUT_1") (pintype "output"))
    )
    (net (code "90") (name "Net-(U7B--IN)") (class "Default")
      (node (ref "R26") (pin "2") (pinfunction "2_2") (pintype "passive"))
      (node (ref "R28") (pin "2") (pinfunction "2_2") (pintype "passive"))
      (node (ref "U7") (pin "6") (pinfunction "-IN_6") (pintype "input"))
    )
    (net (code "91") (name "Net-(U7B-OUT)") (class "Default")
      (node (ref "R28") (pin "1") (pinfunction "1_1") (pintype "passive"))
      (node (ref "R30") (pin "2") (pinfunction "2_2") (pintype "passive"))
      (node (ref "U7") (pin "7") (pinfunction "OUT_7") (pintype "output"))
    )
    (net (code "92") (name "Net-(U9A-+IN)") (class "Default")
      (node (ref "R33") (pin "1") (pinfunction "1_1") (pintype "passive"))
      (node (ref "R34") (pin "2") (pinfunction "2_2") (pintype "passive"))
      (node (ref "U9") (pin "3") (pinfunction "+IN_3") (pintype "input"))
    )
    (net (code "93") (name "Net-(U9A--IN)") (class "Default")
      (node (ref "R32") (pin "1") (pinfunction "1_1") (pintype "passive"))
      (node (ref "R35") (pin "2") (pinfunction "2_2") (pintype "passive"))
      (node (ref "U9") (pin "2") (pinfunction "-IN_2") (pintype "input"))
    )
    (net (code "94") (name "Net-(U9A-OUT)") (class "Default")
      (node (ref "R35") (pin "1") (pinfunction "1_1") (pintype "passive"))
      (node (ref "R37") (pin "2") (pinfunction "2_2") (pintype "passive"))
      (node (ref "U9") (pin "1") (pinfunction "OUT_1") (pintype "output"))
    )
    (net (code "95") (name "Net-(U9B--IN)") (class "Default")
      (node (ref "R36") (pin "2") (pinfunction "2_2") (pintype "passive"))
      (node (ref "U9") (pin "6") (pinfunction "-IN_6") (pintype "input"))
      (node (ref "U9") (pin "7") (pinfunction "OUT_7") (pintype "output"))
    )
    (net (code "96") (name "Net-(U10-RFOUT)") (class "Default")
      (node (ref "U10") (pin "3") (pinfunction "RFOUT_3") (pintype "bidirectional"))
      (node (ref "U11") (pin "1") (pinfunction "SUM_1") (pintype "bidirectional"))
    )
    (net (code "97") (name "Net-(U11-0DEG)") (class "Default")
      (node (ref "U11") (pin "4") (pinfunction "0DEG_4") (pintype "bidirectional"))
      (node (ref "U12") (pin "30") (pinfunction "IF_I_30") (pintype "input"))
    )
    (net (code "98") (name "Net-(U11-ISO)") (class "Default")
      (node (ref "R40") (pin "2") (pinfunction "2_2") (pintype "passive"))
      (node (ref "U11") (pin "3") (pinfunction "ISO_3") (pintype "bidirectional"))
    )
    (net (code "99") (name "Net-(U11-P90DEG)") (class "Default")
      (node (ref "U11") (pin "6") (pinfunction "P90DEG_6") (pintype "bidirectional"))
      (node (ref "U12") (pin "24") (pinfunction "IF_Q_24") (pintype "input"))
    )
    (net (code "100") (name "Net-(U12-BG_RBIAS1)") (class "Default")
      (node (ref "R44") (pin "2") (pinfunction "2_2") (pintype "passive"))
      (node (ref "U12") (pin "34") (pinfunction "BG_RBIAS1_34") (pintype "bidirectional"))
    )
    (net (code "101") (name "Net-(U12-BG_RBIAS2)") (class "Default")
      (node (ref "R42") (pin "2") (pinfunction "2_2") (pintype "passive"))
      (node (ref "U12") (pin "6") (pinfunction "BG_RBIAS2_6") (pintype "bidirectional"))
    )
    (net (code "102") (name "Net-(U12-LON)") (class "Default")
      (node (ref "R45") (pin "2") (pinfunction "2_2") (pintype "passive"))
      (node (ref "U12") (pin "37") (pinfunction "LON_37") (pintype "input"))
    )
    (net (code "103") (name "Net-(U12-VCTRL1)") (class "Default")
      (node (ref "R41") (pin "2") (pinfunction "2_2") (pintype "passive"))
      (node (ref "U12") (pin "15") (pinfunction "VCTRL1_15") (pintype "input"))
    )
    (net (code "104") (name "Net-(U12-VCTRL2)") (class "Default")
      (node (ref "R43") (pin "2") (pinfunction "2_2") (pintype "passive"))
      (node (ref "U12") (pin "16") (pinfunction "VCTRL2_16") (pintype "input"))
    )
    (net (code "105") (name "Net-(U13-RFIN)") (class "Default")
      (node (ref "U13") (pin "1") (pinfunction "RFIN_1") (pintype "bidirectional"))
      (node (ref "U14") (pin "1") (pinfunction "SUM_1") (pintype "bidirectional"))
    )
    (net (code "106") (name "Net-(U14-0DEG)") (class "Default")
      (node (ref "U14") (pin "4") (pinfunction "0DEG_4") (pintype "bidirectional"))
      (node (ref "U15") (pin "6") (pinfunction "IF_Q_6") (pintype "input"))
    )
    (net (code "107") (name "Net-(U14-ISO)") (class "Default")
      (node (ref "R46") (pin "2") (pinfunction "2_2") (pintype "passive"))
      (node (ref "U14") (pin "3") (pinfunction "ISO_3") (pintype "bidirectional"))
    )
    (net (code "108") (name "Net-(U14-P90DEG)") (class "Default")
      (node (ref "U14") (pin "6") (pinfunction "P90DEG_6") (pintype "bidirectional"))
      (node (ref "U15") (pin "4") (pinfunction "IF_I_4") (pintype "input"))
    )
    (net (code "109") (name "Net-(U15-BG_RBIAS)") (class "Default")
      (node (ref "R47") (pin "2") (pinfunction "2_2") (pintype "passive"))
      (node (ref "U15") (pin "23") (pinfunction "BG_RBIAS_23") (pintype "bidirectional"))
    )
    (net (code "110") (name "Net-(U15-LO_N)") (class "Default")
      (node (ref "R48") (pin "2") (pinfunction "2_2") (pintype "passive"))
      (node (ref "U15") (pin "26") (pinfunction "LO_N_26") (pintype "input"))
    )
    (net (code "111") (name "Net-(U19-RFIN)") (class "Default")
      (node (ref "R55") (pin "2") (pinfunction "2_2") (pintype "passive"))
      (node (ref "U19") (pin "6") (pinfunction "RFIN_6") (pintype "bidirectional"))
    )
    (net (code "112") (name "Net-(U20-RFC)") (class "Default")
      (node (ref "U20") (pin "3") (pinfunction "RFC_3") (pintype "bidirectional"))
      (node (ref "U21") (pin "3") (pinfunction "RFC_3") (pintype "bidirectional"))
    )
    (net (code "113") (name "Net-(U22-RFIN)") (class "Default")
      (node (ref "R57") (pin "2") (pinfunction "2_2") (pintype "passive"))
      (node (ref "U22") (pin "6") (pinfunction "RFIN_6") (pintype "bidirectional"))
    )
    (net (code "114") (name "Net-(U23-RFC)") (class "Default")
      (node (ref "U23") (pin "3") (pinfunction "RFC_3") (pintype "bidirectional"))
      (node (ref "U24") (pin "3") (pinfunction "RFC_3") (pintype "bidirectional"))
    )
    (net (code "115") (name "RF_GP_PWR_EN") (class "Default")
      (node (ref "R73") (pin "2") (pinfunction "2_2") (pintype "passive"))
      (node (ref "U1") (pin "15") (pinfunction "PB7_15") (pintype "bidirectional"))
      (node (ref "U26") (pin "3") (pinfunction "EN_3") (pintype "bidirectional"))
    )
    (net (code "116") (name "RF_SPI_MISO") (class "Default")
      (node (ref "U1") (pin "60") (pinfunction "PE11_60") (pintype "bidirectional"))
      (node (ref "U5") (pin "6") (pinfunction "A3_6") (pintype "bidirectional"))
      (node (ref "U6") (pin "6") (pinfunction "A3_6") (pintype "bidirectional"))
    )
    (net (code "117") (name "RF_SPI_MOSI") (class "Default")
      (node (ref "U1") (pin "59") (pinfunction "PE10_59") (pintype "bidirectional"))
      (node (ref "U5") (pin "5") (pinfunction "A2_5") (pintype "bidirectional"))
      (node (ref "U6") (pin "5") (pinfunction "A2_5") (pintype "bidirectional"))
    )
    (net (code "118") (name "RF_SPI_SCK") (class "Default")
      (node (ref "U1") (pin "61") (pinfunction "PE12_61") (pintype "bidirectional"))
      (node (ref "U5") (pin "4") (pinfunction "A1_4") (pintype "bidirectional"))
      (node (ref "U6") (pin "4") (pinfunction "A1_4") (pintype "bidirectional"))
    )
    (net (code "119") (name "RX_ANA_PWR_EN") (class "Default")
      (node (ref "R75") (pin "2") (pinfunction "2_2") (pintype "passive"))
      (node (ref "U1") (pin "24") (pinfunction "PB13_24") (pintype "bidirectional"))
      (node (ref "U32") (pin "5") (pinfunction "EN/UVLO_5") (pintype "bidirectional"))
      (node (ref "U34") (pin "5") (pinfunction "EN_5") (pintype "bidirectional"))
    )
    (net (code "120") (name "RX_DIG_PWR_EN") (class "Default")
      (node (ref "R77") (pin "2") (pinfunction "2_2") (pintype "passive"))
      (node (ref "U1") (pin "21") (pinfunction "PB11_21") (pintype "bidirectional"))
      (node (ref "U31") (pin "3") (pinfunction "EN_3") (pintype "bidirectional"))
    )
    (net (code "121") (name "RX_GAIN_VCTRL") (class "Default")
      (node (ref "U15") (pin "14") (pinfunction "VCTRL_14") (pintype "input"))
      (node (ref "U8") (pin "6") (pinfunction "VOUTA_6") (pintype "bidirectional"))
    )
    (net (code "122") (name "RX_LO") (class "Default")
      (node (ref "U15") (pin "27") (pinfunction "LO_P_27") (pintype "input"))
      (node (ref "U24") (pin "14") (pinfunction "RF1_14") (pintype "bidirectional"))
    )
    (net (code "123") (name "RX_LO_DST_SEL") (class "Default")
      (node (ref "U1") (pin "41") (pinfunction "PE4_41") (pintype "bidirectional"))
      (node (ref "U24") (pin "10") (pinfunction "VCTRL_10") (pintype "bidirectional"))
    )
    (net (code "124") (name "RX_LO_SRC_SEL") (class "Default")
      (node (ref "U1") (pin "42") (pinfunction "PE5_42") (pintype "bidirectional"))
      (node (ref "U23") (pin "10") (pinfunction "VCTRL_10") (pintype "bidirectional"))
    )
    (net (code "125") (name "RX_LO_VPWR") (class "Default")
      (node (ref "C93") (pin "1") (pinfunction "C1_1") (pintype "passive"))
      (node (ref "R24") (pin "2") (pinfunction "2_2") (pintype "passive"))
      (node (ref "U22") (pin "2") (pinfunction "OUT_2") (pintype "bidirectional"))
    )
    (net (code "126") (name "RX_LO_VPWR_SCALED") (class "Default")
      (node (ref "C22") (pin "1") (pinfunction "C1_1") (pintype "passive"))
      (node (ref "R30") (pin "1") (pinfunction "1_1") (pintype "passive"))
      (node (ref "U1") (pin "30") (pinfunction "PD2_30") (pintype "bidirectional"))
    )
    (net (code "127") (name "RX_PWR_VDET") (class "Default")
      (node (ref "U15") (pin "11") (pinfunction "VDET_11") (pintype "input"))
      (node (ref "U9") (pin "5") (pinfunction "+IN_5") (pintype "input"))
    )
    (net (code "128") (name "RX_PWR_VDET_SCALED") (class "Default")
      (node (ref "C26") (pin "1") (pinfunction "C1_1") (pintype "passive"))
      (node (ref "R36") (pin "1") (pinfunction "1_1") (pintype "passive"))
      (node (ref "R38") (pin "2") (pinfunction "2_2") (pintype "passive"))
      (node (ref "U1") (pin "28") (pinfunction "PD0_28") (pintype "bidirectional"))
    )
    (net (code "129") (name "RX_RST") (class "Default")
      (node (ref "Q1") (pin "1") (pinfunction "G_1") (pintype "passive"))
      (node (ref "R15") (pin "2") (pinfunction "2_2") (pintype "passive"))
      (node (ref "U1") (pin "47") (pinfunction "PF10_47") (pintype "bidirectional"))
    )
    (net (code "130") (name "RX_SPI_MISO_1V8") (class "Default")
      (node (ref "U15") (pin "9") (pinfunction "SDO_9") (pintype "output"))
      (node (ref "U6") (pin "11") (pinfunction "B3_11") (pintype "bidirectional"))
    )
    (net (code "131") (name "RX_SPI_MOSI_1V8") (class "Default")
      (node (ref "U15") (pin "32") (pinfunction "SDI_32") (pintype "input"))
      (node (ref "U6") (pin "12") (pinfunction "B2_12") (pintype "bidirectional"))
    )
    (net (code "132") (name "RX_SPI_SCK_1V8") (class "Default")
      (node (ref "U15") (pin "31") (pinfunction "SCLK_31") (pintype "input"))
      (node (ref "U6") (pin "13") (pinfunction "B1_13") (pintype "bidirectional"))
    )
    (net (code "133") (name "SWCLK") (class "Default")
      (node (ref "TC1") (pin "4") (pinfunction "S_4") (pintype "passive"))
      (node (ref "U1") (pin "49") (pinfunction "PF0_49") (pintype "bidirectional"))
    )
    (net (code "134") (name "SWDIO") (class "Default")
      (node (ref "TC1") (pin "2") (pinfunction "S_2") (pintype "passive"))
      (node (ref "U1") (pin "50") (pinfunction "PF1_50") (pintype "bidirectional"))
    )
    (net (code "135") (name "SWO") (class "Default")
      (node (ref "TC1") (pin "6") (pinfunction "S_6") (pintype "passive"))
      (node (ref "U1") (pin "51") (pinfunction "PF2_51") (pintype "bidirectional"))
    )
    (net (code "136") (name "SYNTH_CE") (class "Default")
      (node (ref "U1") (pin "64") (pinfunction "PE15_64") (pintype "bidirectional"))
      (node (ref "U25") (pin "29") (pinfunction "CE_29") (pintype "bidirectional"))
    )
    (net (code "137") (name "SYNTH_LD") (class "Default")
      (node (ref "U1") (pin "6") (pinfunction "PA5_6") (pintype "bidirectional"))
      (node (ref "U25") (pin "8") (pinfunction "LD_8") (pintype "bidirectional"))
    )
    (net (code "138") (name "SYNTH_MUTE") (class "Default")
      (node (ref "U1") (pin "5") (pinfunction "PA4_5") (pintype "bidirectional"))
      (node (ref "U25") (pin "7") (pinfunction "MUTE_7") (pintype "bidirectional"))
    )
    (net (code "139") (name "SYNTH_PWR_EN") (class "Default")
      (node (ref "R72") (pin "2") (pinfunction "2_2") (pintype "passive"))
      (node (ref "U1") (pin "25") (pinfunction "PB14_25") (pintype "bidirectional"))
      (node (ref "U28") (pin "5") (pinfunction "EN_5") (pintype "bidirectional"))
    )
    (net (code "140") (name "SYNTH_REF_CLK") (class "Default")
      (node (ref "C102") (pin "1") (pinfunction "C1_1") (pintype "passive"))
      (node (ref "JP2") (pin "3") (pinfunction "S_3") (pintype "passive"))
      (node (ref "R58") (pin "2") (pinfunction "2_2") (pintype "passive"))
    )
    (net (code "141") (name "SYNTH_SPI_MISO") (class "Default")
      (node (ref "U1") (pin "2") (pinfunction "PA1_2") (pintype "bidirectional"))
      (node (ref "U25") (pin "27") (pinfunction "SDO_27") (pintype "bidirectional"))
    )
    (net (code "142") (name "SYNTH_SPI_MOSI") (class "Default")
      (node (ref "U1") (pin "1") (pinfunction "PA0_1") (pintype "bidirectional"))
      (node (ref "U25") (pin "28") (pinfunction "SDIO_28") (pintype "bidirectional"))
    )
    (net (code "143") (name "SYNTH_SPI_SCK") (class "Default")
      (node (ref "U1") (pin "3") (pinfunction "PA2_3") (pintype "bidirectional"))
      (node (ref "U25") (pin "26") (pinfunction "SCLK_26") (pintype "bidirectional"))
    )
    (net (code "144") (name "SYNTH_SYNC") (class "Default")
      (node (ref "R23") (pin "2") (pinfunction "2_2") (pintype "passive"))
      (node (ref "U1") (pin "63") (pinfunction "PE14_63") (pintype "bidirectional"))
      (node (ref "U25") (pin "30") (pinfunction "SYNC_30") (pintype "bidirectional"))
    )
    (net (code "145") (name "TSENS_I2C_SCL") (class "Default")
      (node (ref "R1") (pin "1") (pinfunction "1_1") (pintype "passive"))
      (node (ref "U1") (pin "54") (pinfunction "PF5_54") (pintype "bidirectional"))
      (node (ref "U2") (pin "4") (pinfunction "SCL_4") (pintype "bidirectional"))
      (node (ref "U3") (pin "4") (pinfunction "SCL_4") (pintype "bidirectional"))
      (node (ref "U4") (pin "4") (pinfunction "SCL_4") (pintype "bidirectional"))
    )
    (net (code "146") (name "TSENS_I2C_SDA") (class "Default")
      (node (ref "R2") (pin "1") (pinfunction "1_1") (pintype "passive"))
      (node (ref "U1") (pin "57") (pinfunction "PE8_57") (pintype "bidirectional"))
      (node (ref "U2") (pin "5") (pinfunction "SDA_5") (pintype "bidirectional"))
      (node (ref "U3") (pin "5") (pinfunction "SDA_5") (pintype "bidirectional"))
      (node (ref "U4") (pin "5") (pinfunction "SDA_5") (pintype "bidirectional"))
    )
    (net (code "147") (name "TSENS_VDD") (class "Default")
      (node (ref "C10") (pin "1") (pinfunction "C1_1") (pintype "passive"))
      (node (ref "C11") (pin "1") (pinfunction "C1_1") (pintype "passive"))
      (node (ref "C12") (pin "1") (pinfunction "C1_1") (pintype "passive"))
      (node (ref "R1") (pin "2") (pinfunction "2_2") (pintype "passive"))
      (node (ref "R14") (pin "1") (pinfunction "1_1") (pintype "passive"))
      (node (ref "R2") (pin "2") (pinfunction "2_2") (pintype "passive"))
      (node (ref "U1") (pin "58") (pinfunction "PE9_58") (pintype "bidirectional"))
      (node (ref "U2") (pin "1") (pinfunction "VDD_1") (pintype "bidirectional"))
      (node (ref "U3") (pin "1") (pinfunction "VDD_1") (pintype "bidirectional"))
      (node (ref "U4") (pin "1") (pinfunction "VDD_1") (pintype "bidirectional"))
    )
    (net (code "148") (name "TX_ANA_PWR_EN") (class "Default")
      (node (ref "R76") (pin "2") (pinfunction "2_2") (pintype "passive"))
      (node (ref "U1") (pin "14") (pinfunction "PC5_14") (pintype "bidirectional"))
      (node (ref "U33") (pin "5") (pinfunction "EN_5") (pintype "bidirectional"))
    )
    (net (code "149") (name "TX_DIG_PWR_EN") (class "Default")
      (node (ref "R78") (pin "2") (pinfunction "2_2") (pintype "passive"))
      (node (ref "U1") (pin "19") (pinfunction "PA14_19") (pintype "bidirectional"))
      (node (ref "U30") (pin "3") (pinfunction "EN_3") (pintype "bidirectional"))
    )
    (net (code "150") (name "TX_GAIN_VCTRL1") (class "Default")
      (node (ref "R41") (pin "1") (pinfunction "1_1") (pintype "passive"))
      (node (ref "U8") (pin "9") (pinfunction "VOUTD_9") (pintype "bidirectional"))
    )
    (net (code "151") (name "TX_GAIN_VCTRL2") (class "Default")
      (node (ref "R43") (pin "1") (pinfunction "1_1") (pintype "passive"))
      (node (ref "U8") (pin "8") (pinfunction "VOUTC_8") (pintype "bidirectional"))
    )
    (net (code "152") (name "TX_LO") (class "Default")
      (node (ref "U12") (pin "38") (pinfunction "LOP_38") (pintype "input"))
      (node (ref "U21") (pin "7") (pinfunction "RF2_7") (pintype "bidirectional"))
    )
    (net (code "153") (name "TX_LO_DST_SEL") (class "Default")
      (node (ref "U1") (pin "43") (pinfunction "PE6_43") (pintype "bidirectional"))
      (node (ref "U21") (pin "10") (pinfunction "VCTRL_10") (pintype "bidirectional"))
    )
    (net (code "154") (name "TX_LO_SRC_SEL") (class "Default")
      (node (ref "U1") (pin "44") (pinfunction "PE7_44") (pintype "bidirectional"))
      (node (ref "U20") (pin "10") (pinfunction "VCTRL_10") (pintype "bidirectional"))
    )
    (net (code "155") (name "TX_LO_VPWR") (class "Default")
      (node (ref "C83") (pin "1") (pinfunction "C1_1") (pintype "passive"))
      (node (ref "R25") (pin "2") (pinfunction "2_2") (pintype "passive"))
      (node (ref "U19") (pin "2") (pinfunction "OUT_2") (pintype "bidirectional"))
    )
    (net (code "156") (name "TX_LO_VPWR_SCALED") (class "Default")
      (node (ref "C23") (pin "1") (pinfunction "C1_1") (pintype "passive"))
      (node (ref "R31") (pin "1") (pinfunction "1_1") (pintype "passive"))
      (node (ref "U1") (pin "31") (pinfunction "PD3_31") (pintype "bidirectional"))
    )
    (net (code "157") (name "TX_PWR_VDET_N") (class "Default")
      (node (ref "R32") (pin "2") (pinfunction "2_2") (pintype "passive"))
      (node (ref "U12") (pin "21") (pinfunction "VENV_N_21") (pintype "input"))
    )
    (net (code "158") (name "TX_PWR_VDET_P") (class "Default")
      (node (ref "R33") (pin "2") (pinfunction "2_2") (pintype "passive"))
      (node (ref "U12") (pin "22") (pinfunction "VENV_P_22") (pintype "input"))
    )
    (net (code "159") (name "TX_PWR_VDET_SCALED") (class "Default")
      (node (ref "C27") (pin "1") (pinfunction "C1_1") (pintype "passive"))
      (node (ref "R37") (pin "1") (pinfunction "1_1") (pintype "passive"))
      (node (ref "R39") (pin "2") (pinfunction "2_2") (pintype "passive"))
      (node (ref "U1") (pin "29") (pinfunction "PD1_29") (pintype "bidirectional"))
    )
    (net (code "160") (name "TX_RST") (class "Default")
      (node (ref "Q2") (pin "1") (pinfunction "G_1") (pintype "passive"))
      (node (ref "R19") (pin "2") (pinfunction "2_2") (pintype "passive"))
      (node (ref "U1") (pin "12") (pinfunction "PB6_12") (pintype "bidirectional"))
    )
    (net (code "161") (name "TX_SPI_MISO_1V8") (class "Default")
      (node (ref "U12") (pin "5") (pinfunction "SDO_5") (pintype "output"))
      (node (ref "U5") (pin "11") (pinfunction "B3_11") (pintype "bidirectional"))
    )
    (net (code "162") (name "TX_SPI_MOSI_1V8") (class "Default")
      (node (ref "U12") (pin "4") (pinfunction "SDI_4") (pintype "input"))
      (node (ref "U5") (pin "12") (pinfunction "B2_12") (pintype "bidirectional"))
    )
    (net (code "163") (name "TX_SPI_SCK_1V8") (class "Default")
      (node (ref "U12") (pin "3") (pinfunction "SCLK_3") (pintype "input"))
      (node (ref "U5") (pin "13") (pinfunction "B1_13") (pintype "bidirectional"))
    )
    (net (code "164") (name "unconnected-(TC1F-S-Pad5)") (class "Default")
      (node (ref "TC1") (pin "5") (pinfunction "S_5") (pintype "passive"))
    )
    (net (code "165") (name "unconnected-(U1-PB8-Pad16)") (class "Default")
      (node (ref "U1") (pin "16") (pinfunction "PB8_16") (pintype "bidirectional"))
    )
    (net (code "166") (name "unconnected-(U2-ALERT-Pad3)") (class "Default")
      (node (ref "U2") (pin "3") (pinfunction "ALERT_3") (pintype "bidirectional"))
    )
    (net (code "167") (name "unconnected-(U3-ALERT-Pad3)") (class "Default")
      (node (ref "U3") (pin "3") (pinfunction "ALERT_3") (pintype "bidirectional"))
    )
    (net (code "168") (name "unconnected-(U4-ALERT-Pad3)") (class "Default")
      (node (ref "U4") (pin "3") (pinfunction "ALERT_3") (pintype "bidirectional"))
    )
    (net (code "169") (name "unconnected-(U8-VOUTB-Pad7)") (class "Default")
      (node (ref "U8") (pin "7") (pinfunction "VOUTB_7") (pintype "bidirectional"))
    )
    (net (code "170") (name "unconnected-(U8-~{BSY}-Pad5)") (class "Default")
      (node (ref "U8") (pin "5") (pinfunction "~{BSY}_5") (pintype "bidirectional"))
    )
    (net (code "171") (name "unconnected-(U12-I_N-Pad29)") (class "Default")
      (node (ref "U12") (pin "29") (pinfunction "I_N_29") (pintype "input"))
    )
    (net (code "172") (name "unconnected-(U12-I_P-Pad28)") (class "Default")
      (node (ref "U12") (pin "28") (pinfunction "I_P_28") (pintype "input"))
    )
    (net (code "173") (name "unconnected-(U12-Q_N-Pad25)") (class "Default")
      (node (ref "U12") (pin "25") (pinfunction "Q_N_25") (pintype "input"))
    )
    (net (code "174") (name "unconnected-(U12-Q_P-Pad26)") (class "Default")
      (node (ref "U12") (pin "26") (pinfunction "Q_P_26") (pintype "input"))
    )
    (net (code "175") (name "unconnected-(U15-I_N-Pad3)") (class "Default")
      (node (ref "U15") (pin "3") (pinfunction "I_N_3") (pintype "input"))
    )
    (net (code "176") (name "unconnected-(U15-I_P-Pad2)") (class "Default")
      (node (ref "U15") (pin "2") (pinfunction "I_P_2") (pintype "input"))
    )
    (net (code "177") (name "unconnected-(U15-Q_N-Pad7)") (class "Default")
      (node (ref "U15") (pin "7") (pinfunction "Q_N_7") (pintype "input"))
    )
    (net (code "178") (name "unconnected-(U15-Q_P-Pad8)") (class "Default")
      (node (ref "U15") (pin "8") (pinfunction "Q_P_8") (pintype "input"))
    )
    (net (code "179") (name "unconnected-(U17-D0-Pad19)") (class "Default")
      (node (ref "U17") (pin "19") (pinfunction "D0_19") (pintype "bidirectional"))
    )
    (net (code "180") (name "unconnected-(U17-D1-Pad20)") (class "Default")
      (node (ref "U17") (pin "20") (pinfunction "D1_20") (pintype "bidirectional"))
    )
    (net (code "181") (name "unconnected-(U17-D2-Pad21)") (class "Default")
      (node (ref "U17") (pin "21") (pinfunction "D2_21") (pintype "bidirectional"))
    )
    (net (code "182") (name "unconnected-(U17-D3{slash}SEROUT-Pad22)") (class "Default")
      (node (ref "U17") (pin "22") (pinfunction "D3/SEROUT_22") (pintype "bidirectional"))
    )
    (net (code "183") (name "unconnected-(U32-PG-Pad7)") (class "Default")
      (node (ref "U32") (pin "7") (pinfunction "PG_7") (pintype "bidirectional"))
    )
    (net (code "184") (name "~{MCU_RESET}") (class "Default")
      (node (ref "R9") (pin "1") (pinfunction "1_1") (pintype "passive"))
      (node (ref "TC1") (pin "10") (pinfunction "S_10") (pintype "passive"))
      (node (ref "U1") (pin "20") (pinfunction "~{RESET}_20") (pintype "bidirectional"))
    )
    (net (code "185") (name "~{RX_RST_1V8}") (class "Default")
      (node (ref "Q1") (pin "3") (pinfunction "D_3") (pintype "passive"))
      (node (ref "R16") (pin "1") (pinfunction "1_1") (pintype "passive"))
      (node (ref "U15") (pin "22") (pinfunction "RST_22") (pintype "input"))
    )
    (net (code "186") (name "~{RX_SPI_CS_1V8}") (class "Default")
      (node (ref "R17") (pin "1") (pinfunction "1_1") (pintype "passive"))
      (node (ref "U15") (pin "1") (pinfunction "~{SEN}_1") (pintype "input"))
      (node (ref "U6") (pin "14") (pinfunction "B0_14") (pintype "bidirectional"))
    )
    (net (code "187") (name "~{RX_SPI_CS}") (class "Default")
      (node (ref "R18") (pin "1") (pinfunction "1_1") (pintype "passive"))
      (node (ref "R22") (pin "1") (pinfunction "1_1") (pintype "passive"))
      (node (ref "U1") (pin "48") (pinfunction "PF11_48") (pintype "bidirectional"))
      (node (ref "U6") (pin "3") (pinfunction "A0_3") (pintype "bidirectional"))
    )
    (net (code "188") (name "~{SYNTH_RESET}") (class "Default")
      (node (ref "U1") (pin "62") (pinfunction "PE13_62") (pintype "bidirectional"))
      (node (ref "U25") (pin "31") (pinfunction "~{RESET}_31") (pintype "bidirectional"))
    )
    (net (code "189") (name "~{SYNTH_SPI_CS}") (class "Default")
      (node (ref "U1") (pin "4") (pinfunction "PA3_4") (pintype "bidirectional"))
      (node (ref "U25") (pin "25") (pinfunction "~{CS}_25") (pintype "bidirectional"))
    )
    (net (code "190") (name "~{TX_RST_1V8}") (class "Default")
      (node (ref "Q2") (pin "3") (pinfunction "D_3") (pintype "passive"))
      (node (ref "R20") (pin "1") (pinfunction "1_1") (pintype "passive"))
      (node (ref "U12") (pin "1") (pinfunction "RST_1") (pintype "input"))
    )
    (net (code "191") (name "~{TX_SPI_CS_1V8}") (class "Default")
      (node (ref "R10") (pin "1") (pinfunction "1_1") (pintype "passive"))
      (node (ref "U12") (pin "18") (pinfunction "~{SEN2}_18") (pintype "input"))
      (node (ref "U12") (pin "40") (pinfunction "~{SEN}_40") (pintype "input"))
      (node (ref "U5") (pin "14") (pinfunction "B0_14") (pintype "bidirectional"))
    )
    (net (code "192") (name "~{TX_SPI_CS}") (class "Default")
      (node (ref "R11") (pin "1") (pinfunction "1_1") (pintype "passive"))
      (node (ref "R13") (pin "1") (pinfunction "1_1") (pintype "passive"))
      (node (ref "U1") (pin "53") (pinfunction "PF12_53") (pintype "bidirectional"))
      (node (ref "U5") (pin "3") (pinfunction "A0_3") (pintype "bidirectional"))
    )
  )
)
